# FPGA_SUP.net
KiCad netlist of a schematic drawn in Altium Designer
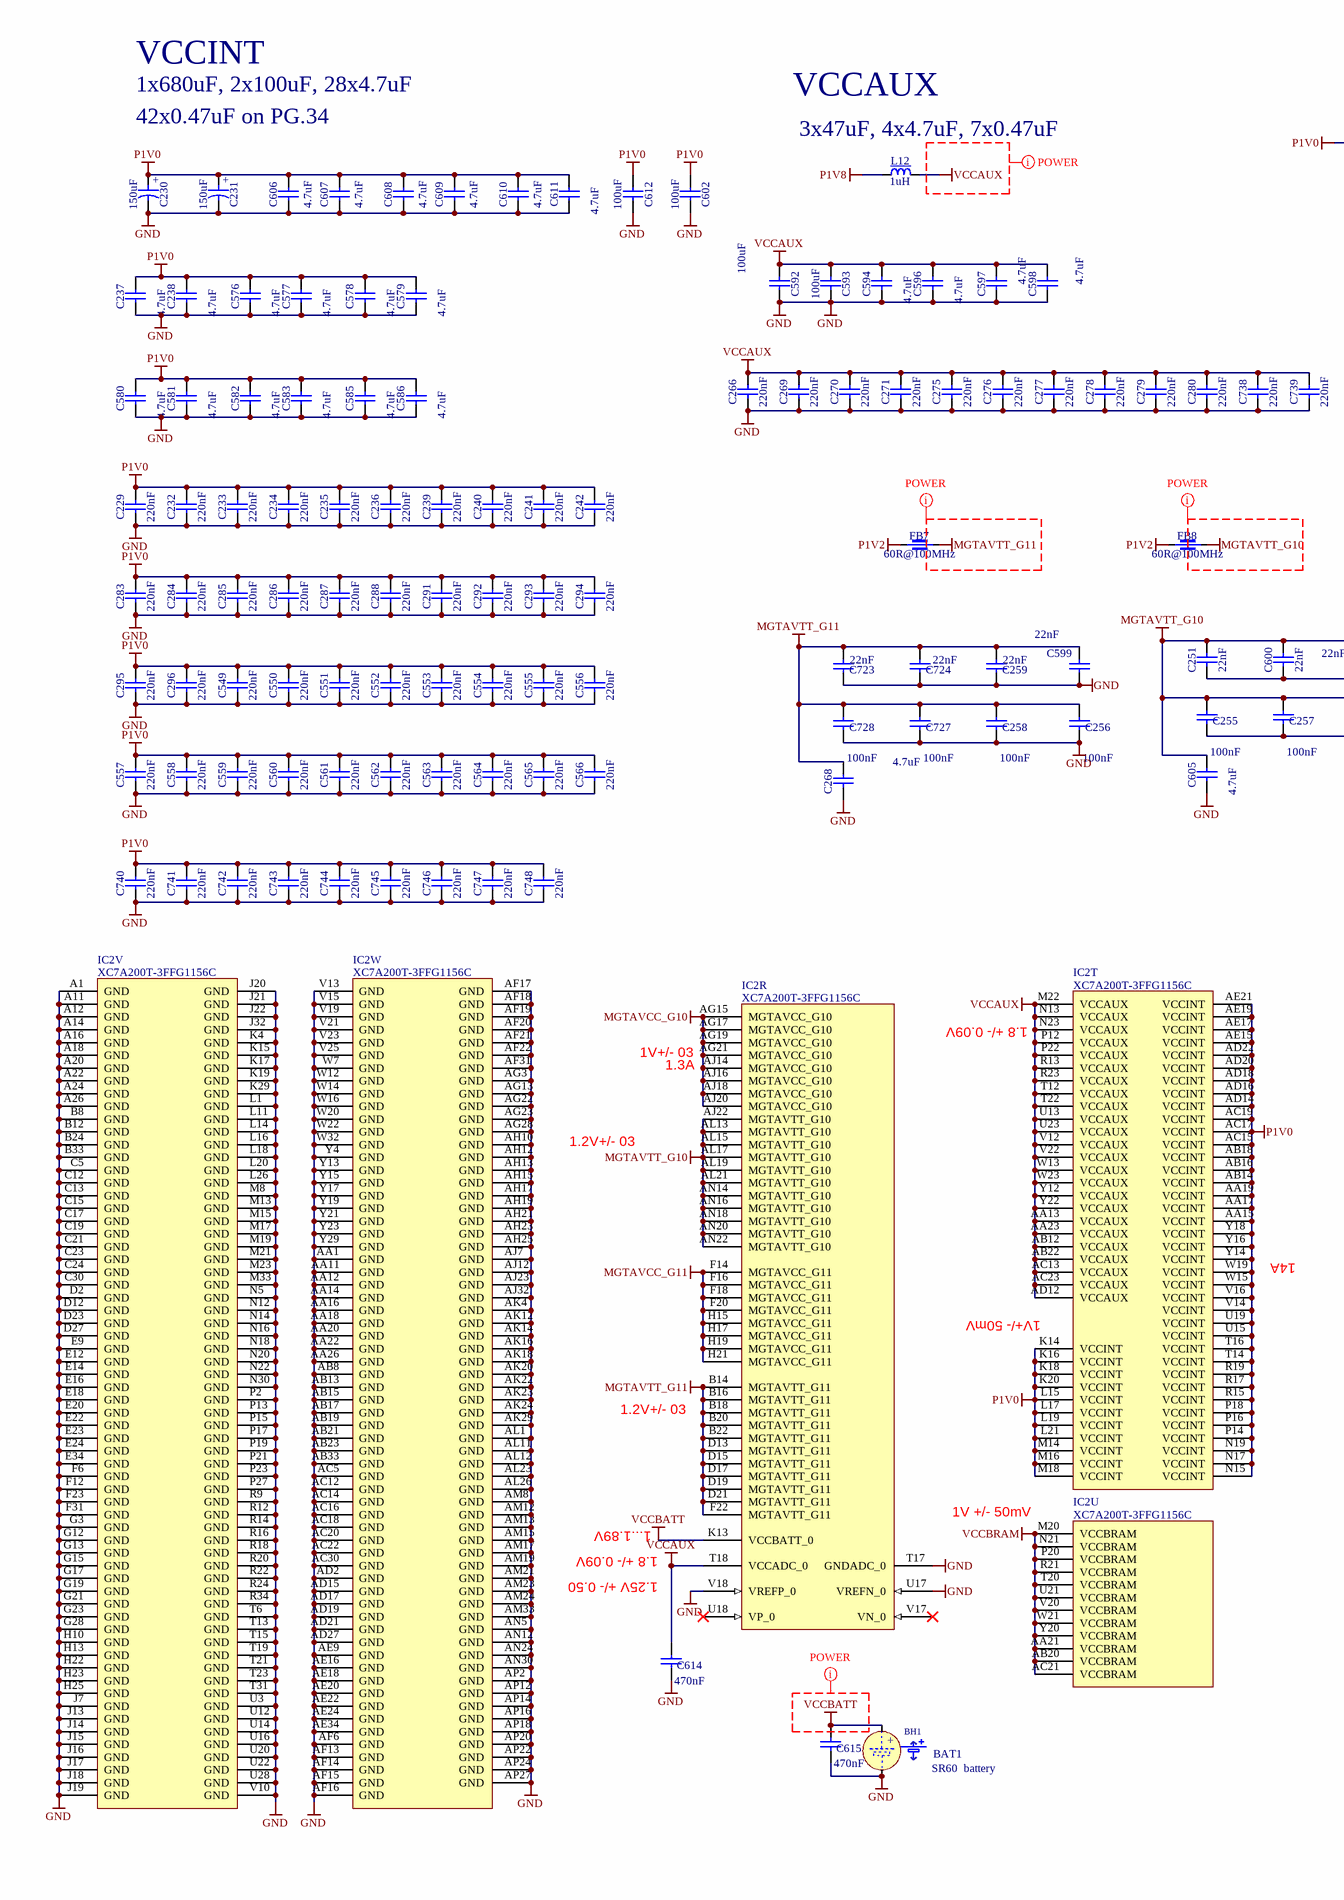
[diagram p0: FPGA_SUP.SchDoc, left]
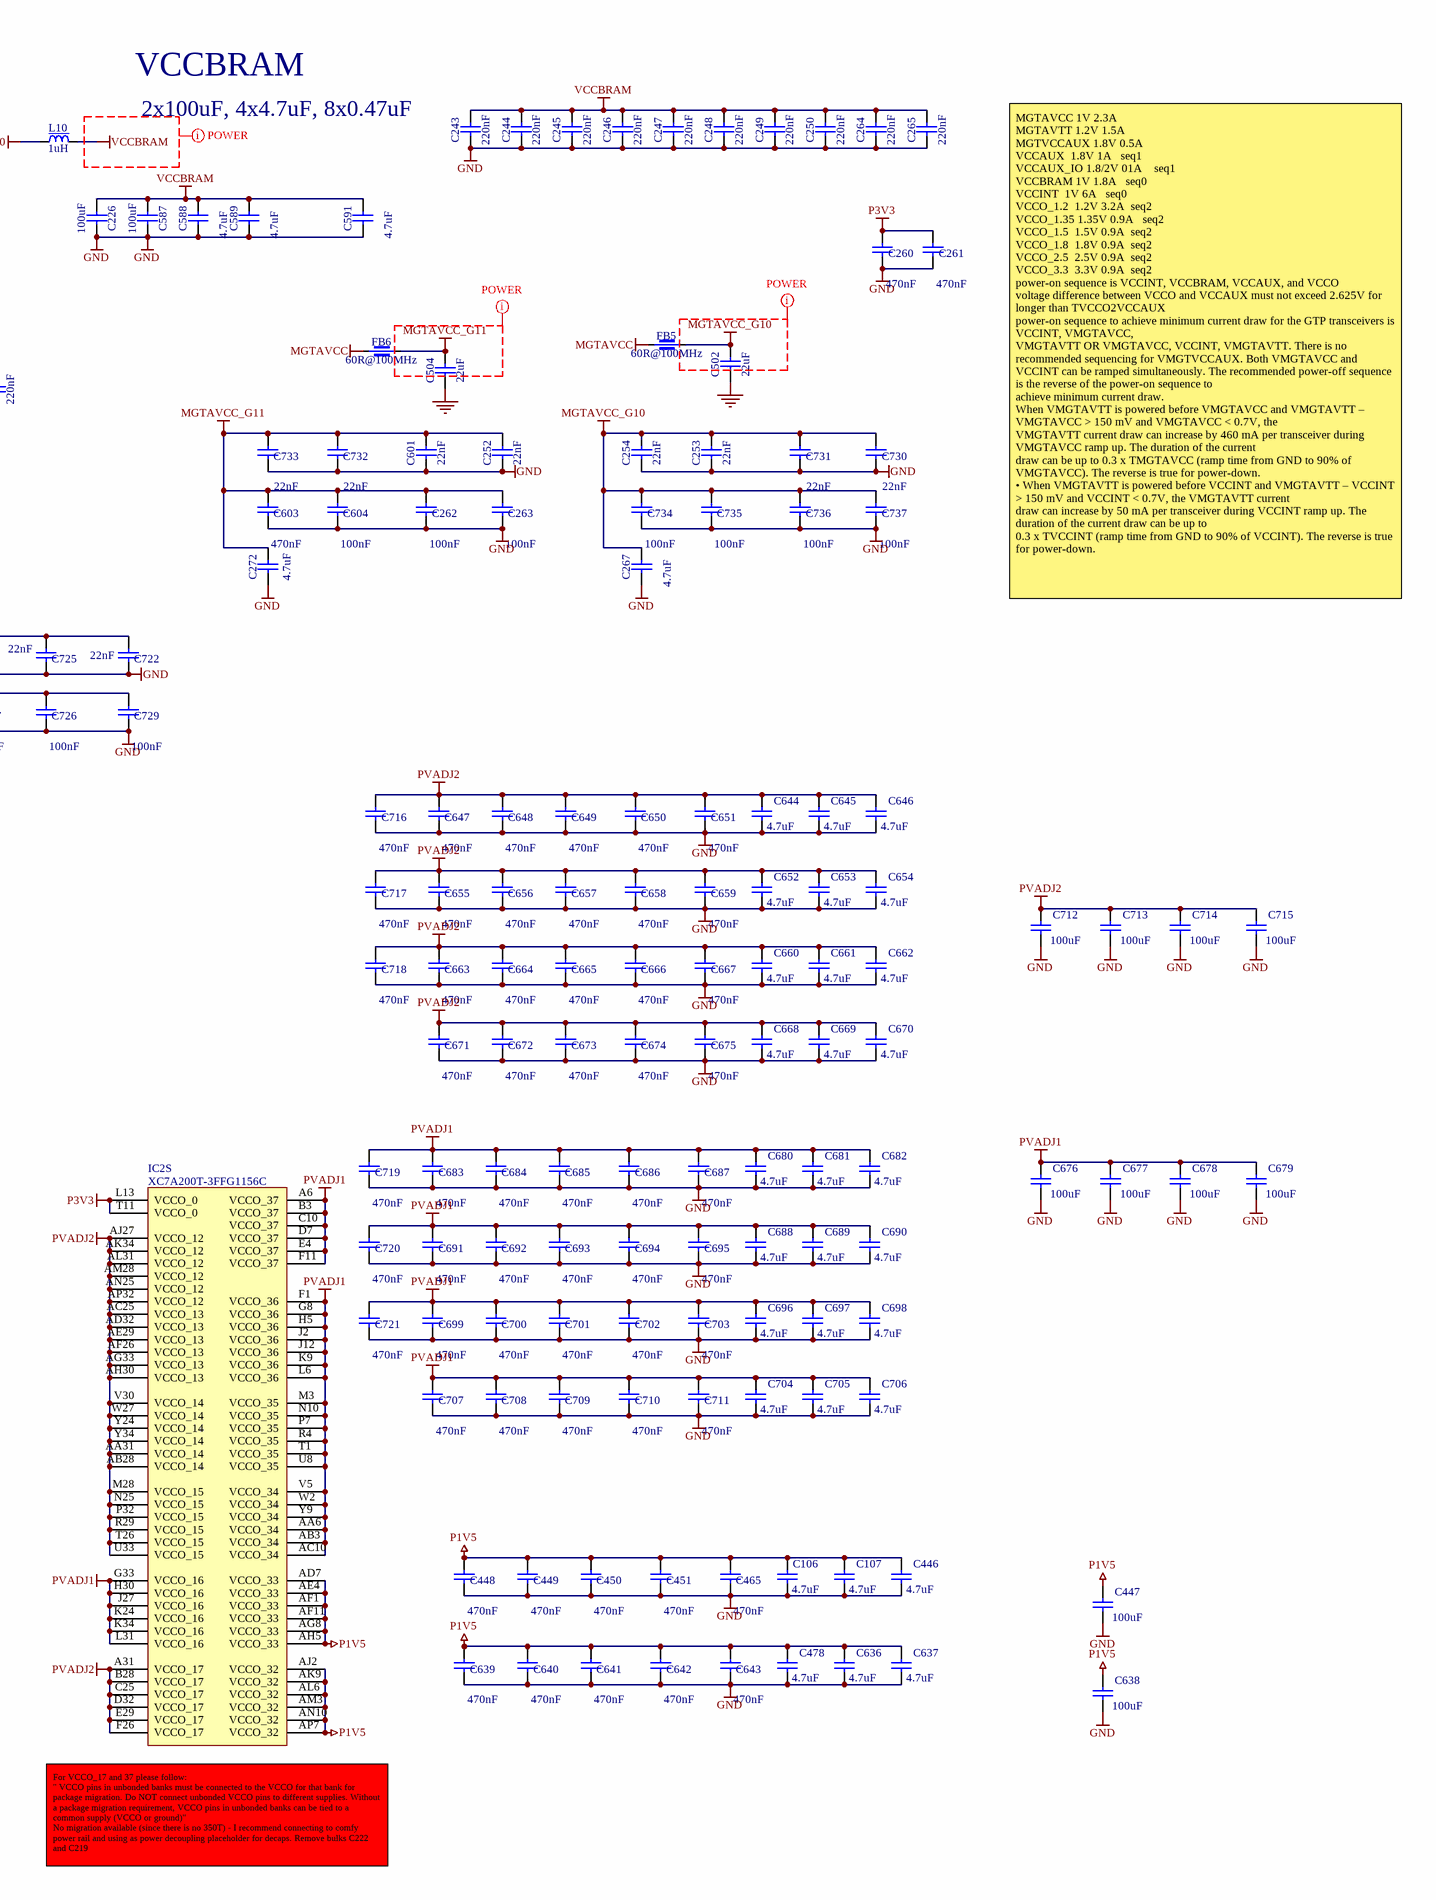
[diagram p1: FPGA_SUP.SchDoc, right]

(export (version "E")
  (design (tool "Eeschema 10.0.6"))
  (components
    (comp (ref "BAT1")
      (value "SR60  battery")
      (footprint "SR60")
      (description "SR60 6.8x2.15mm Battery 1.5V, 15mAh")
      (libsource (lib "LIBRARY_SCH") (part "BATTERY_SR60"))
    )
    (comp (ref "BH1")
      (value "~")
      (footprint "BATH_KEYSTONE_2998")
      (description "Battery Holder whit 2 Pin")
      (fields
        (field (name "PART NUMBER") "BATH_KEYSTONE_2998")
        (field (name "MANUFACTURER") "KEYSTONE")
        (field (name "AUTHOR") "CERN DEM JLC")
      )
      (libsource (lib "Eletro-mechanical") (part "Battery Holder 2 Pin"))
    )
    (comp (ref "C106")
      (value "4.7uF")
      (footprint "CAPC1608X87N")
      (description "Non-polarised capacitor")
      (fields
        (field (name "PART NUMBER") "CC0603_4.7UF_6.3V_10%_X5R")
        (field (name "VOLTAGE") "6.3V")
        (field (name "AUTHOR") "CERN DEM JLC")
      )
      (libsource (lib "Capacitors") (part "Capacitor - non polarized"))
    )
    (comp (ref "C107")
      (value "4.7uF")
      (footprint "CAPC1608X87N")
      (description "Non-polarised capacitor")
      (fields
        (field (name "PART NUMBER") "CC0603_4.7UF_6.3V_10%_X5R")
        (field (name "VOLTAGE") "6.3V")
        (field (name "AUTHOR") "CERN DEM JLC")
      )
      (libsource (lib "Capacitors") (part "Capacitor - non polarized"))
    )
    (comp (ref "C226")
      (value "100uF")
      (footprint "CAPC3225X270N")
      (description "Non-polarised capacitor")
      (fields
        (field (name "PART NUMBER") "CC1210_100UF_6.3V_20%_X5R")
        (field (name "VOLTAGE") "6.3V")
        (field (name "AUTHOR") "CERN DEM JLC")
      )
      (libsource (lib "Capacitors") (part "Capacitor - non polarized"))
    )
    (comp (ref "C229")
      (value "220nF")
      (footprint "CAPC0603X33N")
      (description "Non-polarised capacitor")
      (fields
        (field (name "PART NUMBER") "CC0201_220NF_6.3V_20%_X5R")
        (field (name "VOLTAGE") "6.3V")
        (field (name "AUTHOR") "CERN DEM JLC")
      )
      (libsource (lib "Capacitors") (part "Capacitor - non polarized"))
    )
    (comp (ref "C230")
      (value "150uF")
      (footprint "CAPMP7343X200N")
      (description "Polarised capacitor")
      (fields
        (field (name "PART NUMBER") "CAEM7343-20_150UF_4V_20%_LESR0016")
        (field (name "VOLTAGE") "4V")
        (field (name "AUTHOR") "CERN DEM JLC")
      )
      (libsource (lib "Capacitors") (part "Capacitor - polarized"))
    )
    (comp (ref "C231")
      (value "150uF")
      (footprint "CAPMP7343X200N")
      (description "Polarised capacitor")
      (fields
        (field (name "PART NUMBER") "CAEM7343-20_150UF_4V_20%_LESR0016")
        (field (name "VOLTAGE") "4V")
        (field (name "AUTHOR") "CERN DEM JLC")
      )
      (libsource (lib "Capacitors") (part "Capacitor - polarized"))
    )
    (comp (ref "C232")
      (value "220nF")
      (footprint "CAPC0603X33N")
      (description "Non-polarised capacitor")
      (fields
        (field (name "PART NUMBER") "CC0201_220NF_6.3V_20%_X5R")
        (field (name "VOLTAGE") "6.3V")
        (field (name "AUTHOR") "CERN DEM JLC")
      )
      (libsource (lib "Capacitors") (part "Capacitor - non polarized"))
    )
    (comp (ref "C233")
      (value "220nF")
      (footprint "CAPC0603X33N")
      (description "Non-polarised capacitor")
      (fields
        (field (name "PART NUMBER") "CC0201_220NF_6.3V_20%_X5R")
        (field (name "VOLTAGE") "6.3V")
        (field (name "AUTHOR") "CERN DEM JLC")
      )
      (libsource (lib "Capacitors") (part "Capacitor - non polarized"))
    )
    (comp (ref "C234")
      (value "220nF")
      (footprint "CAPC0603X33N")
      (description "Non-polarised capacitor")
      (fields
        (field (name "PART NUMBER") "CC0201_220NF_6.3V_20%_X5R")
        (field (name "VOLTAGE") "6.3V")
        (field (name "AUTHOR") "CERN DEM JLC")
      )
      (libsource (lib "Capacitors") (part "Capacitor - non polarized"))
    )
    (comp (ref "C235")
      (value "220nF")
      (footprint "CAPC0603X33N")
      (description "Non-polarised capacitor")
      (fields
        (field (name "PART NUMBER") "CC0201_220NF_6.3V_20%_X5R")
        (field (name "VOLTAGE") "6.3V")
        (field (name "AUTHOR") "CERN DEM JLC")
      )
      (libsource (lib "Capacitors") (part "Capacitor - non polarized"))
    )
    (comp (ref "C236")
      (value "220nF")
      (footprint "CAPC0603X33N")
      (description "Non-polarised capacitor")
      (fields
        (field (name "PART NUMBER") "CC0201_220NF_6.3V_20%_X5R")
        (field (name "VOLTAGE") "6.3V")
        (field (name "AUTHOR") "CERN DEM JLC")
      )
      (libsource (lib "Capacitors") (part "Capacitor - non polarized"))
    )
    (comp (ref "C237")
      (value "4.7uF")
      (footprint "CAPC1608X87N")
      (description "Non-polarised capacitor")
      (fields
        (field (name "PART NUMBER") "CC0603_4.7UF_6.3V_10%_X5R")
        (field (name "VOLTAGE") "6.3V")
        (field (name "AUTHOR") "CERN DEM JLC")
      )
      (libsource (lib "Capacitors") (part "Capacitor - non polarized"))
    )
    (comp (ref "C238")
      (value "4.7uF")
      (footprint "CAPC1608X87N")
      (description "Non-polarised capacitor")
      (fields
        (field (name "PART NUMBER") "CC0603_4.7UF_6.3V_10%_X5R")
        (field (name "VOLTAGE") "6.3V")
        (field (name "AUTHOR") "CERN DEM JLC")
      )
      (libsource (lib "Capacitors") (part "Capacitor - non polarized"))
    )
    (comp (ref "C239")
      (value "220nF")
      (footprint "CAPC0603X33N")
      (description "Non-polarised capacitor")
      (fields
        (field (name "PART NUMBER") "CC0201_220NF_6.3V_20%_X5R")
        (field (name "VOLTAGE") "6.3V")
        (field (name "AUTHOR") "CERN DEM JLC")
      )
      (libsource (lib "Capacitors") (part "Capacitor - non polarized"))
    )
    (comp (ref "C240")
      (value "220nF")
      (footprint "CAPC0603X33N")
      (description "Non-polarised capacitor")
      (fields
        (field (name "PART NUMBER") "CC0201_220NF_6.3V_20%_X5R")
        (field (name "VOLTAGE") "6.3V")
        (field (name "AUTHOR") "CERN DEM JLC")
      )
      (libsource (lib "Capacitors") (part "Capacitor - non polarized"))
    )
    (comp (ref "C241")
      (value "220nF")
      (footprint "CAPC0603X33N")
      (description "Non-polarised capacitor")
      (fields
        (field (name "PART NUMBER") "CC0201_220NF_6.3V_20%_X5R")
        (field (name "VOLTAGE") "6.3V")
        (field (name "AUTHOR") "CERN DEM JLC")
      )
      (libsource (lib "Capacitors") (part "Capacitor - non polarized"))
    )
    (comp (ref "C242")
      (value "220nF")
      (footprint "CAPC0603X33N")
      (description "Non-polarised capacitor")
      (fields
        (field (name "PART NUMBER") "CC0201_220NF_6.3V_20%_X5R")
        (field (name "VOLTAGE") "6.3V")
        (field (name "AUTHOR") "CERN DEM JLC")
      )
      (libsource (lib "Capacitors") (part "Capacitor - non polarized"))
    )
    (comp (ref "C243")
      (value "220nF")
      (footprint "CAPC0603X33N")
      (description "Non-polarised capacitor")
      (fields
        (field (name "PART NUMBER") "CC0201_220NF_6.3V_20%_X5R")
        (field (name "VOLTAGE") "6.3V")
        (field (name "AUTHOR") "CERN DEM JLC")
      )
      (libsource (lib "Capacitors") (part "Capacitor - non polarized"))
    )
    (comp (ref "C244")
      (value "220nF")
      (footprint "CAPC0603X33N")
      (description "Non-polarised capacitor")
      (fields
        (field (name "PART NUMBER") "CC0201_220NF_6.3V_20%_X5R")
        (field (name "VOLTAGE") "6.3V")
        (field (name "AUTHOR") "CERN DEM JLC")
      )
      (libsource (lib "Capacitors") (part "Capacitor - non polarized"))
    )
    (comp (ref "C245")
      (value "220nF")
      (footprint "CAPC0603X33N")
      (description "Non-polarised capacitor")
      (fields
        (field (name "PART NUMBER") "CC0201_220NF_6.3V_20%_X5R")
        (field (name "VOLTAGE") "6.3V")
        (field (name "AUTHOR") "CERN DEM JLC")
      )
      (libsource (lib "Capacitors") (part "Capacitor - non polarized"))
    )
    (comp (ref "C246")
      (value "220nF")
      (footprint "CAPC0603X33N")
      (description "Non-polarised capacitor")
      (fields
        (field (name "PART NUMBER") "CC0201_220NF_6.3V_20%_X5R")
        (field (name "VOLTAGE") "6.3V")
        (field (name "AUTHOR") "CERN DEM JLC")
      )
      (libsource (lib "Capacitors") (part "Capacitor - non polarized"))
    )
    (comp (ref "C247")
      (value "220nF")
      (footprint "CAPC0603X33N")
      (description "Non-polarised capacitor")
      (fields
        (field (name "PART NUMBER") "CC0201_220NF_6.3V_20%_X5R")
        (field (name "VOLTAGE") "6.3V")
        (field (name "AUTHOR") "CERN DEM JLC")
      )
      (libsource (lib "Capacitors") (part "Capacitor - non polarized"))
    )
    (comp (ref "C248")
      (value "220nF")
      (footprint "CAPC0603X33N")
      (description "Non-polarised capacitor")
      (fields
        (field (name "PART NUMBER") "CC0201_220NF_6.3V_20%_X5R")
        (field (name "VOLTAGE") "6.3V")
        (field (name "AUTHOR") "CERN DEM JLC")
      )
      (libsource (lib "Capacitors") (part "Capacitor - non polarized"))
    )
    (comp (ref "C249")
      (value "220nF")
      (footprint "CAPC0603X33N")
      (description "Non-polarised capacitor")
      (fields
        (field (name "PART NUMBER") "CC0201_220NF_6.3V_20%_X5R")
        (field (name "VOLTAGE") "6.3V")
        (field (name "AUTHOR") "CERN DEM JLC")
      )
      (libsource (lib "Capacitors") (part "Capacitor - non polarized"))
    )
    (comp (ref "C250")
      (value "220nF")
      (footprint "CAPC0603X33N")
      (description "Non-polarised capacitor")
      (fields
        (field (name "PART NUMBER") "CC0201_220NF_6.3V_20%_X5R")
        (field (name "VOLTAGE") "6.3V")
        (field (name "AUTHOR") "CERN DEM JLC")
      )
      (libsource (lib "Capacitors") (part "Capacitor - non polarized"))
    )
    (comp (ref "C251")
      (value "22nF")
      (footprint "CAPC0603X33N")
      (description "Non-polarised capacitor")
      (fields
        (field (name "PART NUMBER") "CC0201_22NF_6.3V_10%_X5R")
        (field (name "VOLTAGE") "6.3V")
        (field (name "AUTHOR") "CERN DEM JLC")
      )
      (libsource (lib "Capacitors") (part "Capacitor - non polarized"))
    )
    (comp (ref "C252")
      (value "22nF")
      (footprint "CAPC0603X33N")
      (description "Non-polarised capacitor")
      (fields
        (field (name "PART NUMBER") "CC0201_22NF_6.3V_10%_X5R")
        (field (name "VOLTAGE") "6.3V")
        (field (name "AUTHOR") "CERN DEM JLC")
      )
      (libsource (lib "Capacitors") (part "Capacitor - non polarized"))
    )
    (comp (ref "C253")
      (value "22nF")
      (footprint "CAPC0603X33N")
      (description "Non-polarised capacitor")
      (fields
        (field (name "PART NUMBER") "CC0201_22NF_6.3V_10%_X5R")
        (field (name "VOLTAGE") "6.3V")
        (field (name "AUTHOR") "CERN DEM JLC")
      )
      (libsource (lib "Capacitors") (part "Capacitor - non polarized"))
    )
    (comp (ref "C254")
      (value "22nF")
      (footprint "CAPC0603X33N")
      (description "Non-polarised capacitor")
      (fields
        (field (name "PART NUMBER") "CC0201_22NF_6.3V_10%_X5R")
        (field (name "VOLTAGE") "6.3V")
        (field (name "AUTHOR") "CERN DEM JLC")
      )
      (libsource (lib "Capacitors") (part "Capacitor - non polarized"))
    )
    (comp (ref "C255")
      (value "100nF")
      (footprint "CAPC0603X33N")
      (description "Non-polarised capacitor")
      (fields
        (field (name "PART NUMBER") "CC0201_100NF_6.3V_10%_X5R")
        (field (name "VOLTAGE") "6.3V")
        (field (name "AUTHOR") "CERN DEM JLC")
      )
      (libsource (lib "Capacitors") (part "Capacitor - non polarized"))
    )
    (comp (ref "C256")
      (value "100nF")
      (footprint "CAPC0603X33N")
      (description "Non-polarised capacitor")
      (fields
        (field (name "PART NUMBER") "CC0201_100NF_6.3V_10%_X5R")
        (field (name "VOLTAGE") "6.3V")
        (field (name "AUTHOR") "CERN DEM JLC")
      )
      (libsource (lib "Capacitors") (part "Capacitor - non polarized"))
    )
    (comp (ref "C257")
      (value "100nF")
      (footprint "CAPC0603X33N")
      (description "Non-polarised capacitor")
      (fields
        (field (name "PART NUMBER") "CC0201_100NF_6.3V_10%_X5R")
        (field (name "VOLTAGE") "6.3V")
        (field (name "AUTHOR") "CERN DEM JLC")
      )
      (libsource (lib "Capacitors") (part "Capacitor - non polarized"))
    )
    (comp (ref "C258")
      (value "100nF")
      (footprint "CAPC0603X33N")
      (description "Non-polarised capacitor")
      (fields
        (field (name "PART NUMBER") "CC0201_100NF_6.3V_10%_X5R")
        (field (name "VOLTAGE") "6.3V")
        (field (name "AUTHOR") "CERN DEM JLC")
      )
      (libsource (lib "Capacitors") (part "Capacitor - non polarized"))
    )
    (comp (ref "C259")
      (value "22nF")
      (footprint "CAPC0603X33N")
      (description "Non-polarised capacitor")
      (fields
        (field (name "PART NUMBER") "CC0201_22NF_6.3V_10%_X5R")
        (field (name "VOLTAGE") "6.3V")
        (field (name "AUTHOR") "CERN DEM JLC")
      )
      (libsource (lib "Capacitors") (part "Capacitor - non polarized"))
    )
    (comp (ref "C260")
      (value "470nF")
      (footprint "CAPC0603X33N")
      (description "Non-polarised capacitor")
      (fields
        (field (name "PART NUMBER") "CC0201_470NF_4V_20%_X5R")
        (field (name "VOLTAGE") "4V")
        (field (name "AUTHOR") "CERN DEM JLC")
      )
      (libsource (lib "Capacitors") (part "Capacitor - non polarized"))
    )
    (comp (ref "C261")
      (value "470nF")
      (footprint "CAPC0603X33N")
      (description "Non-polarised capacitor")
      (fields
        (field (name "PART NUMBER") "CC0201_470NF_4V_20%_X5R")
        (field (name "VOLTAGE") "4V")
        (field (name "AUTHOR") "CERN DEM JLC")
      )
      (libsource (lib "Capacitors") (part "Capacitor - non polarized"))
    )
    (comp (ref "C262")
      (value "100nF")
      (footprint "CAPC0603X33N")
      (description "Non-polarised capacitor")
      (fields
        (field (name "PART NUMBER") "CC0201_100NF_6.3V_10%_X5R")
        (field (name "VOLTAGE") "6.3V")
        (field (name "AUTHOR") "CERN DEM JLC")
      )
      (libsource (lib "Capacitors") (part "Capacitor - non polarized"))
    )
    (comp (ref "C263")
      (value "100nF")
      (footprint "CAPC0603X33N")
      (description "Non-polarised capacitor")
      (fields
        (field (name "PART NUMBER") "CC0201_100NF_6.3V_10%_X5R")
        (field (name "VOLTAGE") "6.3V")
        (field (name "AUTHOR") "CERN DEM JLC")
      )
      (libsource (lib "Capacitors") (part "Capacitor - non polarized"))
    )
    (comp (ref "C264")
      (value "220nF")
      (footprint "CAPC0603X33N")
      (description "Non-polarised capacitor")
      (fields
        (field (name "PART NUMBER") "CC0201_220NF_6.3V_20%_X5R")
        (field (name "VOLTAGE") "6.3V")
        (field (name "AUTHOR") "CERN DEM JLC")
      )
      (libsource (lib "Capacitors") (part "Capacitor - non polarized"))
    )
    (comp (ref "C265")
      (value "220nF")
      (footprint "CAPC0603X33N")
      (description "Non-polarised capacitor")
      (fields
        (field (name "PART NUMBER") "CC0201_220NF_6.3V_20%_X5R")
        (field (name "VOLTAGE") "6.3V")
        (field (name "AUTHOR") "CERN DEM JLC")
      )
      (libsource (lib "Capacitors") (part "Capacitor - non polarized"))
    )
    (comp (ref "C266")
      (value "220nF")
      (footprint "CAPC0603X33N")
      (description "Non-polarised capacitor")
      (fields
        (field (name "PART NUMBER") "CC0201_220NF_6.3V_20%_X5R")
        (field (name "VOLTAGE") "6.3V")
        (field (name "AUTHOR") "CERN DEM JLC")
      )
      (libsource (lib "Capacitors") (part "Capacitor - non polarized"))
    )
    (comp (ref "C267")
      (value "4.7uF")
      (footprint "CAPC1608X87N")
      (description "Non-polarised capacitor")
      (fields
        (field (name "PART NUMBER") "CC0603_4.7UF_6.3V_10%_X5R")
        (field (name "VOLTAGE") "6.3V")
        (field (name "AUTHOR") "CERN DEM JLC")
      )
      (libsource (lib "Capacitors") (part "Capacitor - non polarized"))
    )
    (comp (ref "C268")
      (value "4.7uF")
      (footprint "CAPC1608X87N")
      (description "Non-polarised capacitor")
      (fields
        (field (name "PART NUMBER") "CC0603_4.7UF_6.3V_10%_X5R")
        (field (name "VOLTAGE") "6.3V")
        (field (name "AUTHOR") "CERN DEM JLC")
      )
      (libsource (lib "Capacitors") (part "Capacitor - non polarized"))
    )
    (comp (ref "C269")
      (value "220nF")
      (footprint "CAPC0603X33N")
      (description "Non-polarised capacitor")
      (fields
        (field (name "PART NUMBER") "CC0201_220NF_6.3V_20%_X5R")
        (field (name "VOLTAGE") "6.3V")
        (field (name "AUTHOR") "CERN DEM JLC")
      )
      (libsource (lib "Capacitors") (part "Capacitor - non polarized"))
    )
    (comp (ref "C270")
      (value "220nF")
      (footprint "CAPC0603X33N")
      (description "Non-polarised capacitor")
      (fields
        (field (name "PART NUMBER") "CC0201_220NF_6.3V_20%_X5R")
        (field (name "VOLTAGE") "6.3V")
        (field (name "AUTHOR") "CERN DEM JLC")
      )
      (libsource (lib "Capacitors") (part "Capacitor - non polarized"))
    )
    (comp (ref "C271")
      (value "220nF")
      (footprint "CAPC0603X33N")
      (description "Non-polarised capacitor")
      (fields
        (field (name "PART NUMBER") "CC0201_220NF_6.3V_20%_X5R")
        (field (name "VOLTAGE") "6.3V")
        (field (name "AUTHOR") "CERN DEM JLC")
      )
      (libsource (lib "Capacitors") (part "Capacitor - non polarized"))
    )
    (comp (ref "C272")
      (value "4.7uF")
      (footprint "CAPC1608X87N")
      (description "Non-polarised capacitor")
      (fields
        (field (name "PART NUMBER") "CC0603_4.7UF_6.3V_10%_X5R")
        (field (name "VOLTAGE") "6.3V")
        (field (name "AUTHOR") "CERN DEM JLC")
      )
      (libsource (lib "Capacitors") (part "Capacitor - non polarized"))
    )
    (comp (ref "C275")
      (value "220nF")
      (footprint "CAPC0603X33N")
      (description "Non-polarised capacitor")
      (fields
        (field (name "PART NUMBER") "CC0201_220NF_6.3V_20%_X5R")
        (field (name "VOLTAGE") "6.3V")
        (field (name "AUTHOR") "CERN DEM JLC")
      )
      (libsource (lib "Capacitors") (part "Capacitor - non polarized"))
    )
    (comp (ref "C276")
      (value "220nF")
      (footprint "CAPC0603X33N")
      (description "Non-polarised capacitor")
      (fields
        (field (name "PART NUMBER") "CC0201_220NF_6.3V_20%_X5R")
        (field (name "VOLTAGE") "6.3V")
        (field (name "AUTHOR") "CERN DEM JLC")
      )
      (libsource (lib "Capacitors") (part "Capacitor - non polarized"))
    )
    (comp (ref "C277")
      (value "220nF")
      (footprint "CAPC0603X33N")
      (description "Non-polarised capacitor")
      (fields
        (field (name "PART NUMBER") "CC0201_220NF_6.3V_20%_X5R")
        (field (name "VOLTAGE") "6.3V")
        (field (name "AUTHOR") "CERN DEM JLC")
      )
      (libsource (lib "Capacitors") (part "Capacitor - non polarized"))
    )
    (comp (ref "C278")
      (value "220nF")
      (footprint "CAPC0603X33N")
      (description "Non-polarised capacitor")
      (fields
        (field (name "PART NUMBER") "CC0201_220NF_6.3V_20%_X5R")
        (field (name "VOLTAGE") "6.3V")
        (field (name "AUTHOR") "CERN DEM JLC")
      )
      (libsource (lib "Capacitors") (part "Capacitor - non polarized"))
    )
    (comp (ref "C279")
      (value "220nF")
      (footprint "CAPC0603X33N")
      (description "Non-polarised capacitor")
      (fields
        (field (name "PART NUMBER") "CC0201_220NF_6.3V_20%_X5R")
        (field (name "VOLTAGE") "6.3V")
        (field (name "AUTHOR") "CERN DEM JLC")
      )
      (libsource (lib "Capacitors") (part "Capacitor - non polarized"))
    )
    (comp (ref "C280")
      (value "220nF")
      (footprint "CAPC0603X33N")
      (description "Non-polarised capacitor")
      (fields
        (field (name "PART NUMBER") "CC0201_220NF_6.3V_20%_X5R")
        (field (name "VOLTAGE") "6.3V")
        (field (name "AUTHOR") "CERN DEM JLC")
      )
      (libsource (lib "Capacitors") (part "Capacitor - non polarized"))
    )
    (comp (ref "C283")
      (value "220nF")
      (footprint "CAPC0603X33N")
      (description "Non-polarised capacitor")
      (fields
        (field (name "PART NUMBER") "CC0201_220NF_6.3V_20%_X5R")
        (field (name "VOLTAGE") "6.3V")
        (field (name "AUTHOR") "CERN DEM JLC")
      )
      (libsource (lib "Capacitors") (part "Capacitor - non polarized"))
    )
    (comp (ref "C284")
      (value "220nF")
      (footprint "CAPC0603X33N")
      (description "Non-polarised capacitor")
      (fields
        (field (name "PART NUMBER") "CC0201_220NF_6.3V_20%_X5R")
        (field (name "VOLTAGE") "6.3V")
        (field (name "AUTHOR") "CERN DEM JLC")
      )
      (libsource (lib "Capacitors") (part "Capacitor - non polarized"))
    )
    (comp (ref "C285")
      (value "220nF")
      (footprint "CAPC0603X33N")
      (description "Non-polarised capacitor")
      (fields
        (field (name "PART NUMBER") "CC0201_220NF_6.3V_20%_X5R")
        (field (name "VOLTAGE") "6.3V")
        (field (name "AUTHOR") "CERN DEM JLC")
      )
      (libsource (lib "Capacitors") (part "Capacitor - non polarized"))
    )
    (comp (ref "C286")
      (value "220nF")
      (footprint "CAPC0603X33N")
      (description "Non-polarised capacitor")
      (fields
        (field (name "PART NUMBER") "CC0201_220NF_6.3V_20%_X5R")
        (field (name "VOLTAGE") "6.3V")
        (field (name "AUTHOR") "CERN DEM JLC")
      )
      (libsource (lib "Capacitors") (part "Capacitor - non polarized"))
    )
    (comp (ref "C287")
      (value "220nF")
      (footprint "CAPC0603X33N")
      (description "Non-polarised capacitor")
      (fields
        (field (name "PART NUMBER") "CC0201_220NF_6.3V_20%_X5R")
        (field (name "VOLTAGE") "6.3V")
        (field (name "AUTHOR") "CERN DEM JLC")
      )
      (libsource (lib "Capacitors") (part "Capacitor - non polarized"))
    )
    (comp (ref "C288")
      (value "220nF")
      (footprint "CAPC0603X33N")
      (description "Non-polarised capacitor")
      (fields
        (field (name "PART NUMBER") "CC0201_220NF_6.3V_20%_X5R")
        (field (name "VOLTAGE") "6.3V")
        (field (name "AUTHOR") "CERN DEM JLC")
      )
      (libsource (lib "Capacitors") (part "Capacitor - non polarized"))
    )
    (comp (ref "C291")
      (value "220nF")
      (footprint "CAPC0603X33N")
      (description "Non-polarised capacitor")
      (fields
        (field (name "PART NUMBER") "CC0201_220NF_6.3V_20%_X5R")
        (field (name "VOLTAGE") "6.3V")
        (field (name "AUTHOR") "CERN DEM JLC")
      )
      (libsource (lib "Capacitors") (part "Capacitor - non polarized"))
    )
    (comp (ref "C292")
      (value "220nF")
      (footprint "CAPC0603X33N")
      (description "Non-polarised capacitor")
      (fields
        (field (name "PART NUMBER") "CC0201_220NF_6.3V_20%_X5R")
        (field (name "VOLTAGE") "6.3V")
        (field (name "AUTHOR") "CERN DEM JLC")
      )
      (libsource (lib "Capacitors") (part "Capacitor - non polarized"))
    )
    (comp (ref "C293")
      (value "220nF")
      (footprint "CAPC0603X33N")
      (description "Non-polarised capacitor")
      (fields
        (field (name "PART NUMBER") "CC0201_220NF_6.3V_20%_X5R")
        (field (name "VOLTAGE") "6.3V")
        (field (name "AUTHOR") "CERN DEM JLC")
      )
      (libsource (lib "Capacitors") (part "Capacitor - non polarized"))
    )
    (comp (ref "C294")
      (value "220nF")
      (footprint "CAPC0603X33N")
      (description "Non-polarised capacitor")
      (fields
        (field (name "PART NUMBER") "CC0201_220NF_6.3V_20%_X5R")
        (field (name "VOLTAGE") "6.3V")
        (field (name "AUTHOR") "CERN DEM JLC")
      )
      (libsource (lib "Capacitors") (part "Capacitor - non polarized"))
    )
    (comp (ref "C295")
      (value "220nF")
      (footprint "CAPC0603X33N")
      (description "Non-polarised capacitor")
      (fields
        (field (name "PART NUMBER") "CC0201_220NF_6.3V_20%_X5R")
        (field (name "VOLTAGE") "6.3V")
        (field (name "AUTHOR") "CERN DEM JLC")
      )
      (libsource (lib "Capacitors") (part "Capacitor - non polarized"))
    )
    (comp (ref "C296")
      (value "220nF")
      (footprint "CAPC0603X33N")
      (description "Non-polarised capacitor")
      (fields
        (field (name "PART NUMBER") "CC0201_220NF_6.3V_20%_X5R")
        (field (name "VOLTAGE") "6.3V")
        (field (name "AUTHOR") "CERN DEM JLC")
      )
      (libsource (lib "Capacitors") (part "Capacitor - non polarized"))
    )
    (comp (ref "C446")
      (value "4.7uF")
      (footprint "CAPC1608X87N")
      (description "Non-polarised capacitor")
      (fields
        (field (name "PART NUMBER") "CC0603_4.7UF_6.3V_10%_X5R")
        (field (name "VOLTAGE") "6.3V")
        (field (name "AUTHOR") "CERN DEM JLC")
      )
      (libsource (lib "Capacitors") (part "Capacitor - non polarized"))
    )
    (comp (ref "C447")
      (value "100uF")
      (footprint "CAPC3225X270N")
      (description "Non-polarised capacitor")
      (fields
        (field (name "PART NUMBER") "CC1210_100UF_6.3V_20%_X5R")
        (field (name "VOLTAGE") "6.3V")
        (field (name "AUTHOR") "CERN DEM JLC")
      )
      (libsource (lib "Capacitors") (part "Capacitor - non polarized"))
    )
    (comp (ref "C448")
      (value "470nF")
      (footprint "CAPC0603X33N")
      (description "Non-polarised capacitor")
      (fields
        (field (name "PART NUMBER") "CC0201_470NF_4V_20%_X5R")
        (field (name "VOLTAGE") "4V")
        (field (name "AUTHOR") "CERN DEM JLC")
      )
      (libsource (lib "Capacitors") (part "Capacitor - non polarized"))
    )
    (comp (ref "C449")
      (value "470nF")
      (footprint "CAPC0603X33N")
      (description "Non-polarised capacitor")
      (fields
        (field (name "PART NUMBER") "CC0201_470NF_4V_20%_X5R")
        (field (name "VOLTAGE") "4V")
        (field (name "AUTHOR") "CERN DEM JLC")
      )
      (libsource (lib "Capacitors") (part "Capacitor - non polarized"))
    )
    (comp (ref "C450")
      (value "470nF")
      (footprint "CAPC0603X33N")
      (description "Non-polarised capacitor")
      (fields
        (field (name "PART NUMBER") "CC0201_470NF_4V_20%_X5R")
        (field (name "VOLTAGE") "4V")
        (field (name "AUTHOR") "CERN DEM JLC")
      )
      (libsource (lib "Capacitors") (part "Capacitor - non polarized"))
    )
    (comp (ref "C451")
      (value "470nF")
      (footprint "CAPC0603X33N")
      (description "Non-polarised capacitor")
      (fields
        (field (name "PART NUMBER") "CC0201_470NF_4V_20%_X5R")
        (field (name "VOLTAGE") "4V")
        (field (name "AUTHOR") "CERN DEM JLC")
      )
      (libsource (lib "Capacitors") (part "Capacitor - non polarized"))
    )
    (comp (ref "C465")
      (value "470nF")
      (footprint "CAPC0603X33N")
      (description "Non-polarised capacitor")
      (fields
        (field (name "PART NUMBER") "CC0201_470NF_4V_20%_X5R")
        (field (name "VOLTAGE") "4V")
        (field (name "AUTHOR") "CERN DEM JLC")
      )
      (libsource (lib "Capacitors") (part "Capacitor - non polarized"))
    )
    (comp (ref "C478")
      (value "4.7uF")
      (footprint "CAPC1608X87N")
      (description "Non-polarised capacitor")
      (fields
        (field (name "PART NUMBER") "CC0603_4.7UF_6.3V_10%_X5R")
        (field (name "VOLTAGE") "6.3V")
        (field (name "AUTHOR") "CERN DEM JLC")
      )
      (libsource (lib "Capacitors") (part "Capacitor - non polarized"))
    )
    (comp (ref "C502")
      (value "22uF")
      (footprint "CAPC1709X100N")
      (description "Non-polarised capacitor")
      (fields
        (field (name "PART NUMBER") "CC0603_22UF_6.3V_20%_X5R")
        (field (name "VOLTAGE") "6.3V")
        (field (name "AUTHOR") "CERN DEM JLC")
      )
      (libsource (lib "Capacitors") (part "Capacitor - non polarized"))
    )
    (comp (ref "C504")
      (value "22uF")
      (footprint "CAPC1709X100N")
      (description "Non-polarised capacitor")
      (fields
        (field (name "PART NUMBER") "CC0603_22UF_6.3V_20%_X5R")
        (field (name "VOLTAGE") "6.3V")
        (field (name "AUTHOR") "CERN DEM JLC")
      )
      (libsource (lib "Capacitors") (part "Capacitor - non polarized"))
    )
    (comp (ref "C549")
      (value "220nF")
      (footprint "CAPC0603X33N")
      (description "Non-polarised capacitor")
      (fields
        (field (name "PART NUMBER") "CC0201_220NF_6.3V_20%_X5R")
        (field (name "VOLTAGE") "6.3V")
        (field (name "AUTHOR") "CERN DEM JLC")
      )
      (libsource (lib "Capacitors") (part "Capacitor - non polarized"))
    )
    (comp (ref "C550")
      (value "220nF")
      (footprint "CAPC0603X33N")
      (description "Non-polarised capacitor")
      (fields
        (field (name "PART NUMBER") "CC0201_220NF_6.3V_20%_X5R")
        (field (name "VOLTAGE") "6.3V")
        (field (name "AUTHOR") "CERN DEM JLC")
      )
      (libsource (lib "Capacitors") (part "Capacitor - non polarized"))
    )
    (comp (ref "C551")
      (value "220nF")
      (footprint "CAPC0603X33N")
      (description "Non-polarised capacitor")
      (fields
        (field (name "PART NUMBER") "CC0201_220NF_6.3V_20%_X5R")
        (field (name "VOLTAGE") "6.3V")
        (field (name "AUTHOR") "CERN DEM JLC")
      )
      (libsource (lib "Capacitors") (part "Capacitor - non polarized"))
    )
    (comp (ref "C552")
      (value "220nF")
      (footprint "CAPC0603X33N")
      (description "Non-polarised capacitor")
      (fields
        (field (name "PART NUMBER") "CC0201_220NF_6.3V_20%_X5R")
        (field (name "VOLTAGE") "6.3V")
        (field (name "AUTHOR") "CERN DEM JLC")
      )
      (libsource (lib "Capacitors") (part "Capacitor - non polarized"))
    )
    (comp (ref "C553")
      (value "220nF")
      (footprint "CAPC0603X33N")
      (description "Non-polarised capacitor")
      (fields
        (field (name "PART NUMBER") "CC0201_220NF_6.3V_20%_X5R")
        (field (name "VOLTAGE") "6.3V")
        (field (name "AUTHOR") "CERN DEM JLC")
      )
      (libsource (lib "Capacitors") (part "Capacitor - non polarized"))
    )
    (comp (ref "C554")
      (value "220nF")
      (footprint "CAPC0603X33N")
      (description "Non-polarised capacitor")
      (fields
        (field (name "PART NUMBER") "CC0201_220NF_6.3V_20%_X5R")
        (field (name "VOLTAGE") "6.3V")
        (field (name "AUTHOR") "CERN DEM JLC")
      )
      (libsource (lib "Capacitors") (part "Capacitor - non polarized"))
    )
    (comp (ref "C555")
      (value "220nF")
      (footprint "CAPC0603X33N")
      (description "Non-polarised capacitor")
      (fields
        (field (name "PART NUMBER") "CC0201_220NF_6.3V_20%_X5R")
        (field (name "VOLTAGE") "6.3V")
        (field (name "AUTHOR") "CERN DEM JLC")
      )
      (libsource (lib "Capacitors") (part "Capacitor - non polarized"))
    )
    (comp (ref "C556")
      (value "220nF")
      (footprint "CAPC0603X33N")
      (description "Non-polarised capacitor")
      (fields
        (field (name "PART NUMBER") "CC0201_220NF_6.3V_20%_X5R")
        (field (name "VOLTAGE") "6.3V")
        (field (name "AUTHOR") "CERN DEM JLC")
      )
      (libsource (lib "Capacitors") (part "Capacitor - non polarized"))
    )
    (comp (ref "C557")
      (value "220nF")
      (footprint "CAPC0603X33N")
      (description "Non-polarised capacitor")
      (fields
        (field (name "PART NUMBER") "CC0201_220NF_6.3V_20%_X5R")
        (field (name "VOLTAGE") "6.3V")
        (field (name "AUTHOR") "CERN DEM JLC")
      )
      (libsource (lib "Capacitors") (part "Capacitor - non polarized"))
    )
    (comp (ref "C558")
      (value "220nF")
      (footprint "CAPC0603X33N")
      (description "Non-polarised capacitor")
      (fields
        (field (name "PART NUMBER") "CC0201_220NF_6.3V_20%_X5R")
        (field (name "VOLTAGE") "6.3V")
        (field (name "AUTHOR") "CERN DEM JLC")
      )
      (libsource (lib "Capacitors") (part "Capacitor - non polarized"))
    )
    (comp (ref "C559")
      (value "220nF")
      (footprint "CAPC0603X33N")
      (description "Non-polarised capacitor")
      (fields
        (field (name "PART NUMBER") "CC0201_220NF_6.3V_20%_X5R")
        (field (name "VOLTAGE") "6.3V")
        (field (name "AUTHOR") "CERN DEM JLC")
      )
      (libsource (lib "Capacitors") (part "Capacitor - non polarized"))
    )
    (comp (ref "C560")
      (value "220nF")
      (footprint "CAPC0603X33N")
      (description "Non-polarised capacitor")
      (fields
        (field (name "PART NUMBER") "CC0201_220NF_6.3V_20%_X5R")
        (field (name "VOLTAGE") "6.3V")
        (field (name "AUTHOR") "CERN DEM JLC")
      )
      (libsource (lib "Capacitors") (part "Capacitor - non polarized"))
    )
    (comp (ref "C561")
      (value "220nF")
      (footprint "CAPC0603X33N")
      (description "Non-polarised capacitor")
      (fields
        (field (name "PART NUMBER") "CC0201_220NF_6.3V_20%_X5R")
        (field (name "VOLTAGE") "6.3V")
        (field (name "AUTHOR") "CERN DEM JLC")
      )
      (libsource (lib "Capacitors") (part "Capacitor - non polarized"))
    )
    (comp (ref "C562")
      (value "220nF")
      (footprint "CAPC0603X33N")
      (description "Non-polarised capacitor")
      (fields
        (field (name "PART NUMBER") "CC0201_220NF_6.3V_20%_X5R")
        (field (name "VOLTAGE") "6.3V")
        (field (name "AUTHOR") "CERN DEM JLC")
      )
      (libsource (lib "Capacitors") (part "Capacitor - non polarized"))
    )
    (comp (ref "C563")
      (value "220nF")
      (footprint "CAPC0603X33N")
      (description "Non-polarised capacitor")
      (fields
        (field (name "PART NUMBER") "CC0201_220NF_6.3V_20%_X5R")
        (field (name "VOLTAGE") "6.3V")
        (field (name "AUTHOR") "CERN DEM JLC")
      )
      (libsource (lib "Capacitors") (part "Capacitor - non polarized"))
    )
    (comp (ref "C564")
      (value "220nF")
      (footprint "CAPC0603X33N")
      (description "Non-polarised capacitor")
      (fields
        (field (name "PART NUMBER") "CC0201_220NF_6.3V_20%_X5R")
        (field (name "VOLTAGE") "6.3V")
        (field (name "AUTHOR") "CERN DEM JLC")
      )
      (libsource (lib "Capacitors") (part "Capacitor - non polarized"))
    )
    (comp (ref "C565")
      (value "220nF")
      (footprint "CAPC0603X33N")
      (description "Non-polarised capacitor")
      (fields
        (field (name "PART NUMBER") "CC0201_220NF_6.3V_20%_X5R")
        (field (name "VOLTAGE") "6.3V")
        (field (name "AUTHOR") "CERN DEM JLC")
      )
      (libsource (lib "Capacitors") (part "Capacitor - non polarized"))
    )
    (comp (ref "C566")
      (value "220nF")
      (footprint "CAPC0603X33N")
      (description "Non-polarised capacitor")
      (fields
        (field (name "PART NUMBER") "CC0201_220NF_6.3V_20%_X5R")
        (field (name "VOLTAGE") "6.3V")
        (field (name "AUTHOR") "CERN DEM JLC")
      )
      (libsource (lib "Capacitors") (part "Capacitor - non polarized"))
    )
    (comp (ref "C576")
      (value "4.7uF")
      (footprint "CAPC1608X87N")
      (description "Non-polarised capacitor")
      (fields
        (field (name "PART NUMBER") "CC0603_4.7UF_6.3V_10%_X5R")
        (field (name "VOLTAGE") "6.3V")
        (field (name "AUTHOR") "CERN DEM JLC")
      )
      (libsource (lib "Capacitors") (part "Capacitor - non polarized"))
    )
    (comp (ref "C577")
      (value "4.7uF")
      (footprint "CAPC1608X87N")
      (description "Non-polarised capacitor")
      (fields
        (field (name "PART NUMBER") "CC0603_4.7UF_6.3V_10%_X5R")
        (field (name "VOLTAGE") "6.3V")
        (field (name "AUTHOR") "CERN DEM JLC")
      )
      (libsource (lib "Capacitors") (part "Capacitor - non polarized"))
    )
    (comp (ref "C578")
      (value "4.7uF")
      (footprint "CAPC1608X87N")
      (description "Non-polarised capacitor")
      (fields
        (field (name "PART NUMBER") "CC0603_4.7UF_6.3V_10%_X5R")
        (field (name "VOLTAGE") "6.3V")
        (field (name "AUTHOR") "CERN DEM JLC")
      )
      (libsource (lib "Capacitors") (part "Capacitor - non polarized"))
    )
    (comp (ref "C579")
      (value "4.7uF")
      (footprint "CAPC1608X87N")
      (description "Non-polarised capacitor")
      (fields
        (field (name "PART NUMBER") "CC0603_4.7UF_6.3V_10%_X5R")
        (field (name "VOLTAGE") "6.3V")
        (field (name "AUTHOR") "CERN DEM JLC")
      )
      (libsource (lib "Capacitors") (part "Capacitor - non polarized"))
    )
    (comp (ref "C580")
      (value "4.7uF")
      (footprint "CAPC1608X87N")
      (description "Non-polarised capacitor")
      (fields
        (field (name "PART NUMBER") "CC0603_4.7UF_6.3V_10%_X5R")
        (field (name "VOLTAGE") "6.3V")
        (field (name "AUTHOR") "CERN DEM JLC")
      )
      (libsource (lib "Capacitors") (part "Capacitor - non polarized"))
    )
    (comp (ref "C581")
      (value "4.7uF")
      (footprint "CAPC1608X87N")
      (description "Non-polarised capacitor")
      (fields
        (field (name "PART NUMBER") "CC0603_4.7UF_6.3V_10%_X5R")
        (field (name "VOLTAGE") "6.3V")
        (field (name "AUTHOR") "CERN DEM JLC")
      )
      (libsource (lib "Capacitors") (part "Capacitor - non polarized"))
    )
    (comp (ref "C582")
      (value "4.7uF")
      (footprint "CAPC1608X87N")
      (description "Non-polarised capacitor")
      (fields
        (field (name "PART NUMBER") "CC0603_4.7UF_6.3V_10%_X5R")
        (field (name "VOLTAGE") "6.3V")
        (field (name "AUTHOR") "CERN DEM JLC")
      )
      (libsource (lib "Capacitors") (part "Capacitor - non polarized"))
    )
    (comp (ref "C583")
      (value "4.7uF")
      (footprint "CAPC1608X87N")
      (description "Non-polarised capacitor")
      (fields
        (field (name "PART NUMBER") "CC0603_4.7UF_6.3V_10%_X5R")
        (field (name "VOLTAGE") "6.3V")
        (field (name "AUTHOR") "CERN DEM JLC")
      )
      (libsource (lib "Capacitors") (part "Capacitor - non polarized"))
    )
    (comp (ref "C585")
      (value "4.7uF")
      (footprint "CAPC1608X87N")
      (description "Non-polarised capacitor")
      (fields
        (field (name "PART NUMBER") "CC0603_4.7UF_6.3V_10%_X5R")
        (field (name "VOLTAGE") "6.3V")
        (field (name "AUTHOR") "CERN DEM JLC")
      )
      (libsource (lib "Capacitors") (part "Capacitor - non polarized"))
    )
    (comp (ref "C586")
      (value "4.7uF")
      (footprint "CAPC1608X87N")
      (description "Non-polarised capacitor")
      (fields
        (field (name "PART NUMBER") "CC0603_4.7UF_6.3V_10%_X5R")
        (field (name "VOLTAGE") "6.3V")
        (field (name "AUTHOR") "CERN DEM JLC")
      )
      (libsource (lib "Capacitors") (part "Capacitor - non polarized"))
    )
    (comp (ref "C587")
      (value "100uF")
      (footprint "CAPC3225X270N")
      (description "Non-polarised capacitor")
      (fields
        (field (name "PART NUMBER") "CC1210_100UF_6.3V_20%_X5R")
        (field (name "VOLTAGE") "6.3V")
        (field (name "AUTHOR") "CERN DEM JLC")
      )
      (libsource (lib "Capacitors") (part "Capacitor - non polarized"))
    )
    (comp (ref "C588")
      (value "4.7uF")
      (footprint "CAPC1608X87N")
      (description "Non-polarised capacitor")
      (fields
        (field (name "PART NUMBER") "CC0603_4.7UF_6.3V_10%_X5R")
        (field (name "VOLTAGE") "6.3V")
        (field (name "AUTHOR") "CERN DEM JLC")
      )
      (libsource (lib "Capacitors") (part "Capacitor - non polarized"))
    )
    (comp (ref "C589")
      (value "4.7uF")
      (footprint "CAPC1608X87N")
      (description "Non-polarised capacitor")
      (fields
        (field (name "PART NUMBER") "CC0603_4.7UF_6.3V_10%_X5R")
        (field (name "VOLTAGE") "6.3V")
        (field (name "AUTHOR") "CERN DEM JLC")
      )
      (libsource (lib "Capacitors") (part "Capacitor - non polarized"))
    )
    (comp (ref "C591")
      (value "4.7uF")
      (footprint "CAPC1608X87N")
      (description "Non-polarised capacitor")
      (fields
        (field (name "PART NUMBER") "CC0603_4.7UF_6.3V_10%_X5R")
        (field (name "VOLTAGE") "6.3V")
        (field (name "AUTHOR") "CERN DEM JLC")
      )
      (libsource (lib "Capacitors") (part "Capacitor - non polarized"))
    )
    (comp (ref "C592")
      (value "100uF")
      (footprint "CAPC3225X270N")
      (description "Non-polarised capacitor")
      (fields
        (field (name "PART NUMBER") "CC1210_100UF_6.3V_20%_X5R")
        (field (name "VOLTAGE") "6.3V")
        (field (name "AUTHOR") "CERN DEM JLC")
      )
      (libsource (lib "Capacitors") (part "Capacitor - non polarized"))
    )
    (comp (ref "C593")
      (value "100uF")
      (footprint "CAPC3225X270N")
      (description "Non-polarised capacitor")
      (fields
        (field (name "PART NUMBER") "CC1210_100UF_6.3V_20%_X5R")
        (field (name "VOLTAGE") "6.3V")
        (field (name "AUTHOR") "CERN DEM JLC")
      )
      (libsource (lib "Capacitors") (part "Capacitor - non polarized"))
    )
    (comp (ref "C594")
      (value "4.7uF")
      (footprint "CAPC1608X87N")
      (description "Non-polarised capacitor")
      (fields
        (field (name "PART NUMBER") "CC0603_4.7UF_6.3V_10%_X5R")
        (field (name "VOLTAGE") "6.3V")
        (field (name "AUTHOR") "CERN DEM JLC")
      )
      (libsource (lib "Capacitors") (part "Capacitor - non polarized"))
    )
    (comp (ref "C596")
      (value "4.7uF")
      (footprint "CAPC1608X87N")
      (description "Non-polarised capacitor")
      (fields
        (field (name "PART NUMBER") "CC0603_4.7UF_6.3V_10%_X5R")
        (field (name "VOLTAGE") "6.3V")
        (field (name "AUTHOR") "CERN DEM JLC")
      )
      (libsource (lib "Capacitors") (part "Capacitor - non polarized"))
    )
    (comp (ref "C597")
      (value "4.7uF")
      (footprint "CAPC1608X87N")
      (description "Non-polarised capacitor")
      (fields
        (field (name "PART NUMBER") "CC0603_4.7UF_6.3V_10%_X5R")
        (field (name "VOLTAGE") "6.3V")
        (field (name "AUTHOR") "CERN DEM JLC")
      )
      (libsource (lib "Capacitors") (part "Capacitor - non polarized"))
    )
    (comp (ref "C598")
      (value "4.7uF")
      (footprint "CAPC1608X87N")
      (description "Non-polarised capacitor")
      (fields
        (field (name "PART NUMBER") "CC0603_4.7UF_6.3V_10%_X5R")
        (field (name "VOLTAGE") "6.3V")
        (field (name "AUTHOR") "CERN DEM JLC")
      )
      (libsource (lib "Capacitors") (part "Capacitor - non polarized"))
    )
    (comp (ref "C599")
      (value "22nF")
      (footprint "CAPC0603X33N")
      (description "Non-polarised capacitor")
      (fields
        (field (name "PART NUMBER") "CC0201_22NF_6.3V_10%_X5R")
        (field (name "VOLTAGE") "6.3V")
        (field (name "AUTHOR") "CERN DEM JLC")
      )
      (libsource (lib "Capacitors") (part "Capacitor - non polarized"))
    )
    (comp (ref "C600")
      (value "22nF")
      (footprint "CAPC0603X33N")
      (description "Non-polarised capacitor")
      (fields
        (field (name "PART NUMBER") "CC0201_22NF_6.3V_10%_X5R")
        (field (name "VOLTAGE") "6.3V")
        (field (name "AUTHOR") "CERN DEM JLC")
      )
      (libsource (lib "Capacitors") (part "Capacitor - non polarized"))
    )
    (comp (ref "C601")
      (value "22nF")
      (footprint "CAPC0603X33N")
      (description "Non-polarised capacitor")
      (fields
        (field (name "PART NUMBER") "CC0201_22NF_6.3V_10%_X5R")
        (field (name "VOLTAGE") "6.3V")
        (field (name "AUTHOR") "CERN DEM JLC")
      )
      (libsource (lib "Capacitors") (part "Capacitor - non polarized"))
    )
    (comp (ref "C602")
      (value "100uF")
      (footprint "CAPC3225X270N")
      (description "Non-polarised capacitor")
      (fields
        (field (name "PART NUMBER") "CC1210_100UF_6.3V_20%_X5R")
        (field (name "VOLTAGE") "6.3V")
        (field (name "AUTHOR") "CERN DEM JLC")
      )
      (libsource (lib "Capacitors") (part "Capacitor - non polarized"))
    )
    (comp (ref "C603")
      (value "470nF")
      (footprint "CAPC0603X33N")
      (description "Non-polarised capacitor")
      (fields
        (field (name "PART NUMBER") "CC0201_470NF_4V_20%_X5R")
        (field (name "VOLTAGE") "4V")
        (field (name "AUTHOR") "CERN DEM JLC")
      )
      (libsource (lib "Capacitors") (part "Capacitor - non polarized"))
    )
    (comp (ref "C604")
      (value "100nF")
      (footprint "CAPC0603X33N")
      (description "Non-polarised capacitor")
      (fields
        (field (name "PART NUMBER") "CC0201_100NF_6.3V_10%_X5R")
        (field (name "VOLTAGE") "6.3V")
        (field (name "AUTHOR") "CERN DEM JLC")
      )
      (libsource (lib "Capacitors") (part "Capacitor - non polarized"))
    )
    (comp (ref "C605")
      (value "4.7uF")
      (footprint "CAPC1608X87N")
      (description "Non-polarised capacitor")
      (fields
        (field (name "PART NUMBER") "CC0603_4.7UF_6.3V_10%_X5R")
        (field (name "VOLTAGE") "6.3V")
        (field (name "AUTHOR") "CERN DEM JLC")
      )
      (libsource (lib "Capacitors") (part "Capacitor - non polarized"))
    )
    (comp (ref "C606")
      (value "4.7uF")
      (footprint "CAPC1608X87N")
      (description "Non-polarised capacitor")
      (fields
        (field (name "PART NUMBER") "CC0603_4.7UF_6.3V_10%_X5R")
        (field (name "VOLTAGE") "6.3V")
        (field (name "AUTHOR") "CERN DEM JLC")
      )
      (libsource (lib "Capacitors") (part "Capacitor - non polarized"))
    )
    (comp (ref "C607")
      (value "4.7uF")
      (footprint "CAPC1608X87N")
      (description "Non-polarised capacitor")
      (fields
        (field (name "PART NUMBER") "CC0603_4.7UF_6.3V_10%_X5R")
        (field (name "VOLTAGE") "6.3V")
        (field (name "AUTHOR") "CERN DEM JLC")
      )
      (libsource (lib "Capacitors") (part "Capacitor - non polarized"))
    )
    (comp (ref "C608")
      (value "4.7uF")
      (footprint "CAPC1608X87N")
      (description "Non-polarised capacitor")
      (fields
        (field (name "PART NUMBER") "CC0603_4.7UF_6.3V_10%_X5R")
        (field (name "VOLTAGE") "6.3V")
        (field (name "AUTHOR") "CERN DEM JLC")
      )
      (libsource (lib "Capacitors") (part "Capacitor - non polarized"))
    )
    (comp (ref "C609")
      (value "4.7uF")
      (footprint "CAPC1608X87N")
      (description "Non-polarised capacitor")
      (fields
        (field (name "PART NUMBER") "CC0603_4.7UF_6.3V_10%_X5R")
        (field (name "VOLTAGE") "6.3V")
        (field (name "AUTHOR") "CERN DEM JLC")
      )
      (libsource (lib "Capacitors") (part "Capacitor - non polarized"))
    )
    (comp (ref "C610")
      (value "4.7uF")
      (footprint "CAPC1608X87N")
      (description "Non-polarised capacitor")
      (fields
        (field (name "PART NUMBER") "CC0603_4.7UF_6.3V_10%_X5R")
        (field (name "VOLTAGE") "6.3V")
        (field (name "AUTHOR") "CERN DEM JLC")
      )
      (libsource (lib "Capacitors") (part "Capacitor - non polarized"))
    )
    (comp (ref "C611")
      (value "4.7uF")
      (footprint "CAPC1608X87N")
      (description "Non-polarised capacitor")
      (fields
        (field (name "PART NUMBER") "CC0603_4.7UF_6.3V_10%_X5R")
        (field (name "VOLTAGE") "6.3V")
        (field (name "AUTHOR") "CERN DEM JLC")
      )
      (libsource (lib "Capacitors") (part "Capacitor - non polarized"))
    )
    (comp (ref "C612")
      (value "100uF")
      (footprint "CAPC3225X270N")
      (description "Non-polarised capacitor")
      (fields
        (field (name "PART NUMBER") "CC1210_100UF_6.3V_20%_X5R")
        (field (name "VOLTAGE") "6.3V")
        (field (name "AUTHOR") "CERN DEM JLC")
      )
      (libsource (lib "Capacitors") (part "Capacitor - non polarized"))
    )
    (comp (ref "C614")
      (value "470nF")
      (footprint "CAPC0603X33N")
      (description "Non-polarised capacitor")
      (fields
        (field (name "PART NUMBER") "CC0201_470NF_4V_20%_X5R")
        (field (name "VOLTAGE") "4V")
        (field (name "AUTHOR") "CERN DEM JLC")
      )
      (libsource (lib "Capacitors") (part "Capacitor - non polarized"))
    )
    (comp (ref "C615")
      (value "470nF")
      (footprint "CAPC0603X33N")
      (description "Non-polarised capacitor")
      (fields
        (field (name "PART NUMBER") "CC0201_470NF_4V_20%_X5R")
        (field (name "VOLTAGE") "4V")
        (field (name "AUTHOR") "CERN DEM JLC")
      )
      (libsource (lib "Capacitors") (part "Capacitor - non polarized"))
    )
    (comp (ref "C636")
      (value "4.7uF")
      (footprint "CAPC1608X87N")
      (description "Non-polarised capacitor")
      (fields
        (field (name "PART NUMBER") "CC0603_4.7UF_6.3V_10%_X5R")
        (field (name "VOLTAGE") "6.3V")
        (field (name "AUTHOR") "CERN DEM JLC")
      )
      (libsource (lib "Capacitors") (part "Capacitor - non polarized"))
    )
    (comp (ref "C637")
      (value "4.7uF")
      (footprint "CAPC1608X87N")
      (description "Non-polarised capacitor")
      (fields
        (field (name "PART NUMBER") "CC0603_4.7UF_6.3V_10%_X5R")
        (field (name "VOLTAGE") "6.3V")
        (field (name "AUTHOR") "CERN DEM JLC")
      )
      (libsource (lib "Capacitors") (part "Capacitor - non polarized"))
    )
    (comp (ref "C638")
      (value "100uF")
      (footprint "CAPC3225X270N")
      (description "Non-polarised capacitor")
      (fields
        (field (name "PART NUMBER") "CC1210_100UF_6.3V_20%_X5R")
        (field (name "VOLTAGE") "6.3V")
        (field (name "AUTHOR") "CERN DEM JLC")
      )
      (libsource (lib "Capacitors") (part "Capacitor - non polarized"))
    )
    (comp (ref "C639")
      (value "470nF")
      (footprint "CAPC0603X33N")
      (description "Non-polarised capacitor")
      (fields
        (field (name "PART NUMBER") "CC0201_470NF_4V_20%_X5R")
        (field (name "VOLTAGE") "4V")
        (field (name "AUTHOR") "CERN DEM JLC")
      )
      (libsource (lib "Capacitors") (part "Capacitor - non polarized"))
    )
    (comp (ref "C640")
      (value "470nF")
      (footprint "CAPC0603X33N")
      (description "Non-polarised capacitor")
      (fields
        (field (name "PART NUMBER") "CC0201_470NF_4V_20%_X5R")
        (field (name "VOLTAGE") "4V")
        (field (name "AUTHOR") "CERN DEM JLC")
      )
      (libsource (lib "Capacitors") (part "Capacitor - non polarized"))
    )
    (comp (ref "C641")
      (value "470nF")
      (footprint "CAPC0603X33N")
      (description "Non-polarised capacitor")
      (fields
        (field (name "PART NUMBER") "CC0201_470NF_4V_20%_X5R")
        (field (name "VOLTAGE") "4V")
        (field (name "AUTHOR") "CERN DEM JLC")
      )
      (libsource (lib "Capacitors") (part "Capacitor - non polarized"))
    )
    (comp (ref "C642")
      (value "470nF")
      (footprint "CAPC0603X33N")
      (description "Non-polarised capacitor")
      (fields
        (field (name "PART NUMBER") "CC0201_470NF_4V_20%_X5R")
        (field (name "VOLTAGE") "4V")
        (field (name "AUTHOR") "CERN DEM JLC")
      )
      (libsource (lib "Capacitors") (part "Capacitor - non polarized"))
    )
    (comp (ref "C643")
      (value "470nF")
      (footprint "CAPC0603X33N")
      (description "Non-polarised capacitor")
      (fields
        (field (name "PART NUMBER") "CC0201_470NF_4V_20%_X5R")
        (field (name "VOLTAGE") "4V")
        (field (name "AUTHOR") "CERN DEM JLC")
      )
      (libsource (lib "Capacitors") (part "Capacitor - non polarized"))
    )
    (comp (ref "C644")
      (value "4.7uF")
      (footprint "CAPC1608X87N")
      (description "Non-polarised capacitor")
      (fields
        (field (name "PART NUMBER") "CC0603_4.7UF_6.3V_10%_X5R")
        (field (name "VOLTAGE") "6.3V")
        (field (name "AUTHOR") "CERN DEM JLC")
      )
      (libsource (lib "Capacitors") (part "Capacitor - non polarized"))
    )
    (comp (ref "C645")
      (value "4.7uF")
      (footprint "CAPC1608X87N")
      (description "Non-polarised capacitor")
      (fields
        (field (name "PART NUMBER") "CC0603_4.7UF_6.3V_10%_X5R")
        (field (name "VOLTAGE") "6.3V")
        (field (name "AUTHOR") "CERN DEM JLC")
      )
      (libsource (lib "Capacitors") (part "Capacitor - non polarized"))
    )
    (comp (ref "C646")
      (value "4.7uF")
      (footprint "CAPC1608X87N")
      (description "Non-polarised capacitor")
      (fields
        (field (name "PART NUMBER") "CC0603_4.7UF_6.3V_10%_X5R")
        (field (name "VOLTAGE") "6.3V")
        (field (name "AUTHOR") "CERN DEM JLC")
      )
      (libsource (lib "Capacitors") (part "Capacitor - non polarized"))
    )
    (comp (ref "C647")
      (value "470nF")
      (footprint "CAPC0603X33N")
      (description "Non-polarised capacitor")
      (fields
        (field (name "PART NUMBER") "CC0201_470NF_4V_20%_X5R")
        (field (name "VOLTAGE") "4V")
        (field (name "AUTHOR") "CERN DEM JLC")
      )
      (libsource (lib "Capacitors") (part "Capacitor - non polarized"))
    )
    (comp (ref "C648")
      (value "470nF")
      (footprint "CAPC0603X33N")
      (description "Non-polarised capacitor")
      (fields
        (field (name "PART NUMBER") "CC0201_470NF_4V_20%_X5R")
        (field (name "VOLTAGE") "4V")
        (field (name "AUTHOR") "CERN DEM JLC")
      )
      (libsource (lib "Capacitors") (part "Capacitor - non polarized"))
    )
    (comp (ref "C649")
      (value "470nF")
      (footprint "CAPC0603X33N")
      (description "Non-polarised capacitor")
      (fields
        (field (name "PART NUMBER") "CC0201_470NF_4V_20%_X5R")
        (field (name "VOLTAGE") "4V")
        (field (name "AUTHOR") "CERN DEM JLC")
      )
      (libsource (lib "Capacitors") (part "Capacitor - non polarized"))
    )
    (comp (ref "C650")
      (value "470nF")
      (footprint "CAPC0603X33N")
      (description "Non-polarised capacitor")
      (fields
        (field (name "PART NUMBER") "CC0201_470NF_4V_20%_X5R")
        (field (name "VOLTAGE") "4V")
        (field (name "AUTHOR") "CERN DEM JLC")
      )
      (libsource (lib "Capacitors") (part "Capacitor - non polarized"))
    )
    (comp (ref "C651")
      (value "470nF")
      (footprint "CAPC0603X33N")
      (description "Non-polarised capacitor")
      (fields
        (field (name "PART NUMBER") "CC0201_470NF_4V_20%_X5R")
        (field (name "VOLTAGE") "4V")
        (field (name "AUTHOR") "CERN DEM JLC")
      )
      (libsource (lib "Capacitors") (part "Capacitor - non polarized"))
    )
    (comp (ref "C652")
      (value "4.7uF")
      (footprint "CAPC1608X87N")
      (description "Non-polarised capacitor")
      (fields
        (field (name "PART NUMBER") "CC0603_4.7UF_6.3V_10%_X5R")
        (field (name "VOLTAGE") "6.3V")
        (field (name "AUTHOR") "CERN DEM JLC")
      )
      (libsource (lib "Capacitors") (part "Capacitor - non polarized"))
    )
    (comp (ref "C653")
      (value "4.7uF")
      (footprint "CAPC1608X87N")
      (description "Non-polarised capacitor")
      (fields
        (field (name "PART NUMBER") "CC0603_4.7UF_6.3V_10%_X5R")
        (field (name "VOLTAGE") "6.3V")
        (field (name "AUTHOR") "CERN DEM JLC")
      )
      (libsource (lib "Capacitors") (part "Capacitor - non polarized"))
    )
    (comp (ref "C654")
      (value "4.7uF")
      (footprint "CAPC1608X87N")
      (description "Non-polarised capacitor")
      (fields
        (field (name "PART NUMBER") "CC0603_4.7UF_6.3V_10%_X5R")
        (field (name "VOLTAGE") "6.3V")
        (field (name "AUTHOR") "CERN DEM JLC")
      )
      (libsource (lib "Capacitors") (part "Capacitor - non polarized"))
    )
    (comp (ref "C655")
      (value "470nF")
      (footprint "CAPC0603X33N")
      (description "Non-polarised capacitor")
      (fields
        (field (name "PART NUMBER") "CC0201_470NF_4V_20%_X5R")
        (field (name "VOLTAGE") "4V")
        (field (name "AUTHOR") "CERN DEM JLC")
      )
      (libsource (lib "Capacitors") (part "Capacitor - non polarized"))
    )
    (comp (ref "C656")
      (value "470nF")
      (footprint "CAPC0603X33N")
      (description "Non-polarised capacitor")
      (fields
        (field (name "PART NUMBER") "CC0201_470NF_4V_20%_X5R")
        (field (name "VOLTAGE") "4V")
        (field (name "AUTHOR") "CERN DEM JLC")
      )
      (libsource (lib "Capacitors") (part "Capacitor - non polarized"))
    )
    (comp (ref "C657")
      (value "470nF")
      (footprint "CAPC0603X33N")
      (description "Non-polarised capacitor")
      (fields
        (field (name "PART NUMBER") "CC0201_470NF_4V_20%_X5R")
        (field (name "VOLTAGE") "4V")
        (field (name "AUTHOR") "CERN DEM JLC")
      )
      (libsource (lib "Capacitors") (part "Capacitor - non polarized"))
    )
    (comp (ref "C658")
      (value "470nF")
      (footprint "CAPC0603X33N")
      (description "Non-polarised capacitor")
      (fields
        (field (name "PART NUMBER") "CC0201_470NF_4V_20%_X5R")
        (field (name "VOLTAGE") "4V")
        (field (name "AUTHOR") "CERN DEM JLC")
      )
      (libsource (lib "Capacitors") (part "Capacitor - non polarized"))
    )
    (comp (ref "C659")
      (value "470nF")
      (footprint "CAPC0603X33N")
      (description "Non-polarised capacitor")
      (fields
        (field (name "PART NUMBER") "CC0201_470NF_4V_20%_X5R")
        (field (name "VOLTAGE") "4V")
        (field (name "AUTHOR") "CERN DEM JLC")
      )
      (libsource (lib "Capacitors") (part "Capacitor - non polarized"))
    )
    (comp (ref "C660")
      (value "4.7uF")
      (footprint "CAPC1608X87N")
      (description "Non-polarised capacitor")
      (fields
        (field (name "PART NUMBER") "CC0603_4.7UF_6.3V_10%_X5R")
        (field (name "VOLTAGE") "6.3V")
        (field (name "AUTHOR") "CERN DEM JLC")
      )
      (libsource (lib "Capacitors") (part "Capacitor - non polarized"))
    )
    (comp (ref "C661")
      (value "4.7uF")
      (footprint "CAPC1608X87N")
      (description "Non-polarised capacitor")
      (fields
        (field (name "PART NUMBER") "CC0603_4.7UF_6.3V_10%_X5R")
        (field (name "VOLTAGE") "6.3V")
        (field (name "AUTHOR") "CERN DEM JLC")
      )
      (libsource (lib "Capacitors") (part "Capacitor - non polarized"))
    )
    (comp (ref "C662")
      (value "4.7uF")
      (footprint "CAPC1608X87N")
      (description "Non-polarised capacitor")
      (fields
        (field (name "PART NUMBER") "CC0603_4.7UF_6.3V_10%_X5R")
        (field (name "VOLTAGE") "6.3V")
        (field (name "AUTHOR") "CERN DEM JLC")
      )
      (libsource (lib "Capacitors") (part "Capacitor - non polarized"))
    )
    (comp (ref "C663")
      (value "470nF")
      (footprint "CAPC0603X33N")
      (description "Non-polarised capacitor")
      (fields
        (field (name "PART NUMBER") "CC0201_470NF_4V_20%_X5R")
        (field (name "VOLTAGE") "4V")
        (field (name "AUTHOR") "CERN DEM JLC")
      )
      (libsource (lib "Capacitors") (part "Capacitor - non polarized"))
    )
    (comp (ref "C664")
      (value "470nF")
      (footprint "CAPC0603X33N")
      (description "Non-polarised capacitor")
      (fields
        (field (name "PART NUMBER") "CC0201_470NF_4V_20%_X5R")
        (field (name "VOLTAGE") "4V")
        (field (name "AUTHOR") "CERN DEM JLC")
      )
      (libsource (lib "Capacitors") (part "Capacitor - non polarized"))
    )
    (comp (ref "C665")
      (value "470nF")
      (footprint "CAPC0603X33N")
      (description "Non-polarised capacitor")
      (fields
        (field (name "PART NUMBER") "CC0201_470NF_4V_20%_X5R")
        (field (name "VOLTAGE") "4V")
        (field (name "AUTHOR") "CERN DEM JLC")
      )
      (libsource (lib "Capacitors") (part "Capacitor - non polarized"))
    )
    (comp (ref "C666")
      (value "470nF")
      (footprint "CAPC0603X33N")
      (description "Non-polarised capacitor")
      (fields
        (field (name "PART NUMBER") "CC0201_470NF_4V_20%_X5R")
        (field (name "VOLTAGE") "4V")
        (field (name "AUTHOR") "CERN DEM JLC")
      )
      (libsource (lib "Capacitors") (part "Capacitor - non polarized"))
    )
    (comp (ref "C667")
      (value "470nF")
      (footprint "CAPC0603X33N")
      (description "Non-polarised capacitor")
      (fields
        (field (name "PART NUMBER") "CC0201_470NF_4V_20%_X5R")
        (field (name "VOLTAGE") "4V")
        (field (name "AUTHOR") "CERN DEM JLC")
      )
      (libsource (lib "Capacitors") (part "Capacitor - non polarized"))
    )
    (comp (ref "C668")
      (value "4.7uF")
      (footprint "CAPC1608X87N")
      (description "Non-polarised capacitor")
      (fields
        (field (name "PART NUMBER") "CC0603_4.7UF_6.3V_10%_X5R")
        (field (name "VOLTAGE") "6.3V")
        (field (name "AUTHOR") "CERN DEM JLC")
      )
      (libsource (lib "Capacitors") (part "Capacitor - non polarized"))
    )
    (comp (ref "C669")
      (value "4.7uF")
      (footprint "CAPC1608X87N")
      (description "Non-polarised capacitor")
      (fields
        (field (name "PART NUMBER") "CC0603_4.7UF_6.3V_10%_X5R")
        (field (name "VOLTAGE") "6.3V")
        (field (name "AUTHOR") "CERN DEM JLC")
      )
      (libsource (lib "Capacitors") (part "Capacitor - non polarized"))
    )
    (comp (ref "C670")
      (value "4.7uF")
      (footprint "CAPC1608X87N")
      (description "Non-polarised capacitor")
      (fields
        (field (name "PART NUMBER") "CC0603_4.7UF_6.3V_10%_X5R")
        (field (name "VOLTAGE") "6.3V")
        (field (name "AUTHOR") "CERN DEM JLC")
      )
      (libsource (lib "Capacitors") (part "Capacitor - non polarized"))
    )
    (comp (ref "C671")
      (value "470nF")
      (footprint "CAPC0603X33N")
      (description "Non-polarised capacitor")
      (fields
        (field (name "PART NUMBER") "CC0201_470NF_4V_20%_X5R")
        (field (name "VOLTAGE") "4V")
        (field (name "AUTHOR") "CERN DEM JLC")
      )
      (libsource (lib "Capacitors") (part "Capacitor - non polarized"))
    )
    (comp (ref "C672")
      (value "470nF")
      (footprint "CAPC0603X33N")
      (description "Non-polarised capacitor")
      (fields
        (field (name "PART NUMBER") "CC0201_470NF_4V_20%_X5R")
        (field (name "VOLTAGE") "4V")
        (field (name "AUTHOR") "CERN DEM JLC")
      )
      (libsource (lib "Capacitors") (part "Capacitor - non polarized"))
    )
    (comp (ref "C673")
      (value "470nF")
      (footprint "CAPC0603X33N")
      (description "Non-polarised capacitor")
      (fields
        (field (name "PART NUMBER") "CC0201_470NF_4V_20%_X5R")
        (field (name "VOLTAGE") "4V")
        (field (name "AUTHOR") "CERN DEM JLC")
      )
      (libsource (lib "Capacitors") (part "Capacitor - non polarized"))
    )
    (comp (ref "C674")
      (value "470nF")
      (footprint "CAPC0603X33N")
      (description "Non-polarised capacitor")
      (fields
        (field (name "PART NUMBER") "CC0201_470NF_4V_20%_X5R")
        (field (name "VOLTAGE") "4V")
        (field (name "AUTHOR") "CERN DEM JLC")
      )
      (libsource (lib "Capacitors") (part "Capacitor - non polarized"))
    )
    (comp (ref "C675")
      (value "470nF")
      (footprint "CAPC0603X33N")
      (description "Non-polarised capacitor")
      (fields
        (field (name "PART NUMBER") "CC0201_470NF_4V_20%_X5R")
        (field (name "VOLTAGE") "4V")
        (field (name "AUTHOR") "CERN DEM JLC")
      )
      (libsource (lib "Capacitors") (part "Capacitor - non polarized"))
    )
    (comp (ref "C676")
      (value "100uF")
      (footprint "CAPC3225X270N")
      (description "Non-polarised capacitor")
      (fields
        (field (name "PART NUMBER") "CC1210_100UF_6.3V_20%_X5R")
        (field (name "VOLTAGE") "6.3V")
        (field (name "AUTHOR") "CERN DEM JLC")
      )
      (libsource (lib "Capacitors") (part "Capacitor - non polarized"))
    )
    (comp (ref "C677")
      (value "100uF")
      (footprint "CAPC3225X270N")
      (description "Non-polarised capacitor")
      (fields
        (field (name "PART NUMBER") "CC1210_100UF_6.3V_20%_X5R")
        (field (name "VOLTAGE") "6.3V")
        (field (name "AUTHOR") "CERN DEM JLC")
      )
      (libsource (lib "Capacitors") (part "Capacitor - non polarized"))
    )
    (comp (ref "C678")
      (value "100uF")
      (footprint "CAPC3225X270N")
      (description "Non-polarised capacitor")
      (fields
        (field (name "PART NUMBER") "CC1210_100UF_6.3V_20%_X5R")
        (field (name "VOLTAGE") "6.3V")
        (field (name "AUTHOR") "CERN DEM JLC")
      )
      (libsource (lib "Capacitors") (part "Capacitor - non polarized"))
    )
    (comp (ref "C679")
      (value "100uF")
      (footprint "CAPC3225X270N")
      (description "Non-polarised capacitor")
      (fields
        (field (name "PART NUMBER") "CC1210_100UF_6.3V_20%_X5R")
        (field (name "VOLTAGE") "6.3V")
        (field (name "AUTHOR") "CERN DEM JLC")
      )
      (libsource (lib "Capacitors") (part "Capacitor - non polarized"))
    )
    (comp (ref "C680")
      (value "4.7uF")
      (footprint "CAPC1608X87N")
      (description "Non-polarised capacitor")
      (fields
        (field (name "PART NUMBER") "CC0603_4.7UF_6.3V_10%_X5R")
        (field (name "VOLTAGE") "6.3V")
        (field (name "AUTHOR") "CERN DEM JLC")
      )
      (libsource (lib "Capacitors") (part "Capacitor - non polarized"))
    )
    (comp (ref "C681")
      (value "4.7uF")
      (footprint "CAPC1608X87N")
      (description "Non-polarised capacitor")
      (fields
        (field (name "PART NUMBER") "CC0603_4.7UF_6.3V_10%_X5R")
        (field (name "VOLTAGE") "6.3V")
        (field (name "AUTHOR") "CERN DEM JLC")
      )
      (libsource (lib "Capacitors") (part "Capacitor - non polarized"))
    )
    (comp (ref "C682")
      (value "4.7uF")
      (footprint "CAPC1608X87N")
      (description "Non-polarised capacitor")
      (fields
        (field (name "PART NUMBER") "CC0603_4.7UF_6.3V_10%_X5R")
        (field (name "VOLTAGE") "6.3V")
        (field (name "AUTHOR") "CERN DEM JLC")
      )
      (libsource (lib "Capacitors") (part "Capacitor - non polarized"))
    )
    (comp (ref "C683")
      (value "470nF")
      (footprint "CAPC0603X33N")
      (description "Non-polarised capacitor")
      (fields
        (field (name "PART NUMBER") "CC0201_470NF_4V_20%_X5R")
        (field (name "VOLTAGE") "4V")
        (field (name "AUTHOR") "CERN DEM JLC")
      )
      (libsource (lib "Capacitors") (part "Capacitor - non polarized"))
    )
    (comp (ref "C684")
      (value "470nF")
      (footprint "CAPC0603X33N")
      (description "Non-polarised capacitor")
      (fields
        (field (name "PART NUMBER") "CC0201_470NF_4V_20%_X5R")
        (field (name "VOLTAGE") "4V")
        (field (name "AUTHOR") "CERN DEM JLC")
      )
      (libsource (lib "Capacitors") (part "Capacitor - non polarized"))
    )
    (comp (ref "C685")
      (value "470nF")
      (footprint "CAPC0603X33N")
      (description "Non-polarised capacitor")
      (fields
        (field (name "PART NUMBER") "CC0201_470NF_4V_20%_X5R")
        (field (name "VOLTAGE") "4V")
        (field (name "AUTHOR") "CERN DEM JLC")
      )
      (libsource (lib "Capacitors") (part "Capacitor - non polarized"))
    )
    (comp (ref "C686")
      (value "470nF")
      (footprint "CAPC0603X33N")
      (description "Non-polarised capacitor")
      (fields
        (field (name "PART NUMBER") "CC0201_470NF_4V_20%_X5R")
        (field (name "VOLTAGE") "4V")
        (field (name "AUTHOR") "CERN DEM JLC")
      )
      (libsource (lib "Capacitors") (part "Capacitor - non polarized"))
    )
    (comp (ref "C687")
      (value "470nF")
      (footprint "CAPC0603X33N")
      (description "Non-polarised capacitor")
      (fields
        (field (name "PART NUMBER") "CC0201_470NF_4V_20%_X5R")
        (field (name "VOLTAGE") "4V")
        (field (name "AUTHOR") "CERN DEM JLC")
      )
      (libsource (lib "Capacitors") (part "Capacitor - non polarized"))
    )
    (comp (ref "C688")
      (value "4.7uF")
      (footprint "CAPC1608X87N")
      (description "Non-polarised capacitor")
      (fields
        (field (name "PART NUMBER") "CC0603_4.7UF_6.3V_10%_X5R")
        (field (name "VOLTAGE") "6.3V")
        (field (name "AUTHOR") "CERN DEM JLC")
      )
      (libsource (lib "Capacitors") (part "Capacitor - non polarized"))
    )
    (comp (ref "C689")
      (value "4.7uF")
      (footprint "CAPC1608X87N")
      (description "Non-polarised capacitor")
      (fields
        (field (name "PART NUMBER") "CC0603_4.7UF_6.3V_10%_X5R")
        (field (name "VOLTAGE") "6.3V")
        (field (name "AUTHOR") "CERN DEM JLC")
      )
      (libsource (lib "Capacitors") (part "Capacitor - non polarized"))
    )
    (comp (ref "C690")
      (value "4.7uF")
      (footprint "CAPC1608X87N")
      (description "Non-polarised capacitor")
      (fields
        (field (name "PART NUMBER") "CC0603_4.7UF_6.3V_10%_X5R")
        (field (name "VOLTAGE") "6.3V")
        (field (name "AUTHOR") "CERN DEM JLC")
      )
      (libsource (lib "Capacitors") (part "Capacitor - non polarized"))
    )
    (comp (ref "C691")
      (value "470nF")
      (footprint "CAPC0603X33N")
      (description "Non-polarised capacitor")
      (fields
        (field (name "PART NUMBER") "CC0201_470NF_4V_20%_X5R")
        (field (name "VOLTAGE") "4V")
        (field (name "AUTHOR") "CERN DEM JLC")
      )
      (libsource (lib "Capacitors") (part "Capacitor - non polarized"))
    )
    (comp (ref "C692")
      (value "470nF")
      (footprint "CAPC0603X33N")
      (description "Non-polarised capacitor")
      (fields
        (field (name "PART NUMBER") "CC0201_470NF_4V_20%_X5R")
        (field (name "VOLTAGE") "4V")
        (field (name "AUTHOR") "CERN DEM JLC")
      )
      (libsource (lib "Capacitors") (part "Capacitor - non polarized"))
    )
    (comp (ref "C693")
      (value "470nF")
      (footprint "CAPC0603X33N")
      (description "Non-polarised capacitor")
      (fields
        (field (name "PART NUMBER") "CC0201_470NF_4V_20%_X5R")
        (field (name "VOLTAGE") "4V")
        (field (name "AUTHOR") "CERN DEM JLC")
      )
      (libsource (lib "Capacitors") (part "Capacitor - non polarized"))
    )
    (comp (ref "C694")
      (value "470nF")
      (footprint "CAPC0603X33N")
      (description "Non-polarised capacitor")
      (fields
        (field (name "PART NUMBER") "CC0201_470NF_4V_20%_X5R")
        (field (name "VOLTAGE") "4V")
        (field (name "AUTHOR") "CERN DEM JLC")
      )
      (libsource (lib "Capacitors") (part "Capacitor - non polarized"))
    )
    (comp (ref "C695")
      (value "470nF")
      (footprint "CAPC0603X33N")
      (description "Non-polarised capacitor")
      (fields
        (field (name "PART NUMBER") "CC0201_470NF_4V_20%_X5R")
        (field (name "VOLTAGE") "4V")
        (field (name "AUTHOR") "CERN DEM JLC")
      )
      (libsource (lib "Capacitors") (part "Capacitor - non polarized"))
    )
    (comp (ref "C696")
      (value "4.7uF")
      (footprint "CAPC1608X87N")
      (description "Non-polarised capacitor")
      (fields
        (field (name "PART NUMBER") "CC0603_4.7UF_6.3V_10%_X5R")
        (field (name "VOLTAGE") "6.3V")
        (field (name "AUTHOR") "CERN DEM JLC")
      )
      (libsource (lib "Capacitors") (part "Capacitor - non polarized"))
    )
    (comp (ref "C697")
      (value "4.7uF")
      (footprint "CAPC1608X87N")
      (description "Non-polarised capacitor")
      (fields
        (field (name "PART NUMBER") "CC0603_4.7UF_6.3V_10%_X5R")
        (field (name "VOLTAGE") "6.3V")
        (field (name "AUTHOR") "CERN DEM JLC")
      )
      (libsource (lib "Capacitors") (part "Capacitor - non polarized"))
    )
    (comp (ref "C698")
      (value "4.7uF")
      (footprint "CAPC1608X87N")
      (description "Non-polarised capacitor")
      (fields
        (field (name "PART NUMBER") "CC0603_4.7UF_6.3V_10%_X5R")
        (field (name "VOLTAGE") "6.3V")
        (field (name "AUTHOR") "CERN DEM JLC")
      )
      (libsource (lib "Capacitors") (part "Capacitor - non polarized"))
    )
    (comp (ref "C699")
      (value "470nF")
      (footprint "CAPC0603X33N")
      (description "Non-polarised capacitor")
      (fields
        (field (name "PART NUMBER") "CC0201_470NF_4V_20%_X5R")
        (field (name "VOLTAGE") "4V")
        (field (name "AUTHOR") "CERN DEM JLC")
      )
      (libsource (lib "Capacitors") (part "Capacitor - non polarized"))
    )
    (comp (ref "C700")
      (value "470nF")
      (footprint "CAPC0603X33N")
      (description "Non-polarised capacitor")
      (fields
        (field (name "PART NUMBER") "CC0201_470NF_4V_20%_X5R")
        (field (name "VOLTAGE") "4V")
        (field (name "AUTHOR") "CERN DEM JLC")
      )
      (libsource (lib "Capacitors") (part "Capacitor - non polarized"))
    )
    (comp (ref "C701")
      (value "470nF")
      (footprint "CAPC0603X33N")
      (description "Non-polarised capacitor")
      (fields
        (field (name "PART NUMBER") "CC0201_470NF_4V_20%_X5R")
        (field (name "VOLTAGE") "4V")
        (field (name "AUTHOR") "CERN DEM JLC")
      )
      (libsource (lib "Capacitors") (part "Capacitor - non polarized"))
    )
    (comp (ref "C702")
      (value "470nF")
      (footprint "CAPC0603X33N")
      (description "Non-polarised capacitor")
      (fields
        (field (name "PART NUMBER") "CC0201_470NF_4V_20%_X5R")
        (field (name "VOLTAGE") "4V")
        (field (name "AUTHOR") "CERN DEM JLC")
      )
      (libsource (lib "Capacitors") (part "Capacitor - non polarized"))
    )
    (comp (ref "C703")
      (value "470nF")
      (footprint "CAPC0603X33N")
      (description "Non-polarised capacitor")
      (fields
        (field (name "PART NUMBER") "CC0201_470NF_4V_20%_X5R")
        (field (name "VOLTAGE") "4V")
        (field (name "AUTHOR") "CERN DEM JLC")
      )
      (libsource (lib "Capacitors") (part "Capacitor - non polarized"))
    )
    (comp (ref "C704")
      (value "4.7uF")
      (footprint "CAPC1608X87N")
      (description "Non-polarised capacitor")
      (fields
        (field (name "PART NUMBER") "CC0603_4.7UF_6.3V_10%_X5R")
        (field (name "VOLTAGE") "6.3V")
        (field (name "AUTHOR") "CERN DEM JLC")
      )
      (libsource (lib "Capacitors") (part "Capacitor - non polarized"))
    )
    (comp (ref "C705")
      (value "4.7uF")
      (footprint "CAPC1608X87N")
      (description "Non-polarised capacitor")
      (fields
        (field (name "PART NUMBER") "CC0603_4.7UF_6.3V_10%_X5R")
        (field (name "VOLTAGE") "6.3V")
        (field (name "AUTHOR") "CERN DEM JLC")
      )
      (libsource (lib "Capacitors") (part "Capacitor - non polarized"))
    )
    (comp (ref "C706")
      (value "4.7uF")
      (footprint "CAPC1608X87N")
      (description "Non-polarised capacitor")
      (fields
        (field (name "PART NUMBER") "CC0603_4.7UF_6.3V_10%_X5R")
        (field (name "VOLTAGE") "6.3V")
        (field (name "AUTHOR") "CERN DEM JLC")
      )
      (libsource (lib "Capacitors") (part "Capacitor - non polarized"))
    )
    (comp (ref "C707")
      (value "470nF")
      (footprint "CAPC0603X33N")
      (description "Non-polarised capacitor")
      (fields
        (field (name "PART NUMBER") "CC0201_470NF_4V_20%_X5R")
        (field (name "VOLTAGE") "4V")
        (field (name "AUTHOR") "CERN DEM JLC")
      )
      (libsource (lib "Capacitors") (part "Capacitor - non polarized"))
    )
    (comp (ref "C708")
      (value "470nF")
      (footprint "CAPC0603X33N")
      (description "Non-polarised capacitor")
      (fields
        (field (name "PART NUMBER") "CC0201_470NF_4V_20%_X5R")
        (field (name "VOLTAGE") "4V")
        (field (name "AUTHOR") "CERN DEM JLC")
      )
      (libsource (lib "Capacitors") (part "Capacitor - non polarized"))
    )
    (comp (ref "C709")
      (value "470nF")
      (footprint "CAPC0603X33N")
      (description "Non-polarised capacitor")
      (fields
        (field (name "PART NUMBER") "CC0201_470NF_4V_20%_X5R")
        (field (name "VOLTAGE") "4V")
        (field (name "AUTHOR") "CERN DEM JLC")
      )
      (libsource (lib "Capacitors") (part "Capacitor - non polarized"))
    )
    (comp (ref "C710")
      (value "470nF")
      (footprint "CAPC0603X33N")
      (description "Non-polarised capacitor")
      (fields
        (field (name "PART NUMBER") "CC0201_470NF_4V_20%_X5R")
        (field (name "VOLTAGE") "4V")
        (field (name "AUTHOR") "CERN DEM JLC")
      )
      (libsource (lib "Capacitors") (part "Capacitor - non polarized"))
    )
    (comp (ref "C711")
      (value "470nF")
      (footprint "CAPC0603X33N")
      (description "Non-polarised capacitor")
      (fields
        (field (name "PART NUMBER") "CC0201_470NF_4V_20%_X5R")
        (field (name "VOLTAGE") "4V")
        (field (name "AUTHOR") "CERN DEM JLC")
      )
      (libsource (lib "Capacitors") (part "Capacitor - non polarized"))
    )
    (comp (ref "C712")
      (value "100uF")
      (footprint "CAPC3225X270N")
      (description "Non-polarised capacitor")
      (fields
        (field (name "PART NUMBER") "CC1210_100UF_6.3V_20%_X5R")
        (field (name "VOLTAGE") "6.3V")
        (field (name "AUTHOR") "CERN DEM JLC")
      )
      (libsource (lib "Capacitors") (part "Capacitor - non polarized"))
    )
    (comp (ref "C713")
      (value "100uF")
      (footprint "CAPC3225X270N")
      (description "Non-polarised capacitor")
      (fields
        (field (name "PART NUMBER") "CC1210_100UF_6.3V_20%_X5R")
        (field (name "VOLTAGE") "6.3V")
        (field (name "AUTHOR") "CERN DEM JLC")
      )
      (libsource (lib "Capacitors") (part "Capacitor - non polarized"))
    )
    (comp (ref "C714")
      (value "100uF")
      (footprint "CAPC3225X270N")
      (description "Non-polarised capacitor")
      (fields
        (field (name "PART NUMBER") "CC1210_100UF_6.3V_20%_X5R")
        (field (name "VOLTAGE") "6.3V")
        (field (name "AUTHOR") "CERN DEM JLC")
      )
      (libsource (lib "Capacitors") (part "Capacitor - non polarized"))
    )
    (comp (ref "C715")
      (value "100uF")
      (footprint "CAPC3225X270N")
      (description "Non-polarised capacitor")
      (fields
        (field (name "PART NUMBER") "CC1210_100UF_6.3V_20%_X5R")
        (field (name "VOLTAGE") "6.3V")
        (field (name "AUTHOR") "CERN DEM JLC")
      )
      (libsource (lib "Capacitors") (part "Capacitor - non polarized"))
    )
    (comp (ref "C716")
      (value "470nF")
      (footprint "CAPC0603X33N")
      (description "Non-polarised capacitor")
      (fields
        (field (name "PART NUMBER") "CC0201_470NF_4V_20%_X5R")
        (field (name "VOLTAGE") "4V")
        (field (name "AUTHOR") "CERN DEM JLC")
      )
      (libsource (lib "Capacitors") (part "Capacitor - non polarized"))
    )
    (comp (ref "C717")
      (value "470nF")
      (footprint "CAPC0603X33N")
      (description "Non-polarised capacitor")
      (fields
        (field (name "PART NUMBER") "CC0201_470NF_4V_20%_X5R")
        (field (name "VOLTAGE") "4V")
        (field (name "AUTHOR") "CERN DEM JLC")
      )
      (libsource (lib "Capacitors") (part "Capacitor - non polarized"))
    )
    (comp (ref "C718")
      (value "470nF")
      (footprint "CAPC0603X33N")
      (description "Non-polarised capacitor")
      (fields
        (field (name "PART NUMBER") "CC0201_470NF_4V_20%_X5R")
        (field (name "VOLTAGE") "4V")
        (field (name "AUTHOR") "CERN DEM JLC")
      )
      (libsource (lib "Capacitors") (part "Capacitor - non polarized"))
    )
    (comp (ref "C719")
      (value "470nF")
      (footprint "CAPC0603X33N")
      (description "Non-polarised capacitor")
      (fields
        (field (name "PART NUMBER") "CC0201_470NF_4V_20%_X5R")
        (field (name "VOLTAGE") "4V")
        (field (name "AUTHOR") "CERN DEM JLC")
      )
      (libsource (lib "Capacitors") (part "Capacitor - non polarized"))
    )
    (comp (ref "C720")
      (value "470nF")
      (footprint "CAPC0603X33N")
      (description "Non-polarised capacitor")
      (fields
        (field (name "PART NUMBER") "CC0201_470NF_4V_20%_X5R")
        (field (name "VOLTAGE") "4V")
        (field (name "AUTHOR") "CERN DEM JLC")
      )
      (libsource (lib "Capacitors") (part "Capacitor - non polarized"))
    )
    (comp (ref "C721")
      (value "470nF")
      (footprint "CAPC0603X33N")
      (description "Non-polarised capacitor")
      (fields
        (field (name "PART NUMBER") "CC0201_470NF_4V_20%_X5R")
        (field (name "VOLTAGE") "4V")
        (field (name "AUTHOR") "CERN DEM JLC")
      )
      (libsource (lib "Capacitors") (part "Capacitor - non polarized"))
    )
    (comp (ref "C722")
      (value "22nF")
      (footprint "CAPC0603X33N")
      (description "Non-polarised capacitor")
      (fields
        (field (name "PART NUMBER") "CC0201_22NF_6.3V_10%_X5R")
        (field (name "VOLTAGE") "6.3V")
        (field (name "AUTHOR") "CERN DEM JLC")
      )
      (libsource (lib "Capacitors") (part "Capacitor - non polarized"))
    )
    (comp (ref "C723")
      (value "22nF")
      (footprint "CAPC0603X33N")
      (description "Non-polarised capacitor")
      (fields
        (field (name "PART NUMBER") "CC0201_22NF_6.3V_10%_X5R")
        (field (name "VOLTAGE") "6.3V")
        (field (name "AUTHOR") "CERN DEM JLC")
      )
      (libsource (lib "Capacitors") (part "Capacitor - non polarized"))
    )
    (comp (ref "C724")
      (value "22nF")
      (footprint "CAPC0603X33N")
      (description "Non-polarised capacitor")
      (fields
        (field (name "PART NUMBER") "CC0201_22NF_6.3V_10%_X5R")
        (field (name "VOLTAGE") "6.3V")
        (field (name "AUTHOR") "CERN DEM JLC")
      )
      (libsource (lib "Capacitors") (part "Capacitor - non polarized"))
    )
    (comp (ref "C725")
      (value "22nF")
      (footprint "CAPC0603X33N")
      (description "Non-polarised capacitor")
      (fields
        (field (name "PART NUMBER") "CC0201_22NF_6.3V_10%_X5R")
        (field (name "VOLTAGE") "6.3V")
        (field (name "AUTHOR") "CERN DEM JLC")
      )
      (libsource (lib "Capacitors") (part "Capacitor - non polarized"))
    )
    (comp (ref "C726")
      (value "100nF")
      (footprint "CAPC0603X33N")
      (description "Non-polarised capacitor")
      (fields
        (field (name "PART NUMBER") "CC0201_100NF_6.3V_10%_X5R")
        (field (name "VOLTAGE") "6.3V")
        (field (name "AUTHOR") "CERN DEM JLC")
      )
      (libsource (lib "Capacitors") (part "Capacitor - non polarized"))
    )
    (comp (ref "C727")
      (value "100nF")
      (footprint "CAPC0603X33N")
      (description "Non-polarised capacitor")
      (fields
        (field (name "PART NUMBER") "CC0201_100NF_6.3V_10%_X5R")
        (field (name "VOLTAGE") "6.3V")
        (field (name "AUTHOR") "CERN DEM JLC")
      )
      (libsource (lib "Capacitors") (part "Capacitor - non polarized"))
    )
    (comp (ref "C728")
      (value "100nF")
      (footprint "CAPC0603X33N")
      (description "Non-polarised capacitor")
      (fields
        (field (name "PART NUMBER") "CC0201_100NF_6.3V_10%_X5R")
        (field (name "VOLTAGE") "6.3V")
        (field (name "AUTHOR") "CERN DEM JLC")
      )
      (libsource (lib "Capacitors") (part "Capacitor - non polarized"))
    )
    (comp (ref "C729")
      (value "100nF")
      (footprint "CAPC0603X33N")
      (description "Non-polarised capacitor")
      (fields
        (field (name "PART NUMBER") "CC0201_100NF_6.3V_10%_X5R")
        (field (name "VOLTAGE") "6.3V")
        (field (name "AUTHOR") "CERN DEM JLC")
      )
      (libsource (lib "Capacitors") (part "Capacitor - non polarized"))
    )
    (comp (ref "C730")
      (value "22nF")
      (footprint "CAPC0603X33N")
      (description "Non-polarised capacitor")
      (fields
        (field (name "PART NUMBER") "CC0201_22NF_6.3V_10%_X5R")
        (field (name "VOLTAGE") "6.3V")
        (field (name "AUTHOR") "CERN DEM JLC")
      )
      (libsource (lib "Capacitors") (part "Capacitor - non polarized"))
    )
    (comp (ref "C731")
      (value "22nF")
      (footprint "CAPC0603X33N")
      (description "Non-polarised capacitor")
      (fields
        (field (name "PART NUMBER") "CC0201_22NF_6.3V_10%_X5R")
        (field (name "VOLTAGE") "6.3V")
        (field (name "AUTHOR") "CERN DEM JLC")
      )
      (libsource (lib "Capacitors") (part "Capacitor - non polarized"))
    )
    (comp (ref "C732")
      (value "22nF")
      (footprint "CAPC0603X33N")
      (description "Non-polarised capacitor")
      (fields
        (field (name "PART NUMBER") "CC0201_22NF_6.3V_10%_X5R")
        (field (name "VOLTAGE") "6.3V")
        (field (name "AUTHOR") "CERN DEM JLC")
      )
      (libsource (lib "Capacitors") (part "Capacitor - non polarized"))
    )
    (comp (ref "C733")
      (value "22nF")
      (footprint "CAPC0603X33N")
      (description "Non-polarised capacitor")
      (fields
        (field (name "PART NUMBER") "CC0201_22NF_6.3V_10%_X5R")
        (field (name "VOLTAGE") "6.3V")
        (field (name "AUTHOR") "CERN DEM JLC")
      )
      (libsource (lib "Capacitors") (part "Capacitor - non polarized"))
    )
    (comp (ref "C734")
      (value "100nF")
      (footprint "CAPC0603X33N")
      (description "Non-polarised capacitor")
      (fields
        (field (name "PART NUMBER") "CC0201_100NF_6.3V_10%_X5R")
        (field (name "VOLTAGE") "6.3V")
        (field (name "AUTHOR") "CERN DEM JLC")
      )
      (libsource (lib "Capacitors") (part "Capacitor - non polarized"))
    )
    (comp (ref "C735")
      (value "100nF")
      (footprint "CAPC0603X33N")
      (description "Non-polarised capacitor")
      (fields
        (field (name "PART NUMBER") "CC0201_100NF_6.3V_10%_X5R")
        (field (name "VOLTAGE") "6.3V")
        (field (name "AUTHOR") "CERN DEM JLC")
      )
      (libsource (lib "Capacitors") (part "Capacitor - non polarized"))
    )
    (comp (ref "C736")
      (value "100nF")
      (footprint "CAPC0603X33N")
      (description "Non-polarised capacitor")
      (fields
        (field (name "PART NUMBER") "CC0201_100NF_6.3V_10%_X5R")
        (field (name "VOLTAGE") "6.3V")
        (field (name "AUTHOR") "CERN DEM JLC")
      )
      (libsource (lib "Capacitors") (part "Capacitor - non polarized"))
    )
    (comp (ref "C737")
      (value "100nF")
      (footprint "CAPC0603X33N")
      (description "Non-polarised capacitor")
      (fields
        (field (name "PART NUMBER") "CC0201_100NF_6.3V_10%_X5R")
        (field (name "VOLTAGE") "6.3V")
        (field (name "AUTHOR") "CERN DEM JLC")
      )
      (libsource (lib "Capacitors") (part "Capacitor - non polarized"))
    )
    (comp (ref "C738")
      (value "220nF")
      (footprint "CAPC0603X33N")
      (description "Non-polarised capacitor")
      (fields
        (field (name "PART NUMBER") "CC0201_220NF_6.3V_20%_X5R")
        (field (name "VOLTAGE") "6.3V")
        (field (name "AUTHOR") "CERN DEM JLC")
      )
      (libsource (lib "Capacitors") (part "Capacitor - non polarized"))
    )
    (comp (ref "C739")
      (value "220nF")
      (footprint "CAPC0603X33N")
      (description "Non-polarised capacitor")
      (fields
        (field (name "PART NUMBER") "CC0201_220NF_6.3V_20%_X5R")
        (field (name "VOLTAGE") "6.3V")
        (field (name "AUTHOR") "CERN DEM JLC")
      )
      (libsource (lib "Capacitors") (part "Capacitor - non polarized"))
    )
    (comp (ref "C740")
      (value "220nF")
      (footprint "CAPC0603X33N")
      (description "Non-polarised capacitor")
      (fields
        (field (name "PART NUMBER") "CC0201_220NF_6.3V_20%_X5R")
        (field (name "VOLTAGE") "6.3V")
        (field (name "AUTHOR") "CERN DEM JLC")
      )
      (libsource (lib "Capacitors") (part "Capacitor - non polarized"))
    )
    (comp (ref "C741")
      (value "220nF")
      (footprint "CAPC0603X33N")
      (description "Non-polarised capacitor")
      (fields
        (field (name "PART NUMBER") "CC0201_220NF_6.3V_20%_X5R")
        (field (name "VOLTAGE") "6.3V")
        (field (name "AUTHOR") "CERN DEM JLC")
      )
      (libsource (lib "Capacitors") (part "Capacitor - non polarized"))
    )
    (comp (ref "C742")
      (value "220nF")
      (footprint "CAPC0603X33N")
      (description "Non-polarised capacitor")
      (fields
        (field (name "PART NUMBER") "CC0201_220NF_6.3V_20%_X5R")
        (field (name "VOLTAGE") "6.3V")
        (field (name "AUTHOR") "CERN DEM JLC")
      )
      (libsource (lib "Capacitors") (part "Capacitor - non polarized"))
    )
    (comp (ref "C743")
      (value "220nF")
      (footprint "CAPC0603X33N")
      (description "Non-polarised capacitor")
      (fields
        (field (name "PART NUMBER") "CC0201_220NF_6.3V_20%_X5R")
        (field (name "VOLTAGE") "6.3V")
        (field (name "AUTHOR") "CERN DEM JLC")
      )
      (libsource (lib "Capacitors") (part "Capacitor - non polarized"))
    )
    (comp (ref "C744")
      (value "220nF")
      (footprint "CAPC0603X33N")
      (description "Non-polarised capacitor")
      (fields
        (field (name "PART NUMBER") "CC0201_220NF_6.3V_20%_X5R")
        (field (name "VOLTAGE") "6.3V")
        (field (name "AUTHOR") "CERN DEM JLC")
      )
      (libsource (lib "Capacitors") (part "Capacitor - non polarized"))
    )
    (comp (ref "C745")
      (value "220nF")
      (footprint "CAPC0603X33N")
      (description "Non-polarised capacitor")
      (fields
        (field (name "PART NUMBER") "CC0201_220NF_6.3V_20%_X5R")
        (field (name "VOLTAGE") "6.3V")
        (field (name "AUTHOR") "CERN DEM JLC")
      )
      (libsource (lib "Capacitors") (part "Capacitor - non polarized"))
    )
    (comp (ref "C746")
      (value "220nF")
      (footprint "CAPC0603X33N")
      (description "Non-polarised capacitor")
      (fields
        (field (name "PART NUMBER") "CC0201_220NF_6.3V_20%_X5R")
        (field (name "VOLTAGE") "6.3V")
        (field (name "AUTHOR") "CERN DEM JLC")
      )
      (libsource (lib "Capacitors") (part "Capacitor - non polarized"))
    )
    (comp (ref "C747")
      (value "220nF")
      (footprint "CAPC0603X33N")
      (description "Non-polarised capacitor")
      (fields
        (field (name "PART NUMBER") "CC0201_220NF_6.3V_20%_X5R")
        (field (name "VOLTAGE") "6.3V")
        (field (name "AUTHOR") "CERN DEM JLC")
      )
      (libsource (lib "Capacitors") (part "Capacitor - non polarized"))
    )
    (comp (ref "C748")
      (value "220nF")
      (footprint "CAPC0603X33N")
      (description "Non-polarised capacitor")
      (fields
        (field (name "PART NUMBER") "CC0201_220NF_6.3V_20%_X5R")
        (field (name "VOLTAGE") "6.3V")
        (field (name "AUTHOR") "CERN DEM JLC")
      )
      (libsource (lib "Capacitors") (part "Capacitor - non polarized"))
    )
    (comp (ref "FB5")
      (value "60R@100MHz")
      (footprint "INDC4516X180N")
      (fields
        (field (name "PART NUMBER") "IND1806_MURATA_BLM41PG600SN1L")
        (field (name "POWER") "6A")
        (field (name "MANUFACTURER") "MURATA")
        (field (name "AUTHOR") "CERN DEM JLC")
      )
      (libsource (lib "Inductors & Transformers") (part "Ferrite Bead"))
    )
    (comp (ref "FB6")
      (value "60R@100MHz")
      (footprint "INDC4516X180N")
      (fields
        (field (name "PART NUMBER") "IND1806_MURATA_BLM41PG600SN1L")
        (field (name "POWER") "6A")
        (field (name "MANUFACTURER") "MURATA")
        (field (name "AUTHOR") "CERN DEM JLC")
      )
      (libsource (lib "Inductors & Transformers") (part "Ferrite Bead"))
    )
    (comp (ref "FB7")
      (value "60R@100MHz")
      (footprint "INDC4516X180N")
      (fields
        (field (name "PART NUMBER") "IND1806_MURATA_BLM41PG600SN1L")
        (field (name "POWER") "6A")
        (field (name "MANUFACTURER") "MURATA")
        (field (name "AUTHOR") "CERN DEM JLC")
      )
      (libsource (lib "Inductors & Transformers") (part "Ferrite Bead"))
    )
    (comp (ref "FB8")
      (value "60R@100MHz")
      (footprint "INDC4516X180N")
      (fields
        (field (name "PART NUMBER") "IND1806_MURATA_BLM41PG600SN1L")
        (field (name "POWER") "6A")
        (field (name "MANUFACTURER") "MURATA")
        (field (name "AUTHOR") "CERN DEM JLC")
      )
      (libsource (lib "Inductors & Transformers") (part "Ferrite Bead"))
    )
    (comp (ref "IC2")
      (value "XC7A200T-3FFG1156C")
      (footprint "BGA1156C100P34X34_3500X3500X335")
      (description "Artix-6 FPGA, 16 GTPs, 600 User I/Os, 1156-Pin BGA, Speed Grade 2, Commercial Grade, Pb-Free")
      (fields
        (field (name "MANUFACTURER") "XILINX")
        (field (name "MANUFACTURER PART NUMBER") "XC7A350T-2FFG1156C")
        (field (name "AUTHOR") "CERN DEM JLC")
      )
      (libsource (lib "AMC_FMC_Carrier") (part "XC7A200T-3FFG1156C"))
    )
    (comp (ref "L10")
      (value "1uH")
      (footprint "IND_PANASONIC_ELLVGG")
      (description "Inductor With Core")
      (fields
        (field (name "PART NUMBER") "IND_1UH_30%_PANASONIC_ELLVGG1R0N")
        (field (name "POWER") "1.8A")
        (field (name "AUTHOR") "CERN DEM JLC")
      )
      (libsource (lib "Inductors & Transformers") (part "Inductor With Magnetic core"))
    )
    (comp (ref "L12")
      (value "1uH")
      (footprint "IND_PANASONIC_ELLVGG")
      (description "Inductor With Core")
      (fields
        (field (name "PART NUMBER") "IND_1UH_30%_PANASONIC_ELLVGG1R0N")
        (field (name "POWER") "1.8A")
        (field (name "AUTHOR") "CERN DEM JLC")
      )
      (libsource (lib "Inductors & Transformers") (part "Inductor With Magnetic core"))
    )
  )
  (nets
    (net (code "1") (name "GND") (class "Default")
      (node (ref "BH1") (pin "2") (pinfunction "MINUS_2") (pintype "power_in"))
      (node (ref "C106") (pin "1") (pinfunction "1_1") (pintype "passive"))
      (node (ref "C107") (pin "1") (pinfunction "1_1") (pintype "passive"))
      (node (ref "C226") (pin "2") (pinfunction "2_2") (pintype "passive"))
      (node (ref "C229") (pin "1") (pinfunction "1_1") (pintype "passive"))
      (node (ref "C230") (pin "2") (pinfunction "2_2") (pintype "passive"))
      (node (ref "C231") (pin "2") (pinfunction "2_2") (pintype "passive"))
      (node (ref "C232") (pin "1") (pinfunction "1_1") (pintype "passive"))
      (node (ref "C233") (pin "1") (pinfunction "1_1") (pintype "passive"))
      (node (ref "C234") (pin "1") (pinfunction "1_1") (pintype "passive"))
      (node (ref "C235") (pin "1") (pinfunction "1_1") (pintype "passive"))
      (node (ref "C236") (pin "1") (pinfunction "1_1") (pintype "passive"))
      (node (ref "C237") (pin "1") (pinfunction "1_1") (pintype "passive"))
      (node (ref "C238") (pin "1") (pinfunction "1_1") (pintype "passive"))
      (node (ref "C239") (pin "1") (pinfunction "1_1") (pintype "passive"))
      (node (ref "C240") (pin "1") (pinfunction "1_1") (pintype "passive"))
      (node (ref "C241") (pin "1") (pinfunction "1_1") (pintype "passive"))
      (node (ref "C242") (pin "1") (pinfunction "1_1") (pintype "passive"))
      (node (ref "C243") (pin "1") (pinfunction "1_1") (pintype "passive"))
      (node (ref "C244") (pin "1") (pinfunction "1_1") (pintype "passive"))
      (node (ref "C245") (pin "1") (pinfunction "1_1") (pintype "passive"))
      (node (ref "C246") (pin "1") (pinfunction "1_1") (pintype "passive"))
      (node (ref "C247") (pin "1") (pinfunction "1_1") (pintype "passive"))
      (node (ref "C248") (pin "1") (pinfunction "1_1") (pintype "passive"))
      (node (ref "C249") (pin "1") (pinfunction "1_1") (pintype "passive"))
      (node (ref "C250") (pin "1") (pinfunction "1_1") (pintype "passive"))
      (node (ref "C251") (pin "1") (pinfunction "1_1") (pintype "passive"))
      (node (ref "C252") (pin "1") (pinfunction "1_1") (pintype "passive"))
      (node (ref "C253") (pin "1") (pinfunction "1_1") (pintype "passive"))
      (node (ref "C254") (pin "1") (pinfunction "1_1") (pintype "passive"))
      (node (ref "C255") (pin "1") (pinfunction "1_1") (pintype "passive"))
      (node (ref "C256") (pin "1") (pinfunction "1_1") (pintype "passive"))
      (node (ref "C257") (pin "1") (pinfunction "1_1") (pintype "passive"))
      (node (ref "C258") (pin "1") (pinfunction "1_1") (pintype "passive"))
      (node (ref "C259") (pin "1") (pinfunction "1_1") (pintype "passive"))
      (node (ref "C260") (pin "1") (pinfunction "1_1") (pintype "passive"))
      (node (ref "C261") (pin "1") (pinfunction "1_1") (pintype "passive"))
      (node (ref "C262") (pin "1") (pinfunction "1_1") (pintype "passive"))
      (node (ref "C263") (pin "1") (pinfunction "1_1") (pintype "passive"))
      (node (ref "C264") (pin "1") (pinfunction "1_1") (pintype "passive"))
      (node (ref "C265") (pin "1") (pinfunction "1_1") (pintype "passive"))
      (node (ref "C266") (pin "1") (pinfunction "1_1") (pintype "passive"))
      (node (ref "C267") (pin "1") (pinfunction "1_1") (pintype "passive"))
      (node (ref "C268") (pin "1") (pinfunction "1_1") (pintype "passive"))
      (node (ref "C269") (pin "1") (pinfunction "1_1") (pintype "passive"))
      (node (ref "C270") (pin "1") (pinfunction "1_1") (pintype "passive"))
      (node (ref "C271") (pin "1") (pinfunction "1_1") (pintype "passive"))
      (node (ref "C272") (pin "1") (pinfunction "1_1") (pintype "passive"))
      (node (ref "C275") (pin "1") (pinfunction "1_1") (pintype "passive"))
      (node (ref "C276") (pin "1") (pinfunction "1_1") (pintype "passive"))
      (node (ref "C277") (pin "1") (pinfunction "1_1") (pintype "passive"))
      (node (ref "C278") (pin "1") (pinfunction "1_1") (pintype "passive"))
      (node (ref "C279") (pin "1") (pinfunction "1_1") (pintype "passive"))
      (node (ref "C280") (pin "1") (pinfunction "1_1") (pintype "passive"))
      (node (ref "C283") (pin "1") (pinfunction "1_1") (pintype "passive"))
      (node (ref "C284") (pin "1") (pinfunction "1_1") (pintype "passive"))
      (node (ref "C285") (pin "1") (pinfunction "1_1") (pintype "passive"))
      (node (ref "C286") (pin "1") (pinfunction "1_1") (pintype "passive"))
      (node (ref "C287") (pin "1") (pinfunction "1_1") (pintype "passive"))
      (node (ref "C288") (pin "1") (pinfunction "1_1") (pintype "passive"))
      (node (ref "C291") (pin "1") (pinfunction "1_1") (pintype "passive"))
      (node (ref "C292") (pin "1") (pinfunction "1_1") (pintype "passive"))
      (node (ref "C293") (pin "1") (pinfunction "1_1") (pintype "passive"))
      (node (ref "C294") (pin "1") (pinfunction "1_1") (pintype "passive"))
      (node (ref "C295") (pin "1") (pinfunction "1_1") (pintype "passive"))
      (node (ref "C296") (pin "1") (pinfunction "1_1") (pintype "passive"))
      (node (ref "C446") (pin "1") (pinfunction "1_1") (pintype "passive"))
      (node (ref "C447") (pin "2") (pinfunction "2_2") (pintype "passive"))
      (node (ref "C448") (pin "1") (pinfunction "1_1") (pintype "passive"))
      (node (ref "C449") (pin "1") (pinfunction "1_1") (pintype "passive"))
      (node (ref "C450") (pin "1") (pinfunction "1_1") (pintype "passive"))
      (node (ref "C451") (pin "1") (pinfunction "1_1") (pintype "passive"))
      (node (ref "C465") (pin "1") (pinfunction "1_1") (pintype "passive"))
      (node (ref "C478") (pin "1") (pinfunction "1_1") (pintype "passive"))
      (node (ref "C502") (pin "1") (pinfunction "1_1") (pintype "passive"))
      (node (ref "C504") (pin "1") (pinfunction "1_1") (pintype "passive"))
      (node (ref "C549") (pin "1") (pinfunction "1_1") (pintype "passive"))
      (node (ref "C550") (pin "1") (pinfunction "1_1") (pintype "passive"))
      (node (ref "C551") (pin "1") (pinfunction "1_1") (pintype "passive"))
      (node (ref "C552") (pin "1") (pinfunction "1_1") (pintype "passive"))
      (node (ref "C553") (pin "1") (pinfunction "1_1") (pintype "passive"))
      (node (ref "C554") (pin "1") (pinfunction "1_1") (pintype "passive"))
      (node (ref "C555") (pin "1") (pinfunction "1_1") (pintype "passive"))
      (node (ref "C556") (pin "1") (pinfunction "1_1") (pintype "passive"))
      (node (ref "C557") (pin "1") (pinfunction "1_1") (pintype "passive"))
      (node (ref "C558") (pin "1") (pinfunction "1_1") (pintype "passive"))
      (node (ref "C559") (pin "1") (pinfunction "1_1") (pintype "passive"))
      (node (ref "C560") (pin "1") (pinfunction "1_1") (pintype "passive"))
      (node (ref "C561") (pin "1") (pinfunction "1_1") (pintype "passive"))
      (node (ref "C562") (pin "1") (pinfunction "1_1") (pintype "passive"))
      (node (ref "C563") (pin "1") (pinfunction "1_1") (pintype "passive"))
      (node (ref "C564") (pin "1") (pinfunction "1_1") (pintype "passive"))
      (node (ref "C565") (pin "1") (pinfunction "1_1") (pintype "passive"))
      (node (ref "C566") (pin "1") (pinfunction "1_1") (pintype "passive"))
      (node (ref "C576") (pin "1") (pinfunction "1_1") (pintype "passive"))
      (node (ref "C577") (pin "1") (pinfunction "1_1") (pintype "passive"))
      (node (ref "C578") (pin "1") (pinfunction "1_1") (pintype "passive"))
      (node (ref "C579") (pin "1") (pinfunction "1_1") (pintype "passive"))
      (node (ref "C580") (pin "1") (pinfunction "1_1") (pintype "passive"))
      (node (ref "C581") (pin "1") (pinfunction "1_1") (pintype "passive"))
      (node (ref "C582") (pin "1") (pinfunction "1_1") (pintype "passive"))
      (node (ref "C583") (pin "1") (pinfunction "1_1") (pintype "passive"))
      (node (ref "C585") (pin "1") (pinfunction "1_1") (pintype "passive"))
      (node (ref "C586") (pin "1") (pinfunction "1_1") (pintype "passive"))
      (node (ref "C587") (pin "2") (pinfunction "2_2") (pintype "passive"))
      (node (ref "C588") (pin "1") (pinfunction "1_1") (pintype "passive"))
      (node (ref "C589") (pin "1") (pinfunction "1_1") (pintype "passive"))
      (node (ref "C591") (pin "1") (pinfunction "1_1") (pintype "passive"))
      (node (ref "C592") (pin "2") (pinfunction "2_2") (pintype "passive"))
      (node (ref "C593") (pin "2") (pinfunction "2_2") (pintype "passive"))
      (node (ref "C594") (pin "1") (pinfunction "1_1") (pintype "passive"))
      (node (ref "C596") (pin "1") (pinfunction "1_1") (pintype "passive"))
      (node (ref "C597") (pin "1") (pinfunction "1_1") (pintype "passive"))
      (node (ref "C598") (pin "1") (pinfunction "1_1") (pintype "passive"))
      (node (ref "C599") (pin "1") (pinfunction "1_1") (pintype "passive"))
      (node (ref "C600") (pin "1") (pinfunction "1_1") (pintype "passive"))
      (node (ref "C601") (pin "1") (pinfunction "1_1") (pintype "passive"))
      (node (ref "C602") (pin "2") (pinfunction "2_2") (pintype "passive"))
      (node (ref "C603") (pin "1") (pinfunction "1_1") (pintype "passive"))
      (node (ref "C604") (pin "1") (pinfunction "1_1") (pintype "passive"))
      (node (ref "C605") (pin "1") (pinfunction "1_1") (pintype "passive"))
      (node (ref "C606") (pin "1") (pinfunction "1_1") (pintype "passive"))
      (node (ref "C607") (pin "1") (pinfunction "1_1") (pintype "passive"))
      (node (ref "C608") (pin "1") (pinfunction "1_1") (pintype "passive"))
      (node (ref "C609") (pin "1") (pinfunction "1_1") (pintype "passive"))
      (node (ref "C610") (pin "1") (pinfunction "1_1") (pintype "passive"))
      (node (ref "C611") (pin "1") (pinfunction "1_1") (pintype "passive"))
      (node (ref "C612") (pin "2") (pinfunction "2_2") (pintype "passive"))
      (node (ref "C614") (pin "1") (pinfunction "1_1") (pintype "passive"))
      (node (ref "C615") (pin "1") (pinfunction "1_1") (pintype "passive"))
      (node (ref "C636") (pin "1") (pinfunction "1_1") (pintype "passive"))
      (node (ref "C637") (pin "1") (pinfunction "1_1") (pintype "passive"))
      (node (ref "C638") (pin "2") (pinfunction "2_2") (pintype "passive"))
      (node (ref "C639") (pin "1") (pinfunction "1_1") (pintype "passive"))
      (node (ref "C640") (pin "1") (pinfunction "1_1") (pintype "passive"))
      (node (ref "C641") (pin "1") (pinfunction "1_1") (pintype "passive"))
      (node (ref "C642") (pin "1") (pinfunction "1_1") (pintype "passive"))
      (node (ref "C643") (pin "1") (pinfunction "1_1") (pintype "passive"))
      (node (ref "C644") (pin "1") (pinfunction "1_1") (pintype "passive"))
      (node (ref "C645") (pin "1") (pinfunction "1_1") (pintype "passive"))
      (node (ref "C646") (pin "1") (pinfunction "1_1") (pintype "passive"))
      (node (ref "C647") (pin "1") (pinfunction "1_1") (pintype "passive"))
      (node (ref "C648") (pin "1") (pinfunction "1_1") (pintype "passive"))
      (node (ref "C649") (pin "1") (pinfunction "1_1") (pintype "passive"))
      (node (ref "C650") (pin "1") (pinfunction "1_1") (pintype "passive"))
      (node (ref "C651") (pin "1") (pinfunction "1_1") (pintype "passive"))
      (node (ref "C652") (pin "1") (pinfunction "1_1") (pintype "passive"))
      (node (ref "C653") (pin "1") (pinfunction "1_1") (pintype "passive"))
      (node (ref "C654") (pin "1") (pinfunction "1_1") (pintype "passive"))
      (node (ref "C655") (pin "1") (pinfunction "1_1") (pintype "passive"))
      (node (ref "C656") (pin "1") (pinfunction "1_1") (pintype "passive"))
      (node (ref "C657") (pin "1") (pinfunction "1_1") (pintype "passive"))
      (node (ref "C658") (pin "1") (pinfunction "1_1") (pintype "passive"))
      (node (ref "C659") (pin "1") (pinfunction "1_1") (pintype "passive"))
      (node (ref "C660") (pin "1") (pinfunction "1_1") (pintype "passive"))
      (node (ref "C661") (pin "1") (pinfunction "1_1") (pintype "passive"))
      (node (ref "C662") (pin "1") (pinfunction "1_1") (pintype "passive"))
      (node (ref "C663") (pin "1") (pinfunction "1_1") (pintype "passive"))
      (node (ref "C664") (pin "1") (pinfunction "1_1") (pintype "passive"))
      (node (ref "C665") (pin "1") (pinfunction "1_1") (pintype "passive"))
      (node (ref "C666") (pin "1") (pinfunction "1_1") (pintype "passive"))
      (node (ref "C667") (pin "1") (pinfunction "1_1") (pintype "passive"))
      (node (ref "C668") (pin "1") (pinfunction "1_1") (pintype "passive"))
      (node (ref "C669") (pin "1") (pinfunction "1_1") (pintype "passive"))
      (node (ref "C670") (pin "1") (pinfunction "1_1") (pintype "passive"))
      (node (ref "C671") (pin "1") (pinfunction "1_1") (pintype "passive"))
      (node (ref "C672") (pin "1") (pinfunction "1_1") (pintype "passive"))
      (node (ref "C673") (pin "1") (pinfunction "1_1") (pintype "passive"))
      (node (ref "C674") (pin "1") (pinfunction "1_1") (pintype "passive"))
      (node (ref "C675") (pin "1") (pinfunction "1_1") (pintype "passive"))
      (node (ref "C676") (pin "2") (pinfunction "2_2") (pintype "passive"))
      (node (ref "C677") (pin "2") (pinfunction "2_2") (pintype "passive"))
      (node (ref "C678") (pin "2") (pinfunction "2_2") (pintype "passive"))
      (node (ref "C679") (pin "2") (pinfunction "2_2") (pintype "passive"))
      (node (ref "C680") (pin "1") (pinfunction "1_1") (pintype "passive"))
      (node (ref "C681") (pin "1") (pinfunction "1_1") (pintype "passive"))
      (node (ref "C682") (pin "1") (pinfunction "1_1") (pintype "passive"))
      (node (ref "C683") (pin "1") (pinfunction "1_1") (pintype "passive"))
      (node (ref "C684") (pin "1") (pinfunction "1_1") (pintype "passive"))
      (node (ref "C685") (pin "1") (pinfunction "1_1") (pintype "passive"))
      (node (ref "C686") (pin "1") (pinfunction "1_1") (pintype "passive"))
      (node (ref "C687") (pin "1") (pinfunction "1_1") (pintype "passive"))
      (node (ref "C688") (pin "1") (pinfunction "1_1") (pintype "passive"))
      (node (ref "C689") (pin "1") (pinfunction "1_1") (pintype "passive"))
      (node (ref "C690") (pin "1") (pinfunction "1_1") (pintype "passive"))
      (node (ref "C691") (pin "1") (pinfunction "1_1") (pintype "passive"))
      (node (ref "C692") (pin "1") (pinfunction "1_1") (pintype "passive"))
      (node (ref "C693") (pin "1") (pinfunction "1_1") (pintype "passive"))
      (node (ref "C694") (pin "1") (pinfunction "1_1") (pintype "passive"))
      (node (ref "C695") (pin "1") (pinfunction "1_1") (pintype "passive"))
      (node (ref "C696") (pin "1") (pinfunction "1_1") (pintype "passive"))
      (node (ref "C697") (pin "1") (pinfunction "1_1") (pintype "passive"))
      (node (ref "C698") (pin "1") (pinfunction "1_1") (pintype "passive"))
      (node (ref "C699") (pin "1") (pinfunction "1_1") (pintype "passive"))
      (node (ref "C700") (pin "1") (pinfunction "1_1") (pintype "passive"))
      (node (ref "C701") (pin "1") (pinfunction "1_1") (pintype "passive"))
      (node (ref "C702") (pin "1") (pinfunction "1_1") (pintype "passive"))
      (node (ref "C703") (pin "1") (pinfunction "1_1") (pintype "passive"))
      (node (ref "C704") (pin "1") (pinfunction "1_1") (pintype "passive"))
      (node (ref "C705") (pin "1") (pinfunction "1_1") (pintype "passive"))
      (node (ref "C706") (pin "1") (pinfunction "1_1") (pintype "passive"))
      (node (ref "C707") (pin "1") (pinfunction "1_1") (pintype "passive"))
      (node (ref "C708") (pin "1") (pinfunction "1_1") (pintype "passive"))
      (node (ref "C709") (pin "1") (pinfunction "1_1") (pintype "passive"))
      (node (ref "C710") (pin "1") (pinfunction "1_1") (pintype "passive"))
      (node (ref "C711") (pin "1") (pinfunction "1_1") (pintype "passive"))
      (node (ref "C712") (pin "2") (pinfunction "2_2") (pintype "passive"))
      (node (ref "C713") (pin "2") (pinfunction "2_2") (pintype "passive"))
      (node (ref "C714") (pin "2") (pinfunction "2_2") (pintype "passive"))
      (node (ref "C715") (pin "2") (pinfunction "2_2") (pintype "passive"))
      (node (ref "C716") (pin "1") (pinfunction "1_1") (pintype "passive"))
      (node (ref "C717") (pin "1") (pinfunction "1_1") (pintype "passive"))
      (node (ref "C718") (pin "1") (pinfunction "1_1") (pintype "passive"))
      (node (ref "C719") (pin "1") (pinfunction "1_1") (pintype "passive"))
      (node (ref "C720") (pin "1") (pinfunction "1_1") (pintype "passive"))
      (node (ref "C721") (pin "1") (pinfunction "1_1") (pintype "passive"))
      (node (ref "C722") (pin "1") (pinfunction "1_1") (pintype "passive"))
      (node (ref "C723") (pin "1") (pinfunction "1_1") (pintype "passive"))
      (node (ref "C724") (pin "1") (pinfunction "1_1") (pintype "passive"))
      (node (ref "C725") (pin "1") (pinfunction "1_1") (pintype "passive"))
      (node (ref "C726") (pin "1") (pinfunction "1_1") (pintype "passive"))
      (node (ref "C727") (pin "1") (pinfunction "1_1") (pintype "passive"))
      (node (ref "C728") (pin "1") (pinfunction "1_1") (pintype "passive"))
      (node (ref "C729") (pin "1") (pinfunction "1_1") (pintype "passive"))
      (node (ref "C730") (pin "1") (pinfunction "1_1") (pintype "passive"))
      (node (ref "C731") (pin "1") (pinfunction "1_1") (pintype "passive"))
      (node (ref "C732") (pin "1") (pinfunction "1_1") (pintype "passive"))
      (node (ref "C733") (pin "1") (pinfunction "1_1") (pintype "passive"))
      (node (ref "C734") (pin "1") (pinfunction "1_1") (pintype "passive"))
      (node (ref "C735") (pin "1") (pinfunction "1_1") (pintype "passive"))
      (node (ref "C736") (pin "1") (pinfunction "1_1") (pintype "passive"))
      (node (ref "C737") (pin "1") (pinfunction "1_1") (pintype "passive"))
      (node (ref "C738") (pin "1") (pinfunction "1_1") (pintype "passive"))
      (node (ref "C739") (pin "1") (pinfunction "1_1") (pintype "passive"))
      (node (ref "C740") (pin "1") (pinfunction "1_1") (pintype "passive"))
      (node (ref "C741") (pin "1") (pinfunction "1_1") (pintype "passive"))
      (node (ref "C742") (pin "1") (pinfunction "1_1") (pintype "passive"))
      (node (ref "C743") (pin "1") (pinfunction "1_1") (pintype "passive"))
      (node (ref "C744") (pin "1") (pinfunction "1_1") (pintype "passive"))
      (node (ref "C745") (pin "1") (pinfunction "1_1") (pintype "passive"))
      (node (ref "C746") (pin "1") (pinfunction "1_1") (pintype "passive"))
      (node (ref "C747") (pin "1") (pinfunction "1_1") (pintype "passive"))
      (node (ref "C748") (pin "1") (pinfunction "1_1") (pintype "passive"))
      (node (ref "IC2") (pin "A1") (pinfunction "GND_A1") (pintype "power_in"))
      (node (ref "IC2") (pin "A11") (pinfunction "GND_A11") (pintype "power_in"))
      (node (ref "IC2") (pin "A12") (pinfunction "GND_A12") (pintype "power_in"))
      (node (ref "IC2") (pin "A14") (pinfunction "GND_A14") (pintype "power_in"))
      (node (ref "IC2") (pin "A16") (pinfunction "GND_A16") (pintype "power_in"))
      (node (ref "IC2") (pin "A18") (pinfunction "GND_A18") (pintype "power_in"))
      (node (ref "IC2") (pin "A20") (pinfunction "GND_A20") (pintype "power_in"))
      (node (ref "IC2") (pin "A22") (pinfunction "GND_A22") (pintype "power_in"))
      (node (ref "IC2") (pin "A24") (pinfunction "GND_A24") (pintype "power_in"))
      (node (ref "IC2") (pin "A26") (pinfunction "GND_A26") (pintype "power_in"))
      (node (ref "IC2") (pin "AA1") (pinfunction "GND_AA1") (pintype "power_in"))
      (node (ref "IC2") (pin "AA11") (pinfunction "GND_AA11") (pintype "power_in"))
      (node (ref "IC2") (pin "AA12") (pinfunction "GND_AA12") (pintype "power_in"))
      (node (ref "IC2") (pin "AA14") (pinfunction "GND_AA14") (pintype "power_in"))
      (node (ref "IC2") (pin "AA16") (pinfunction "GND_AA16") (pintype "power_in"))
      (node (ref "IC2") (pin "AA18") (pinfunction "GND_AA18") (pintype "power_in"))
      (node (ref "IC2") (pin "AA20") (pinfunction "GND_AA20") (pintype "power_in"))
      (node (ref "IC2") (pin "AA22") (pinfunction "GND_AA22") (pintype "power_in"))
      (node (ref "IC2") (pin "AA26") (pinfunction "GND_AA26") (pintype "power_in"))
      (node (ref "IC2") (pin "AB13") (pinfunction "GND_AB13") (pintype "power_in"))
      (node (ref "IC2") (pin "AB15") (pinfunction "GND_AB15") (pintype "power_in"))
      (node (ref "IC2") (pin "AB17") (pinfunction "GND_AB17") (pintype "power_in"))
      (node (ref "IC2") (pin "AB19") (pinfunction "GND_AB19") (pintype "power_in"))
      (node (ref "IC2") (pin "AB21") (pinfunction "GND_AB21") (pintype "power_in"))
      (node (ref "IC2") (pin "AB23") (pinfunction "GND_AB23") (pintype "power_in"))
      (node (ref "IC2") (pin "AB33") (pinfunction "GND_AB33") (pintype "power_in"))
      (node (ref "IC2") (pin "AB8") (pinfunction "GND_AB8") (pintype "power_in"))
      (node (ref "IC2") (pin "AC12") (pinfunction "GND_AC12") (pintype "power_in"))
      (node (ref "IC2") (pin "AC14") (pinfunction "GND_AC14") (pintype "power_in"))
      (node (ref "IC2") (pin "AC16") (pinfunction "GND_AC16") (pintype "power_in"))
      (node (ref "IC2") (pin "AC18") (pinfunction "GND_AC18") (pintype "power_in"))
      (node (ref "IC2") (pin "AC20") (pinfunction "GND_AC20") (pintype "power_in"))
      (node (ref "IC2") (pin "AC22") (pinfunction "GND_AC22") (pintype "power_in"))
      (node (ref "IC2") (pin "AC30") (pinfunction "GND_AC30") (pintype "power_in"))
      (node (ref "IC2") (pin "AC5") (pinfunction "GND_AC5") (pintype "power_in"))
      (node (ref "IC2") (pin "AD15") (pinfunction "GND_AD15") (pintype "power_in"))
      (node (ref "IC2") (pin "AD17") (pinfunction "GND_AD17") (pintype "power_in"))
      (node (ref "IC2") (pin "AD19") (pinfunction "GND_AD19") (pintype "power_in"))
      (node (ref "IC2") (pin "AD2") (pinfunction "GND_AD2") (pintype "power_in"))
      (node (ref "IC2") (pin "AD21") (pinfunction "GND_AD21") (pintype "power_in"))
      (node (ref "IC2") (pin "AD27") (pinfunction "GND_AD27") (pintype "power_in"))
      (node (ref "IC2") (pin "AE16") (pinfunction "GND_AE16") (pintype "power_in"))
      (node (ref "IC2") (pin "AE18") (pinfunction "GND_AE18") (pintype "power_in"))
      (node (ref "IC2") (pin "AE20") (pinfunction "GND_AE20") (pintype "power_in"))
      (node (ref "IC2") (pin "AE22") (pinfunction "GND_AE22") (pintype "power_in"))
      (node (ref "IC2") (pin "AE24") (pinfunction "GND_AE24") (pintype "power_in"))
      (node (ref "IC2") (pin "AE34") (pinfunction "GND_AE34") (pintype "power_in"))
      (node (ref "IC2") (pin "AE9") (pinfunction "GND_AE9") (pintype "power_in"))
      (node (ref "IC2") (pin "AF13") (pinfunction "GND_AF13") (pintype "power_in"))
      (node (ref "IC2") (pin "AF14") (pinfunction "GND_AF14") (pintype "power_in"))
      (node (ref "IC2") (pin "AF15") (pinfunction "GND_AF15") (pintype "power_in"))
      (node (ref "IC2") (pin "AF16") (pinfunction "GND_AF16") (pintype "power_in"))
      (node (ref "IC2") (pin "AF17") (pinfunction "GND_AF17") (pintype "power_in"))
      (node (ref "IC2") (pin "AF18") (pinfunction "GND_AF18") (pintype "power_in"))
      (node (ref "IC2") (pin "AF19") (pinfunction "GND_AF19") (pintype "power_in"))
      (node (ref "IC2") (pin "AF20") (pinfunction "GND_AF20") (pintype "power_in"))
      (node (ref "IC2") (pin "AF21") (pinfunction "GND_AF21") (pintype "power_in"))
      (node (ref "IC2") (pin "AF22") (pinfunction "GND_AF22") (pintype "power_in"))
      (node (ref "IC2") (pin "AF31") (pinfunction "GND_AF31") (pintype "power_in"))
      (node (ref "IC2") (pin "AF6") (pinfunction "GND_AF6") (pintype "power_in"))
      (node (ref "IC2") (pin "AG13") (pinfunction "GND_AG13") (pintype "power_in"))
      (node (ref "IC2") (pin "AG22") (pinfunction "GND_AG22") (pintype "power_in"))
      (node (ref "IC2") (pin "AG23") (pinfunction "GND_AG23") (pintype "power_in"))
      (node (ref "IC2") (pin "AG28") (pinfunction "GND_AG28") (pintype "power_in"))
      (node (ref "IC2") (pin "AG3") (pinfunction "GND_AG3") (pintype "power_in"))
      (node (ref "IC2") (pin "AH10") (pinfunction "GND_AH10") (pintype "power_in"))
      (node (ref "IC2") (pin "AH12") (pinfunction "GND_AH12") (pintype "power_in"))
      (node (ref "IC2") (pin "AH13") (pinfunction "GND_AH13") (pintype "power_in"))
      (node (ref "IC2") (pin "AH15") (pinfunction "GND_AH15") (pintype "power_in"))
      (node (ref "IC2") (pin "AH17") (pinfunction "GND_AH17") (pintype "power_in"))
      (node (ref "IC2") (pin "AH19") (pinfunction "GND_AH19") (pintype "power_in"))
      (node (ref "IC2") (pin "AH21") (pinfunction "GND_AH21") (pintype "power_in"))
      (node (ref "IC2") (pin "AH23") (pinfunction "GND_AH23") (pintype "power_in"))
      (node (ref "IC2") (pin "AH25") (pinfunction "GND_AH25") (pintype "power_in"))
      (node (ref "IC2") (pin "AJ12") (pinfunction "GND_AJ12") (pintype "power_in"))
      (node (ref "IC2") (pin "AJ23") (pinfunction "GND_AJ23") (pintype "power_in"))
      (node (ref "IC2") (pin "AJ32") (pinfunction "GND_AJ32") (pintype "power_in"))
      (node (ref "IC2") (pin "AJ7") (pinfunction "GND_AJ7") (pintype "power_in"))
      (node (ref "IC2") (pin "AK12") (pinfunction "GND_AK12") (pintype "power_in"))
      (node (ref "IC2") (pin "AK14") (pinfunction "GND_AK14") (pintype "power_in"))
      (node (ref "IC2") (pin "AK16") (pinfunction "GND_AK16") (pintype "power_in"))
      (node (ref "IC2") (pin "AK18") (pinfunction "GND_AK18") (pintype "power_in"))
      (node (ref "IC2") (pin "AK20") (pinfunction "GND_AK20") (pintype "power_in"))
      (node (ref "IC2") (pin "AK22") (pinfunction "GND_AK22") (pintype "power_in"))
      (node (ref "IC2") (pin "AK23") (pinfunction "GND_AK23") (pintype "power_in"))
      (node (ref "IC2") (pin "AK24") (pinfunction "GND_AK24") (pintype "power_in"))
      (node (ref "IC2") (pin "AK29") (pinfunction "GND_AK29") (pintype "power_in"))
      (node (ref "IC2") (pin "AK4") (pinfunction "GND_AK4") (pintype "power_in"))
      (node (ref "IC2") (pin "AL1") (pinfunction "GND_AL1") (pintype "power_in"))
      (node (ref "IC2") (pin "AL11") (pinfunction "GND_AL11") (pintype "power_in"))
      (node (ref "IC2") (pin "AL12") (pinfunction "GND_AL12") (pintype "power_in"))
      (node (ref "IC2") (pin "AL23") (pinfunction "GND_AL23") (pintype "power_in"))
      (node (ref "IC2") (pin "AL26") (pinfunction "GND_AL26") (pintype "power_in"))
      (node (ref "IC2") (pin "AM12") (pinfunction "GND_AM12") (pintype "power_in"))
      (node (ref "IC2") (pin "AM13") (pinfunction "GND_AM13") (pintype "power_in"))
      (node (ref "IC2") (pin "AM15") (pinfunction "GND_AM15") (pintype "power_in"))
      (node (ref "IC2") (pin "AM17") (pinfunction "GND_AM17") (pintype "power_in"))
      (node (ref "IC2") (pin "AM19") (pinfunction "GND_AM19") (pintype "power_in"))
      (node (ref "IC2") (pin "AM21") (pinfunction "GND_AM21") (pintype "power_in"))
      (node (ref "IC2") (pin "AM23") (pinfunction "GND_AM23") (pintype "power_in"))
      (node (ref "IC2") (pin "AM24") (pinfunction "GND_AM24") (pintype "power_in"))
      (node (ref "IC2") (pin "AM33") (pinfunction "GND_AM33") (pintype "power_in"))
      (node (ref "IC2") (pin "AM8") (pinfunction "GND_AM8") (pintype "power_in"))
      (node (ref "IC2") (pin "AN12") (pinfunction "GND_AN12") (pintype "power_in"))
      (node (ref "IC2") (pin "AN24") (pinfunction "GND_AN24") (pintype "power_in"))
      (node (ref "IC2") (pin "AN30") (pinfunction "GND_AN30") (pintype "power_in"))
      (node (ref "IC2") (pin "AN5") (pinfunction "GND_AN5") (pintype "power_in"))
      (node (ref "IC2") (pin "AP12") (pinfunction "GND_AP12") (pintype "power_in"))
      (node (ref "IC2") (pin "AP14") (pinfunction "GND_AP14") (pintype "power_in"))
      (node (ref "IC2") (pin "AP16") (pinfunction "GND_AP16") (pintype "power_in"))
      (node (ref "IC2") (pin "AP18") (pinfunction "GND_AP18") (pintype "power_in"))
      (node (ref "IC2") (pin "AP2") (pinfunction "GND_AP2") (pintype "power_in"))
      (node (ref "IC2") (pin "AP20") (pinfunction "GND_AP20") (pintype "power_in"))
      (node (ref "IC2") (pin "AP22") (pinfunction "GND_AP22") (pintype "power_in"))
      (node (ref "IC2") (pin "AP24") (pinfunction "GND_AP24") (pintype "power_in"))
      (node (ref "IC2") (pin "AP27") (pinfunction "GND_AP27") (pintype "power_in"))
      (node (ref "IC2") (pin "B12") (pinfunction "GND_B12") (pintype "power_in"))
      (node (ref "IC2") (pin "B24") (pinfunction "GND_B24") (pintype "power_in"))
      (node (ref "IC2") (pin "B33") (pinfunction "GND_B33") (pintype "power_in"))
      (node (ref "IC2") (pin "B8") (pinfunction "GND_B8") (pintype "power_in"))
      (node (ref "IC2") (pin "C12") (pinfunction "GND_C12") (pintype "power_in"))
      (node (ref "IC2") (pin "C13") (pinfunction "GND_C13") (pintype "power_in"))
      (node (ref "IC2") (pin "C15") (pinfunction "GND_C15") (pintype "power_in"))
      (node (ref "IC2") (pin "C17") (pinfunction "GND_C17") (pintype "power_in"))
      (node (ref "IC2") (pin "C19") (pinfunction "GND_C19") (pintype "power_in"))
      (node (ref "IC2") (pin "C21") (pinfunction "GND_C21") (pintype "power_in"))
      (node (ref "IC2") (pin "C23") (pinfunction "GND_C23") (pintype "power_in"))
      (node (ref "IC2") (pin "C24") (pinfunction "GND_C24") (pintype "power_in"))
      (node (ref "IC2") (pin "C30") (pinfunction "GND_C30") (pintype "power_in"))
      (node (ref "IC2") (pin "C5") (pinfunction "GND_C5") (pintype "power_in"))
      (node (ref "IC2") (pin "D12") (pinfunction "GND_D12") (pintype "power_in"))
      (node (ref "IC2") (pin "D2") (pinfunction "GND_D2") (pintype "power_in"))
      (node (ref "IC2") (pin "D23") (pinfunction "GND_D23") (pintype "power_in"))
      (node (ref "IC2") (pin "D27") (pinfunction "GND_D27") (pintype "power_in"))
      (node (ref "IC2") (pin "E12") (pinfunction "GND_E12") (pintype "power_in"))
      (node (ref "IC2") (pin "E14") (pinfunction "GND_E14") (pintype "power_in"))
      (node (ref "IC2") (pin "E16") (pinfunction "GND_E16") (pintype "power_in"))
      (node (ref "IC2") (pin "E18") (pinfunction "GND_E18") (pintype "power_in"))
      (node (ref "IC2") (pin "E20") (pinfunction "GND_E20") (pintype "power_in"))
      (node (ref "IC2") (pin "E22") (pinfunction "GND_E22") (pintype "power_in"))
      (node (ref "IC2") (pin "E23") (pinfunction "GND_E23") (pintype "power_in"))
      (node (ref "IC2") (pin "E24") (pinfunction "GND_E24") (pintype "power_in"))
      (node (ref "IC2") (pin "E34") (pinfunction "GND_E34") (pintype "power_in"))
      (node (ref "IC2") (pin "E9") (pinfunction "GND_E9") (pintype "power_in"))
      (node (ref "IC2") (pin "F12") (pinfunction "GND_F12") (pintype "power_in"))
      (node (ref "IC2") (pin "F23") (pinfunction "GND_F23") (pintype "power_in"))
      (node (ref "IC2") (pin "F31") (pinfunction "GND_F31") (pintype "power_in"))
      (node (ref "IC2") (pin "F6") (pinfunction "GND_F6") (pintype "power_in"))
      (node (ref "IC2") (pin "G12") (pinfunction "GND_G12") (pintype "power_in"))
      (node (ref "IC2") (pin "G13") (pinfunction "GND_G13") (pintype "power_in"))
      (node (ref "IC2") (pin "G15") (pinfunction "GND_G15") (pintype "power_in"))
      (node (ref "IC2") (pin "G17") (pinfunction "GND_G17") (pintype "power_in"))
      (node (ref "IC2") (pin "G19") (pinfunction "GND_G19") (pintype "power_in"))
      (node (ref "IC2") (pin "G21") (pinfunction "GND_G21") (pintype "power_in"))
      (node (ref "IC2") (pin "G23") (pinfunction "GND_G23") (pintype "power_in"))
      (node (ref "IC2") (pin "G28") (pinfunction "GND_G28") (pintype "power_in"))
      (node (ref "IC2") (pin "G3") (pinfunction "GND_G3") (pintype "power_in"))
      (node (ref "IC2") (pin "H10") (pinfunction "GND_H10") (pintype "power_in"))
      (node (ref "IC2") (pin "H13") (pinfunction "GND_H13") (pintype "power_in"))
      (node (ref "IC2") (pin "H22") (pinfunction "GND_H22") (pintype "power_in"))
      (node (ref "IC2") (pin "H23") (pinfunction "GND_H23") (pintype "power_in"))
      (node (ref "IC2") (pin "H25") (pinfunction "GND_H25") (pintype "power_in"))
      (node (ref "IC2") (pin "J13") (pinfunction "GND_J13") (pintype "power_in"))
      (node (ref "IC2") (pin "J14") (pinfunction "GND_J14") (pintype "power_in"))
      (node (ref "IC2") (pin "J15") (pinfunction "GND_J15") (pintype "power_in"))
      (node (ref "IC2") (pin "J16") (pinfunction "GND_J16") (pintype "power_in"))
      (node (ref "IC2") (pin "J17") (pinfunction "GND_J17") (pintype "power_in"))
      (node (ref "IC2") (pin "J18") (pinfunction "GND_J18") (pintype "power_in"))
      (node (ref "IC2") (pin "J19") (pinfunction "GND_J19") (pintype "power_in"))
      (node (ref "IC2") (pin "J20") (pinfunction "GND_J20") (pintype "power_in"))
      (node (ref "IC2") (pin "J21") (pinfunction "GND_J21") (pintype "power_in"))
      (node (ref "IC2") (pin "J22") (pinfunction "GND_J22") (pintype "power_in"))
      (node (ref "IC2") (pin "J32") (pinfunction "GND_J32") (pintype "power_in"))
      (node (ref "IC2") (pin "J7") (pinfunction "GND_J7") (pintype "power_in"))
      (node (ref "IC2") (pin "K15") (pinfunction "GND_K15") (pintype "power_in"))
      (node (ref "IC2") (pin "K17") (pinfunction "GND_K17") (pintype "power_in"))
      (node (ref "IC2") (pin "K19") (pinfunction "GND_K19") (pintype "power_in"))
      (node (ref "IC2") (pin "K29") (pinfunction "GND_K29") (pintype "power_in"))
      (node (ref "IC2") (pin "K4") (pinfunction "GND_K4") (pintype "power_in"))
      (node (ref "IC2") (pin "L1") (pinfunction "GND_L1") (pintype "power_in"))
      (node (ref "IC2") (pin "L11") (pinfunction "GND_L11") (pintype "power_in"))
      (node (ref "IC2") (pin "L14") (pinfunction "GND_L14") (pintype "power_in"))
      (node (ref "IC2") (pin "L16") (pinfunction "GND_L16") (pintype "power_in"))
      (node (ref "IC2") (pin "L18") (pinfunction "GND_L18") (pintype "power_in"))
      (node (ref "IC2") (pin "L20") (pinfunction "GND_L20") (pintype "power_in"))
      (node (ref "IC2") (pin "L26") (pinfunction "GND_L26") (pintype "power_in"))
      (node (ref "IC2") (pin "M13") (pinfunction "GND_M13") (pintype "power_in"))
      (node (ref "IC2") (pin "M15") (pinfunction "GND_M15") (pintype "power_in"))
      (node (ref "IC2") (pin "M17") (pinfunction "GND_M17") (pintype "power_in"))
      (node (ref "IC2") (pin "M19") (pinfunction "GND_M19") (pintype "power_in"))
      (node (ref "IC2") (pin "M21") (pinfunction "GND_M21") (pintype "power_in"))
      (node (ref "IC2") (pin "M23") (pinfunction "GND_M23") (pintype "power_in"))
      (node (ref "IC2") (pin "M33") (pinfunction "GND_M33") (pintype "power_in"))
      (node (ref "IC2") (pin "M8") (pinfunction "GND_M8") (pintype "power_in"))
      (node (ref "IC2") (pin "N12") (pinfunction "GND_N12") (pintype "power_in"))
      (node (ref "IC2") (pin "N14") (pinfunction "GND_N14") (pintype "power_in"))
      (node (ref "IC2") (pin "N16") (pinfunction "GND_N16") (pintype "power_in"))
      (node (ref "IC2") (pin "N18") (pinfunction "GND_N18") (pintype "power_in"))
      (node (ref "IC2") (pin "N20") (pinfunction "GND_N20") (pintype "power_in"))
      (node (ref "IC2") (pin "N22") (pinfunction "GND_N22") (pintype "power_in"))
      (node (ref "IC2") (pin "N30") (pinfunction "GND_N30") (pintype "power_in"))
      (node (ref "IC2") (pin "N5") (pinfunction "GND_N5") (pintype "power_in"))
      (node (ref "IC2") (pin "P13") (pinfunction "GND_P13") (pintype "power_in"))
      (node (ref "IC2") (pin "P15") (pinfunction "GND_P15") (pintype "power_in"))
      (node (ref "IC2") (pin "P17") (pinfunction "GND_P17") (pintype "power_in"))
      (node (ref "IC2") (pin "P19") (pinfunction "GND_P19") (pintype "power_in"))
      (node (ref "IC2") (pin "P2") (pinfunction "GND_P2") (pintype "power_in"))
      (node (ref "IC2") (pin "P21") (pinfunction "GND_P21") (pintype "power_in"))
      (node (ref "IC2") (pin "P23") (pinfunction "GND_P23") (pintype "power_in"))
      (node (ref "IC2") (pin "P27") (pinfunction "GND_P27") (pintype "power_in"))
      (node (ref "IC2") (pin "R12") (pinfunction "GND_R12") (pintype "power_in"))
      (node (ref "IC2") (pin "R14") (pinfunction "GND_R14") (pintype "power_in"))
      (node (ref "IC2") (pin "R16") (pinfunction "GND_R16") (pintype "power_in"))
      (node (ref "IC2") (pin "R18") (pinfunction "GND_R18") (pintype "power_in"))
      (node (ref "IC2") (pin "R20") (pinfunction "GND_R20") (pintype "power_in"))
      (node (ref "IC2") (pin "R22") (pinfunction "GND_R22") (pintype "power_in"))
      (node (ref "IC2") (pin "R24") (pinfunction "GND_R24") (pintype "power_in"))
      (node (ref "IC2") (pin "R34") (pinfunction "GND_R34") (pintype "power_in"))
      (node (ref "IC2") (pin "R9") (pinfunction "GND_R9") (pintype "power_in"))
      (node (ref "IC2") (pin "T13") (pinfunction "GND_T13") (pintype "power_in"))
      (node (ref "IC2") (pin "T15") (pinfunction "GND_T15") (pintype "power_in"))
      (node (ref "IC2") (pin "T17") (pinfunction "GNDADC_0_T17") (pintype "power_in"))
      (node (ref "IC2") (pin "T19") (pinfunction "GND_T19") (pintype "power_in"))
      (node (ref "IC2") (pin "T21") (pinfunction "GND_T21") (pintype "power_in"))
      (node (ref "IC2") (pin "T23") (pinfunction "GND_T23") (pintype "power_in"))
      (node (ref "IC2") (pin "T31") (pinfunction "GND_T31") (pintype "power_in"))
      (node (ref "IC2") (pin "T6") (pinfunction "GND_T6") (pintype "power_in"))
      (node (ref "IC2") (pin "U12") (pinfunction "GND_U12") (pintype "power_in"))
      (node (ref "IC2") (pin "U14") (pinfunction "GND_U14") (pintype "power_in"))
      (node (ref "IC2") (pin "U16") (pinfunction "GND_U16") (pintype "power_in"))
      (node (ref "IC2") (pin "U17") (pinfunction "VREFN_0_U17") (pintype "input"))
      (node (ref "IC2") (pin "U20") (pinfunction "GND_U20") (pintype "power_in"))
      (node (ref "IC2") (pin "U22") (pinfunction "GND_U22") (pintype "power_in"))
      (node (ref "IC2") (pin "U28") (pinfunction "GND_U28") (pintype "power_in"))
      (node (ref "IC2") (pin "U3") (pinfunction "GND_U3") (pintype "power_in"))
      (node (ref "IC2") (pin "V10") (pinfunction "GND_V10") (pintype "power_in"))
      (node (ref "IC2") (pin "V13") (pinfunction "GND_V13") (pintype "power_in"))
      (node (ref "IC2") (pin "V15") (pinfunction "GND_V15") (pintype "power_in"))
      (node (ref "IC2") (pin "V18") (pinfunction "VREFP_0_V18") (pintype "input"))
      (node (ref "IC2") (pin "V19") (pinfunction "GND_V19") (pintype "power_in"))
      (node (ref "IC2") (pin "V21") (pinfunction "GND_V21") (pintype "power_in"))
      (node (ref "IC2") (pin "V23") (pinfunction "GND_V23") (pintype "power_in"))
      (node (ref "IC2") (pin "V25") (pinfunction "GND_V25") (pintype "power_in"))
      (node (ref "IC2") (pin "W12") (pinfunction "GND_W12") (pintype "power_in"))
      (node (ref "IC2") (pin "W14") (pinfunction "GND_W14") (pintype "power_in"))
      (node (ref "IC2") (pin "W16") (pinfunction "GND_W16") (pintype "power_in"))
      (node (ref "IC2") (pin "W20") (pinfunction "GND_W20") (pintype "power_in"))
      (node (ref "IC2") (pin "W22") (pinfunction "GND_W22") (pintype "power_in"))
      (node (ref "IC2") (pin "W32") (pinfunction "GND_W32") (pintype "power_in"))
      (node (ref "IC2") (pin "W7") (pinfunction "GND_W7") (pintype "power_in"))
      (node (ref "IC2") (pin "Y13") (pinfunction "GND_Y13") (pintype "power_in"))
      (node (ref "IC2") (pin "Y15") (pinfunction "GND_Y15") (pintype "power_in"))
      (node (ref "IC2") (pin "Y17") (pinfunction "GND_Y17") (pintype "power_in"))
      (node (ref "IC2") (pin "Y19") (pinfunction "GND_Y19") (pintype "power_in"))
      (node (ref "IC2") (pin "Y21") (pinfunction "GND_Y21") (pintype "power_in"))
      (node (ref "IC2") (pin "Y23") (pinfunction "GND_Y23") (pintype "power_in"))
      (node (ref "IC2") (pin "Y29") (pinfunction "GND_Y29") (pintype "power_in"))
      (node (ref "IC2") (pin "Y4") (pinfunction "GND_Y4") (pintype "power_in"))
    )
    (net (code "2") (name "MGTAVCC") (class "Default")
      (node (ref "FB5") (pin "1") (pinfunction "1_1") (pintype "passive"))
      (node (ref "FB6") (pin "1") (pinfunction "1_1") (pintype "passive"))
    )
    (net (code "3") (name "MGTAVCC_G10") (class "Default")
      (node (ref "C253") (pin "2") (pinfunction "2_2") (pintype "passive"))
      (node (ref "C254") (pin "2") (pinfunction "2_2") (pintype "passive"))
      (node (ref "C267") (pin "2") (pinfunction "2_2") (pintype "passive"))
      (node (ref "C502") (pin "2") (pinfunction "2_2") (pintype "passive"))
      (node (ref "C730") (pin "2") (pinfunction "2_2") (pintype "passive"))
      (node (ref "C731") (pin "2") (pinfunction "2_2") (pintype "passive"))
      (node (ref "C734") (pin "2") (pinfunction "2_2") (pintype "passive"))
      (node (ref "C735") (pin "2") (pinfunction "2_2") (pintype "passive"))
      (node (ref "C736") (pin "2") (pinfunction "2_2") (pintype "passive"))
      (node (ref "C737") (pin "2") (pinfunction "2_2") (pintype "passive"))
      (node (ref "FB5") (pin "2") (pinfunction "2_2") (pintype "passive"))
      (node (ref "IC2") (pin "AG15") (pinfunction "MGTAVCC_G10_AG15") (pintype "power_in"))
      (node (ref "IC2") (pin "AG17") (pinfunction "MGTAVCC_G10_AG17") (pintype "power_in"))
      (node (ref "IC2") (pin "AG19") (pinfunction "MGTAVCC_G10_AG19") (pintype "power_in"))
      (node (ref "IC2") (pin "AG21") (pinfunction "MGTAVCC_G10_AG21") (pintype "power_in"))
      (node (ref "IC2") (pin "AJ14") (pinfunction "MGTAVCC_G10_AJ14") (pintype "power_in"))
      (node (ref "IC2") (pin "AJ16") (pinfunction "MGTAVCC_G10_AJ16") (pintype "power_in"))
      (node (ref "IC2") (pin "AJ18") (pinfunction "MGTAVCC_G10_AJ18") (pintype "power_in"))
      (node (ref "IC2") (pin "AJ20") (pinfunction "MGTAVCC_G10_AJ20") (pintype "power_in"))
    )
    (net (code "4") (name "MGTAVCC_G11") (class "Default")
      (node (ref "C252") (pin "2") (pinfunction "2_2") (pintype "passive"))
      (node (ref "C262") (pin "2") (pinfunction "2_2") (pintype "passive"))
      (node (ref "C263") (pin "2") (pinfunction "2_2") (pintype "passive"))
      (node (ref "C272") (pin "2") (pinfunction "2_2") (pintype "passive"))
      (node (ref "C504") (pin "2") (pinfunction "2_2") (pintype "passive"))
      (node (ref "C601") (pin "2") (pinfunction "2_2") (pintype "passive"))
      (node (ref "C603") (pin "2") (pinfunction "2_2") (pintype "passive"))
      (node (ref "C604") (pin "2") (pinfunction "2_2") (pintype "passive"))
      (node (ref "C732") (pin "2") (pinfunction "2_2") (pintype "passive"))
      (node (ref "C733") (pin "2") (pinfunction "2_2") (pintype "passive"))
      (node (ref "FB6") (pin "2") (pinfunction "2_2") (pintype "passive"))
      (node (ref "IC2") (pin "F14") (pinfunction "MGTAVCC_G11_F14") (pintype "power_in"))
      (node (ref "IC2") (pin "F16") (pinfunction "MGTAVCC_G11_F16") (pintype "power_in"))
      (node (ref "IC2") (pin "F18") (pinfunction "MGTAVCC_G11_F18") (pintype "power_in"))
      (node (ref "IC2") (pin "F20") (pinfunction "MGTAVCC_G11_F20") (pintype "power_in"))
      (node (ref "IC2") (pin "H15") (pinfunction "MGTAVCC_G11_H15") (pintype "power_in"))
      (node (ref "IC2") (pin "H17") (pinfunction "MGTAVCC_G11_H17") (pintype "power_in"))
      (node (ref "IC2") (pin "H19") (pinfunction "MGTAVCC_G11_H19") (pintype "power_in"))
      (node (ref "IC2") (pin "H21") (pinfunction "MGTAVCC_G11_H21") (pintype "power_in"))
    )
    (net (code "5") (name "MGTAVTT_G10") (class "Default")
      (node (ref "C251") (pin "2") (pinfunction "2_2") (pintype "passive"))
      (node (ref "C255") (pin "2") (pinfunction "2_2") (pintype "passive"))
      (node (ref "C257") (pin "2") (pinfunction "2_2") (pintype "passive"))
      (node (ref "C600") (pin "2") (pinfunction "2_2") (pintype "passive"))
      (node (ref "C605") (pin "2") (pinfunction "2_2") (pintype "passive"))
      (node (ref "C722") (pin "2") (pinfunction "2_2") (pintype "passive"))
      (node (ref "C725") (pin "2") (pinfunction "2_2") (pintype "passive"))
      (node (ref "C726") (pin "2") (pinfunction "2_2") (pintype "passive"))
      (node (ref "C729") (pin "2") (pinfunction "2_2") (pintype "passive"))
      (node (ref "FB8") (pin "2") (pinfunction "2_2") (pintype "passive"))
      (node (ref "IC2") (pin "AJ22") (pinfunction "MGTAVTT_G10_AJ22") (pintype "power_in"))
      (node (ref "IC2") (pin "AL13") (pinfunction "MGTAVTT_G10_AL13") (pintype "power_in"))
      (node (ref "IC2") (pin "AL15") (pinfunction "MGTAVTT_G10_AL15") (pintype "power_in"))
      (node (ref "IC2") (pin "AL17") (pinfunction "MGTAVTT_G10_AL17") (pintype "power_in"))
      (node (ref "IC2") (pin "AL19") (pinfunction "MGTAVTT_G10_AL19") (pintype "power_in"))
      (node (ref "IC2") (pin "AL21") (pinfunction "MGTAVTT_G10_AL21") (pintype "power_in"))
      (node (ref "IC2") (pin "AN14") (pinfunction "MGTAVTT_G10_AN14") (pintype "power_in"))
      (node (ref "IC2") (pin "AN16") (pinfunction "MGTAVTT_G10_AN16") (pintype "power_in"))
      (node (ref "IC2") (pin "AN18") (pinfunction "MGTAVTT_G10_AN18") (pintype "power_in"))
      (node (ref "IC2") (pin "AN20") (pinfunction "MGTAVTT_G10_AN20") (pintype "power_in"))
      (node (ref "IC2") (pin "AN22") (pinfunction "MGTAVTT_G10_AN22") (pintype "power_in"))
    )
    (net (code "6") (name "MGTAVTT_G11") (class "Default")
      (node (ref "C256") (pin "2") (pinfunction "2_2") (pintype "passive"))
      (node (ref "C258") (pin "2") (pinfunction "2_2") (pintype "passive"))
      (node (ref "C259") (pin "2") (pinfunction "2_2") (pintype "passive"))
      (node (ref "C268") (pin "2") (pinfunction "2_2") (pintype "passive"))
      (node (ref "C599") (pin "2") (pinfunction "2_2") (pintype "passive"))
      (node (ref "C723") (pin "2") (pinfunction "2_2") (pintype "passive"))
      (node (ref "C724") (pin "2") (pinfunction "2_2") (pintype "passive"))
      (node (ref "C727") (pin "2") (pinfunction "2_2") (pintype "passive"))
      (node (ref "C728") (pin "2") (pinfunction "2_2") (pintype "passive"))
      (node (ref "FB7") (pin "2") (pinfunction "2_2") (pintype "passive"))
      (node (ref "IC2") (pin "B14") (pinfunction "MGTAVTT_G11_B14") (pintype "power_in"))
      (node (ref "IC2") (pin "B16") (pinfunction "MGTAVTT_G11_B16") (pintype "power_in"))
      (node (ref "IC2") (pin "B18") (pinfunction "MGTAVTT_G11_B18") (pintype "power_in"))
      (node (ref "IC2") (pin "B20") (pinfunction "MGTAVTT_G11_B20") (pintype "power_in"))
      (node (ref "IC2") (pin "B22") (pinfunction "MGTAVTT_G11_B22") (pintype "power_in"))
      (node (ref "IC2") (pin "D13") (pinfunction "MGTAVTT_G11_D13") (pintype "power_in"))
      (node (ref "IC2") (pin "D15") (pinfunction "MGTAVTT_G11_D15") (pintype "power_in"))
      (node (ref "IC2") (pin "D17") (pinfunction "MGTAVTT_G11_D17") (pintype "power_in"))
      (node (ref "IC2") (pin "D19") (pinfunction "MGTAVTT_G11_D19") (pintype "power_in"))
      (node (ref "IC2") (pin "D21") (pinfunction "MGTAVTT_G11_D21") (pintype "power_in"))
      (node (ref "IC2") (pin "F22") (pinfunction "MGTAVTT_G11_F22") (pintype "power_in"))
    )
    (net (code "7") (name "P1V0") (class "Default")
      (node (ref "C229") (pin "2") (pinfunction "2_2") (pintype "passive"))
      (node (ref "C230") (pin "1") (pinfunction "1_1") (pintype "passive"))
      (node (ref "C231") (pin "1") (pinfunction "1_1") (pintype "passive"))
      (node (ref "C232") (pin "2") (pinfunction "2_2") (pintype "passive"))
      (node (ref "C233") (pin "2") (pinfunction "2_2") (pintype "passive"))
      (node (ref "C234") (pin "2") (pinfunction "2_2") (pintype "passive"))
      (node (ref "C235") (pin "2") (pinfunction "2_2") (pintype "passive"))
      (node (ref "C236") (pin "2") (pinfunction "2_2") (pintype "passive"))
      (node (ref "C237") (pin "2") (pinfunction "2_2") (pintype "passive"))
      (node (ref "C238") (pin "2") (pinfunction "2_2") (pintype "passive"))
      (node (ref "C239") (pin "2") (pinfunction "2_2") (pintype "passive"))
      (node (ref "C240") (pin "2") (pinfunction "2_2") (pintype "passive"))
      (node (ref "C241") (pin "2") (pinfunction "2_2") (pintype "passive"))
      (node (ref "C242") (pin "2") (pinfunction "2_2") (pintype "passive"))
      (node (ref "C283") (pin "2") (pinfunction "2_2") (pintype "passive"))
      (node (ref "C284") (pin "2") (pinfunction "2_2") (pintype "passive"))
      (node (ref "C285") (pin "2") (pinfunction "2_2") (pintype "passive"))
      (node (ref "C286") (pin "2") (pinfunction "2_2") (pintype "passive"))
      (node (ref "C287") (pin "2") (pinfunction "2_2") (pintype "passive"))
      (node (ref "C288") (pin "2") (pinfunction "2_2") (pintype "passive"))
      (node (ref "C291") (pin "2") (pinfunction "2_2") (pintype "passive"))
      (node (ref "C292") (pin "2") (pinfunction "2_2") (pintype "passive"))
      (node (ref "C293") (pin "2") (pinfunction "2_2") (pintype "passive"))
      (node (ref "C294") (pin "2") (pinfunction "2_2") (pintype "passive"))
      (node (ref "C295") (pin "2") (pinfunction "2_2") (pintype "passive"))
      (node (ref "C296") (pin "2") (pinfunction "2_2") (pintype "passive"))
      (node (ref "C549") (pin "2") (pinfunction "2_2") (pintype "passive"))
      (node (ref "C550") (pin "2") (pinfunction "2_2") (pintype "passive"))
      (node (ref "C551") (pin "2") (pinfunction "2_2") (pintype "passive"))
      (node (ref "C552") (pin "2") (pinfunction "2_2") (pintype "passive"))
      (node (ref "C553") (pin "2") (pinfunction "2_2") (pintype "passive"))
      (node (ref "C554") (pin "2") (pinfunction "2_2") (pintype "passive"))
      (node (ref "C555") (pin "2") (pinfunction "2_2") (pintype "passive"))
      (node (ref "C556") (pin "2") (pinfunction "2_2") (pintype "passive"))
      (node (ref "C557") (pin "2") (pinfunction "2_2") (pintype "passive"))
      (node (ref "C558") (pin "2") (pinfunction "2_2") (pintype "passive"))
      (node (ref "C559") (pin "2") (pinfunction "2_2") (pintype "passive"))
      (node (ref "C560") (pin "2") (pinfunction "2_2") (pintype "passive"))
      (node (ref "C561") (pin "2") (pinfunction "2_2") (pintype "passive"))
      (node (ref "C562") (pin "2") (pinfunction "2_2") (pintype "passive"))
      (node (ref "C563") (pin "2") (pinfunction "2_2") (pintype "passive"))
      (node (ref "C564") (pin "2") (pinfunction "2_2") (pintype "passive"))
      (node (ref "C565") (pin "2") (pinfunction "2_2") (pintype "passive"))
      (node (ref "C566") (pin "2") (pinfunction "2_2") (pintype "passive"))
      (node (ref "C576") (pin "2") (pinfunction "2_2") (pintype "passive"))
      (node (ref "C577") (pin "2") (pinfunction "2_2") (pintype "passive"))
      (node (ref "C578") (pin "2") (pinfunction "2_2") (pintype "passive"))
      (node (ref "C579") (pin "2") (pinfunction "2_2") (pintype "passive"))
      (node (ref "C580") (pin "2") (pinfunction "2_2") (pintype "passive"))
      (node (ref "C581") (pin "2") (pinfunction "2_2") (pintype "passive"))
      (node (ref "C582") (pin "2") (pinfunction "2_2") (pintype "passive"))
      (node (ref "C583") (pin "2") (pinfunction "2_2") (pintype "passive"))
      (node (ref "C585") (pin "2") (pinfunction "2_2") (pintype "passive"))
      (node (ref "C586") (pin "2") (pinfunction "2_2") (pintype "passive"))
      (node (ref "C602") (pin "1") (pinfunction "1_1") (pintype "passive"))
      (node (ref "C606") (pin "2") (pinfunction "2_2") (pintype "passive"))
      (node (ref "C607") (pin "2") (pinfunction "2_2") (pintype "passive"))
      (node (ref "C608") (pin "2") (pinfunction "2_2") (pintype "passive"))
      (node (ref "C609") (pin "2") (pinfunction "2_2") (pintype "passive"))
      (node (ref "C610") (pin "2") (pinfunction "2_2") (pintype "passive"))
      (node (ref "C611") (pin "2") (pinfunction "2_2") (pintype "passive"))
      (node (ref "C612") (pin "1") (pinfunction "1_1") (pintype "passive"))
      (node (ref "C740") (pin "2") (pinfunction "2_2") (pintype "passive"))
      (node (ref "C741") (pin "2") (pinfunction "2_2") (pintype "passive"))
      (node (ref "C742") (pin "2") (pinfunction "2_2") (pintype "passive"))
      (node (ref "C743") (pin "2") (pinfunction "2_2") (pintype "passive"))
      (node (ref "C744") (pin "2") (pinfunction "2_2") (pintype "passive"))
      (node (ref "C745") (pin "2") (pinfunction "2_2") (pintype "passive"))
      (node (ref "C746") (pin "2") (pinfunction "2_2") (pintype "passive"))
      (node (ref "C747") (pin "2") (pinfunction "2_2") (pintype "passive"))
      (node (ref "C748") (pin "2") (pinfunction "2_2") (pintype "passive"))
      (node (ref "IC2") (pin "AA15") (pinfunction "VCCINT_AA15") (pintype "power_in"))
      (node (ref "IC2") (pin "AA17") (pinfunction "VCCINT_AA17") (pintype "power_in"))
      (node (ref "IC2") (pin "AA19") (pinfunction "VCCINT_AA19") (pintype "power_in"))
      (node (ref "IC2") (pin "AB14") (pinfunction "VCCINT_AB14") (pintype "power_in"))
      (node (ref "IC2") (pin "AB16") (pinfunction "VCCINT_AB16") (pintype "power_in"))
      (node (ref "IC2") (pin "AB18") (pinfunction "VCCINT_AB18") (pintype "power_in"))
      (node (ref "IC2") (pin "AC15") (pinfunction "VCCINT_AC15") (pintype "power_in"))
      (node (ref "IC2") (pin "AC17") (pinfunction "VCCINT_AC17") (pintype "power_in"))
      (node (ref "IC2") (pin "AC19") (pinfunction "VCCINT_AC19") (pintype "power_in"))
      (node (ref "IC2") (pin "AD14") (pinfunction "VCCINT_AD14") (pintype "power_in"))
      (node (ref "IC2") (pin "AD16") (pinfunction "VCCINT_AD16") (pintype "power_in"))
      (node (ref "IC2") (pin "AD18") (pinfunction "VCCINT_AD18") (pintype "power_in"))
      (node (ref "IC2") (pin "AD20") (pinfunction "VCCINT_AD20") (pintype "power_in"))
      (node (ref "IC2") (pin "AD22") (pinfunction "VCCINT_AD22") (pintype "power_in"))
      (node (ref "IC2") (pin "AE15") (pinfunction "VCCINT_AE15") (pintype "power_in"))
      (node (ref "IC2") (pin "AE17") (pinfunction "VCCINT_AE17") (pintype "power_in"))
      (node (ref "IC2") (pin "AE19") (pinfunction "VCCINT_AE19") (pintype "power_in"))
      (node (ref "IC2") (pin "AE21") (pinfunction "VCCINT_AE21") (pintype "power_in"))
      (node (ref "IC2") (pin "K14") (pinfunction "VCCINT_K14") (pintype "power_in"))
      (node (ref "IC2") (pin "K16") (pinfunction "VCCINT_K16") (pintype "power_in"))
      (node (ref "IC2") (pin "K18") (pinfunction "VCCINT_K18") (pintype "power_in"))
      (node (ref "IC2") (pin "K20") (pinfunction "VCCINT_K20") (pintype "power_in"))
      (node (ref "IC2") (pin "L15") (pinfunction "VCCINT_L15") (pintype "power_in"))
      (node (ref "IC2") (pin "L17") (pinfunction "VCCINT_L17") (pintype "power_in"))
      (node (ref "IC2") (pin "L19") (pinfunction "VCCINT_L19") (pintype "power_in"))
      (node (ref "IC2") (pin "L21") (pinfunction "VCCINT_L21") (pintype "power_in"))
      (node (ref "IC2") (pin "M14") (pinfunction "VCCINT_M14") (pintype "power_in"))
      (node (ref "IC2") (pin "M16") (pinfunction "VCCINT_M16") (pintype "power_in"))
      (node (ref "IC2") (pin "M18") (pinfunction "VCCINT_M18") (pintype "power_in"))
      (node (ref "IC2") (pin "N15") (pinfunction "VCCINT_N15") (pintype "power_in"))
      (node (ref "IC2") (pin "N17") (pinfunction "VCCINT_N17") (pintype "power_in"))
      (node (ref "IC2") (pin "N19") (pinfunction "VCCINT_N19") (pintype "power_in"))
      (node (ref "IC2") (pin "P14") (pinfunction "VCCINT_P14") (pintype "power_in"))
      (node (ref "IC2") (pin "P16") (pinfunction "VCCINT_P16") (pintype "power_in"))
      (node (ref "IC2") (pin "P18") (pinfunction "VCCINT_P18") (pintype "power_in"))
      (node (ref "IC2") (pin "R15") (pinfunction "VCCINT_R15") (pintype "power_in"))
      (node (ref "IC2") (pin "R17") (pinfunction "VCCINT_R17") (pintype "power_in"))
      (node (ref "IC2") (pin "R19") (pinfunction "VCCINT_R19") (pintype "power_in"))
      (node (ref "IC2") (pin "T14") (pinfunction "VCCINT_T14") (pintype "power_in"))
      (node (ref "IC2") (pin "T16") (pinfunction "VCCINT_T16") (pintype "power_in"))
      (node (ref "IC2") (pin "U15") (pinfunction "VCCINT_U15") (pintype "power_in"))
      (node (ref "IC2") (pin "U19") (pinfunction "VCCINT_U19") (pintype "power_in"))
      (node (ref "IC2") (pin "V14") (pinfunction "VCCINT_V14") (pintype "power_in"))
      (node (ref "IC2") (pin "V16") (pinfunction "VCCINT_V16") (pintype "power_in"))
      (node (ref "IC2") (pin "W15") (pinfunction "VCCINT_W15") (pintype "power_in"))
      (node (ref "IC2") (pin "W19") (pinfunction "VCCINT_W19") (pintype "power_in"))
      (node (ref "IC2") (pin "Y14") (pinfunction "VCCINT_Y14") (pintype "power_in"))
      (node (ref "IC2") (pin "Y16") (pinfunction "VCCINT_Y16") (pintype "power_in"))
      (node (ref "IC2") (pin "Y18") (pinfunction "VCCINT_Y18") (pintype "power_in"))
      (node (ref "L10") (pin "1") (pinfunction "1_1") (pintype "passive"))
    )
    (net (code "8") (name "P1V2") (class "Default")
      (node (ref "FB7") (pin "1") (pinfunction "1_1") (pintype "passive"))
      (node (ref "FB8") (pin "1") (pinfunction "1_1") (pintype "passive"))
    )
    (net (code "9") (name "P1V5") (class "Default")
      (node (ref "C106") (pin "2") (pinfunction "2_2") (pintype "passive"))
      (node (ref "C107") (pin "2") (pinfunction "2_2") (pintype "passive"))
      (node (ref "C446") (pin "2") (pinfunction "2_2") (pintype "passive"))
      (node (ref "C447") (pin "1") (pinfunction "1_1") (pintype "passive"))
      (node (ref "C448") (pin "2") (pinfunction "2_2") (pintype "passive"))
      (node (ref "C449") (pin "2") (pinfunction "2_2") (pintype "passive"))
      (node (ref "C450") (pin "2") (pinfunction "2_2") (pintype "passive"))
      (node (ref "C451") (pin "2") (pinfunction "2_2") (pintype "passive"))
      (node (ref "C465") (pin "2") (pinfunction "2_2") (pintype "passive"))
      (node (ref "C478") (pin "2") (pinfunction "2_2") (pintype "passive"))
      (node (ref "C636") (pin "2") (pinfunction "2_2") (pintype "passive"))
      (node (ref "C637") (pin "2") (pinfunction "2_2") (pintype "passive"))
      (node (ref "C638") (pin "1") (pinfunction "1_1") (pintype "passive"))
      (node (ref "C639") (pin "2") (pinfunction "2_2") (pintype "passive"))
      (node (ref "C640") (pin "2") (pinfunction "2_2") (pintype "passive"))
      (node (ref "C641") (pin "2") (pinfunction "2_2") (pintype "passive"))
      (node (ref "C642") (pin "2") (pinfunction "2_2") (pintype "passive"))
      (node (ref "C643") (pin "2") (pinfunction "2_2") (pintype "passive"))
      (node (ref "IC2") (pin "AD7") (pinfunction "VCCO_33_AD7") (pintype "power_in"))
      (node (ref "IC2") (pin "AE4") (pinfunction "VCCO_33_AE4") (pintype "power_in"))
      (node (ref "IC2") (pin "AF1") (pinfunction "VCCO_33_AF1") (pintype "power_in"))
      (node (ref "IC2") (pin "AF11") (pinfunction "VCCO_33_AF11") (pintype "power_in"))
      (node (ref "IC2") (pin "AG8") (pinfunction "VCCO_33_AG8") (pintype "power_in"))
      (node (ref "IC2") (pin "AH5") (pinfunction "VCCO_33_AH5") (pintype "power_in"))
      (node (ref "IC2") (pin "AJ2") (pinfunction "VCCO_32_AJ2") (pintype "power_in"))
      (node (ref "IC2") (pin "AK9") (pinfunction "VCCO_32_AK9") (pintype "power_in"))
      (node (ref "IC2") (pin "AL6") (pinfunction "VCCO_32_AL6") (pintype "power_in"))
      (node (ref "IC2") (pin "AM3") (pinfunction "VCCO_32_AM3") (pintype "power_in"))
      (node (ref "IC2") (pin "AN10") (pinfunction "VCCO_32_AN10") (pintype "power_in"))
      (node (ref "IC2") (pin "AP7") (pinfunction "VCCO_32_AP7") (pintype "power_in"))
    )
    (net (code "10") (name "P1V8") (class "Default")
      (node (ref "L12") (pin "1") (pinfunction "1_1") (pintype "passive"))
    )
    (net (code "11") (name "P3V3") (class "Default")
      (node (ref "C260") (pin "2") (pinfunction "2_2") (pintype "passive"))
      (node (ref "C261") (pin "2") (pinfunction "2_2") (pintype "passive"))
      (node (ref "IC2") (pin "L13") (pinfunction "VCCO_0_L13") (pintype "power_in"))
      (node (ref "IC2") (pin "T11") (pinfunction "VCCO_0_T11") (pintype "power_in"))
    )
    (net (code "12") (name "PVADJ1") (class "Default")
      (node (ref "C676") (pin "1") (pinfunction "1_1") (pintype "passive"))
      (node (ref "C677") (pin "1") (pinfunction "1_1") (pintype "passive"))
      (node (ref "C678") (pin "1") (pinfunction "1_1") (pintype "passive"))
      (node (ref "C679") (pin "1") (pinfunction "1_1") (pintype "passive"))
      (node (ref "C680") (pin "2") (pinfunction "2_2") (pintype "passive"))
      (node (ref "C681") (pin "2") (pinfunction "2_2") (pintype "passive"))
      (node (ref "C682") (pin "2") (pinfunction "2_2") (pintype "passive"))
      (node (ref "C683") (pin "2") (pinfunction "2_2") (pintype "passive"))
      (node (ref "C684") (pin "2") (pinfunction "2_2") (pintype "passive"))
      (node (ref "C685") (pin "2") (pinfunction "2_2") (pintype "passive"))
      (node (ref "C686") (pin "2") (pinfunction "2_2") (pintype "passive"))
      (node (ref "C687") (pin "2") (pinfunction "2_2") (pintype "passive"))
      (node (ref "C688") (pin "2") (pinfunction "2_2") (pintype "passive"))
      (node (ref "C689") (pin "2") (pinfunction "2_2") (pintype "passive"))
      (node (ref "C690") (pin "2") (pinfunction "2_2") (pintype "passive"))
      (node (ref "C691") (pin "2") (pinfunction "2_2") (pintype "passive"))
      (node (ref "C692") (pin "2") (pinfunction "2_2") (pintype "passive"))
      (node (ref "C693") (pin "2") (pinfunction "2_2") (pintype "passive"))
      (node (ref "C694") (pin "2") (pinfunction "2_2") (pintype "passive"))
      (node (ref "C695") (pin "2") (pinfunction "2_2") (pintype "passive"))
      (node (ref "C696") (pin "2") (pinfunction "2_2") (pintype "passive"))
      (node (ref "C697") (pin "2") (pinfunction "2_2") (pintype "passive"))
      (node (ref "C698") (pin "2") (pinfunction "2_2") (pintype "passive"))
      (node (ref "C699") (pin "2") (pinfunction "2_2") (pintype "passive"))
      (node (ref "C700") (pin "2") (pinfunction "2_2") (pintype "passive"))
      (node (ref "C701") (pin "2") (pinfunction "2_2") (pintype "passive"))
      (node (ref "C702") (pin "2") (pinfunction "2_2") (pintype "passive"))
      (node (ref "C703") (pin "2") (pinfunction "2_2") (pintype "passive"))
      (node (ref "C704") (pin "2") (pinfunction "2_2") (pintype "passive"))
      (node (ref "C705") (pin "2") (pinfunction "2_2") (pintype "passive"))
      (node (ref "C706") (pin "2") (pinfunction "2_2") (pintype "passive"))
      (node (ref "C707") (pin "2") (pinfunction "2_2") (pintype "passive"))
      (node (ref "C708") (pin "2") (pinfunction "2_2") (pintype "passive"))
      (node (ref "C709") (pin "2") (pinfunction "2_2") (pintype "passive"))
      (node (ref "C710") (pin "2") (pinfunction "2_2") (pintype "passive"))
      (node (ref "C711") (pin "2") (pinfunction "2_2") (pintype "passive"))
      (node (ref "C719") (pin "2") (pinfunction "2_2") (pintype "passive"))
      (node (ref "C720") (pin "2") (pinfunction "2_2") (pintype "passive"))
      (node (ref "C721") (pin "2") (pinfunction "2_2") (pintype "passive"))
      (node (ref "IC2") (pin "A6") (pinfunction "VCCO_37_A6") (pintype "power_in"))
      (node (ref "IC2") (pin "AA6") (pinfunction "VCCO_34_AA6") (pintype "power_in"))
      (node (ref "IC2") (pin "AB3") (pinfunction "VCCO_34_AB3") (pintype "power_in"))
      (node (ref "IC2") (pin "AC10") (pinfunction "VCCO_34_AC10") (pintype "power_in"))
      (node (ref "IC2") (pin "B3") (pinfunction "VCCO_37_B3") (pintype "power_in"))
      (node (ref "IC2") (pin "C10") (pinfunction "VCCO_37_C10") (pintype "power_in"))
      (node (ref "IC2") (pin "D7") (pinfunction "VCCO_37_D7") (pintype "power_in"))
      (node (ref "IC2") (pin "E4") (pinfunction "VCCO_37_E4") (pintype "power_in"))
      (node (ref "IC2") (pin "F1") (pinfunction "VCCO_36_F1") (pintype "power_in"))
      (node (ref "IC2") (pin "F11") (pinfunction "VCCO_37_F11") (pintype "power_in"))
      (node (ref "IC2") (pin "G33") (pinfunction "VCCO_16_G33") (pintype "power_in"))
      (node (ref "IC2") (pin "G8") (pinfunction "VCCO_36_G8") (pintype "power_in"))
      (node (ref "IC2") (pin "H30") (pinfunction "VCCO_16_H30") (pintype "power_in"))
      (node (ref "IC2") (pin "H5") (pinfunction "VCCO_36_H5") (pintype "power_in"))
      (node (ref "IC2") (pin "J12") (pinfunction "VCCO_36_J12") (pintype "power_in"))
      (node (ref "IC2") (pin "J2") (pinfunction "VCCO_36_J2") (pintype "power_in"))
      (node (ref "IC2") (pin "J27") (pinfunction "VCCO_16_J27") (pintype "power_in"))
      (node (ref "IC2") (pin "K24") (pinfunction "VCCO_16_K24") (pintype "power_in"))
      (node (ref "IC2") (pin "K34") (pinfunction "VCCO_16_K34") (pintype "power_in"))
      (node (ref "IC2") (pin "K9") (pinfunction "VCCO_36_K9") (pintype "power_in"))
      (node (ref "IC2") (pin "L31") (pinfunction "VCCO_16_L31") (pintype "power_in"))
      (node (ref "IC2") (pin "L6") (pinfunction "VCCO_36_L6") (pintype "power_in"))
      (node (ref "IC2") (pin "M3") (pinfunction "VCCO_35_M3") (pintype "power_in"))
      (node (ref "IC2") (pin "N10") (pinfunction "VCCO_35_N10") (pintype "power_in"))
      (node (ref "IC2") (pin "P7") (pinfunction "VCCO_35_P7") (pintype "power_in"))
      (node (ref "IC2") (pin "R4") (pinfunction "VCCO_35_R4") (pintype "power_in"))
      (node (ref "IC2") (pin "T1") (pinfunction "VCCO_35_T1") (pintype "power_in"))
      (node (ref "IC2") (pin "U8") (pinfunction "VCCO_35_U8") (pintype "power_in"))
      (node (ref "IC2") (pin "V5") (pinfunction "VCCO_34_V5") (pintype "power_in"))
      (node (ref "IC2") (pin "W2") (pinfunction "VCCO_34_W2") (pintype "power_in"))
      (node (ref "IC2") (pin "Y9") (pinfunction "VCCO_34_Y9") (pintype "power_in"))
    )
    (net (code "13") (name "PVADJ2") (class "Default")
      (node (ref "C644") (pin "2") (pinfunction "2_2") (pintype "passive"))
      (node (ref "C645") (pin "2") (pinfunction "2_2") (pintype "passive"))
      (node (ref "C646") (pin "2") (pinfunction "2_2") (pintype "passive"))
      (node (ref "C647") (pin "2") (pinfunction "2_2") (pintype "passive"))
      (node (ref "C648") (pin "2") (pinfunction "2_2") (pintype "passive"))
      (node (ref "C649") (pin "2") (pinfunction "2_2") (pintype "passive"))
      (node (ref "C650") (pin "2") (pinfunction "2_2") (pintype "passive"))
      (node (ref "C651") (pin "2") (pinfunction "2_2") (pintype "passive"))
      (node (ref "C652") (pin "2") (pinfunction "2_2") (pintype "passive"))
      (node (ref "C653") (pin "2") (pinfunction "2_2") (pintype "passive"))
      (node (ref "C654") (pin "2") (pinfunction "2_2") (pintype "passive"))
      (node (ref "C655") (pin "2") (pinfunction "2_2") (pintype "passive"))
      (node (ref "C656") (pin "2") (pinfunction "2_2") (pintype "passive"))
      (node (ref "C657") (pin "2") (pinfunction "2_2") (pintype "passive"))
      (node (ref "C658") (pin "2") (pinfunction "2_2") (pintype "passive"))
      (node (ref "C659") (pin "2") (pinfunction "2_2") (pintype "passive"))
      (node (ref "C660") (pin "2") (pinfunction "2_2") (pintype "passive"))
      (node (ref "C661") (pin "2") (pinfunction "2_2") (pintype "passive"))
      (node (ref "C662") (pin "2") (pinfunction "2_2") (pintype "passive"))
      (node (ref "C663") (pin "2") (pinfunction "2_2") (pintype "passive"))
      (node (ref "C664") (pin "2") (pinfunction "2_2") (pintype "passive"))
      (node (ref "C665") (pin "2") (pinfunction "2_2") (pintype "passive"))
      (node (ref "C666") (pin "2") (pinfunction "2_2") (pintype "passive"))
      (node (ref "C667") (pin "2") (pinfunction "2_2") (pintype "passive"))
      (node (ref "C668") (pin "2") (pinfunction "2_2") (pintype "passive"))
      (node (ref "C669") (pin "2") (pinfunction "2_2") (pintype "passive"))
      (node (ref "C670") (pin "2") (pinfunction "2_2") (pintype "passive"))
      (node (ref "C671") (pin "2") (pinfunction "2_2") (pintype "passive"))
      (node (ref "C672") (pin "2") (pinfunction "2_2") (pintype "passive"))
      (node (ref "C673") (pin "2") (pinfunction "2_2") (pintype "passive"))
      (node (ref "C674") (pin "2") (pinfunction "2_2") (pintype "passive"))
      (node (ref "C675") (pin "2") (pinfunction "2_2") (pintype "passive"))
      (node (ref "C712") (pin "1") (pinfunction "1_1") (pintype "passive"))
      (node (ref "C713") (pin "1") (pinfunction "1_1") (pintype "passive"))
      (node (ref "C714") (pin "1") (pinfunction "1_1") (pintype "passive"))
      (node (ref "C715") (pin "1") (pinfunction "1_1") (pintype "passive"))
      (node (ref "C716") (pin "2") (pinfunction "2_2") (pintype "passive"))
      (node (ref "C717") (pin "2") (pinfunction "2_2") (pintype "passive"))
      (node (ref "C718") (pin "2") (pinfunction "2_2") (pintype "passive"))
      (node (ref "IC2") (pin "A31") (pinfunction "VCCO_17_A31") (pintype "power_in"))
      (node (ref "IC2") (pin "AA31") (pinfunction "VCCO_14_AA31") (pintype "power_in"))
      (node (ref "IC2") (pin "AB28") (pinfunction "VCCO_14_AB28") (pintype "power_in"))
      (node (ref "IC2") (pin "AC25") (pinfunction "VCCO_13_AC25") (pintype "power_in"))
      (node (ref "IC2") (pin "AD32") (pinfunction "VCCO_13_AD32") (pintype "power_in"))
      (node (ref "IC2") (pin "AE29") (pinfunction "VCCO_13_AE29") (pintype "power_in"))
      (node (ref "IC2") (pin "AF26") (pinfunction "VCCO_13_AF26") (pintype "power_in"))
      (node (ref "IC2") (pin "AG33") (pinfunction "VCCO_13_AG33") (pintype "power_in"))
      (node (ref "IC2") (pin "AH30") (pinfunction "VCCO_13_AH30") (pintype "power_in"))
      (node (ref "IC2") (pin "AJ27") (pinfunction "VCCO_12_AJ27") (pintype "power_in"))
      (node (ref "IC2") (pin "AK34") (pinfunction "VCCO_12_AK34") (pintype "power_in"))
      (node (ref "IC2") (pin "AL31") (pinfunction "VCCO_12_AL31") (pintype "power_in"))
      (node (ref "IC2") (pin "AM28") (pinfunction "VCCO_12_AM28") (pintype "power_in"))
      (node (ref "IC2") (pin "AN25") (pinfunction "VCCO_12_AN25") (pintype "power_in"))
      (node (ref "IC2") (pin "AP32") (pinfunction "VCCO_12_AP32") (pintype "power_in"))
      (node (ref "IC2") (pin "B28") (pinfunction "VCCO_17_B28") (pintype "power_in"))
      (node (ref "IC2") (pin "C25") (pinfunction "VCCO_17_C25") (pintype "power_in"))
      (node (ref "IC2") (pin "D32") (pinfunction "VCCO_17_D32") (pintype "power_in"))
      (node (ref "IC2") (pin "E29") (pinfunction "VCCO_17_E29") (pintype "power_in"))
      (node (ref "IC2") (pin "F26") (pinfunction "VCCO_17_F26") (pintype "power_in"))
      (node (ref "IC2") (pin "M28") (pinfunction "VCCO_15_M28") (pintype "power_in"))
      (node (ref "IC2") (pin "N25") (pinfunction "VCCO_15_N25") (pintype "power_in"))
      (node (ref "IC2") (pin "P32") (pinfunction "VCCO_15_P32") (pintype "power_in"))
      (node (ref "IC2") (pin "R29") (pinfunction "VCCO_15_R29") (pintype "power_in"))
      (node (ref "IC2") (pin "T26") (pinfunction "VCCO_15_T26") (pintype "power_in"))
      (node (ref "IC2") (pin "U33") (pinfunction "VCCO_15_U33") (pintype "power_in"))
      (node (ref "IC2") (pin "V30") (pinfunction "VCCO_14_V30") (pintype "power_in"))
      (node (ref "IC2") (pin "W27") (pinfunction "VCCO_14_W27") (pintype "power_in"))
      (node (ref "IC2") (pin "Y24") (pinfunction "VCCO_14_Y24") (pintype "power_in"))
      (node (ref "IC2") (pin "Y34") (pinfunction "VCCO_14_Y34") (pintype "power_in"))
    )
    (net (code "14") (name "VCCAUX") (class "Default")
      (node (ref "C266") (pin "2") (pinfunction "2_2") (pintype "passive"))
      (node (ref "C269") (pin "2") (pinfunction "2_2") (pintype "passive"))
      (node (ref "C270") (pin "2") (pinfunction "2_2") (pintype "passive"))
      (node (ref "C271") (pin "2") (pinfunction "2_2") (pintype "passive"))
      (node (ref "C275") (pin "2") (pinfunction "2_2") (pintype "passive"))
      (node (ref "C276") (pin "2") (pinfunction "2_2") (pintype "passive"))
      (node (ref "C277") (pin "2") (pinfunction "2_2") (pintype "passive"))
      (node (ref "C278") (pin "2") (pinfunction "2_2") (pintype "passive"))
      (node (ref "C279") (pin "2") (pinfunction "2_2") (pintype "passive"))
      (node (ref "C280") (pin "2") (pinfunction "2_2") (pintype "passive"))
      (node (ref "C592") (pin "1") (pinfunction "1_1") (pintype "passive"))
      (node (ref "C593") (pin "1") (pinfunction "1_1") (pintype "passive"))
      (node (ref "C594") (pin "2") (pinfunction "2_2") (pintype "passive"))
      (node (ref "C596") (pin "2") (pinfunction "2_2") (pintype "passive"))
      (node (ref "C597") (pin "2") (pinfunction "2_2") (pintype "passive"))
      (node (ref "C598") (pin "2") (pinfunction "2_2") (pintype "passive"))
      (node (ref "C614") (pin "2") (pinfunction "2_2") (pintype "passive"))
      (node (ref "C738") (pin "2") (pinfunction "2_2") (pintype "passive"))
      (node (ref "C739") (pin "2") (pinfunction "2_2") (pintype "passive"))
      (node (ref "IC2") (pin "AA13") (pinfunction "VCCAUX_AA13") (pintype "power_in"))
      (node (ref "IC2") (pin "AA23") (pinfunction "VCCAUX_AA23") (pintype "power_in"))
      (node (ref "IC2") (pin "AB12") (pinfunction "VCCAUX_AB12") (pintype "power_in"))
      (node (ref "IC2") (pin "AB22") (pinfunction "VCCAUX_AB22") (pintype "power_in"))
      (node (ref "IC2") (pin "AC13") (pinfunction "VCCAUX_AC13") (pintype "power_in"))
      (node (ref "IC2") (pin "AC23") (pinfunction "VCCAUX_AC23") (pintype "power_in"))
      (node (ref "IC2") (pin "AD12") (pinfunction "VCCAUX_AD12") (pintype "power_in"))
      (node (ref "IC2") (pin "M22") (pinfunction "VCCAUX_M22") (pintype "power_in"))
      (node (ref "IC2") (pin "N13") (pinfunction "VCCAUX_N13") (pintype "power_in"))
      (node (ref "IC2") (pin "N23") (pinfunction "VCCAUX_N23") (pintype "power_in"))
      (node (ref "IC2") (pin "P12") (pinfunction "VCCAUX_P12") (pintype "power_in"))
      (node (ref "IC2") (pin "P22") (pinfunction "VCCAUX_P22") (pintype "power_in"))
      (node (ref "IC2") (pin "R13") (pinfunction "VCCAUX_R13") (pintype "power_in"))
      (node (ref "IC2") (pin "R23") (pinfunction "VCCAUX_R23") (pintype "power_in"))
      (node (ref "IC2") (pin "T12") (pinfunction "VCCAUX_T12") (pintype "power_in"))
      (node (ref "IC2") (pin "T18") (pinfunction "VCCADC_0_T18") (pintype "power_in"))
      (node (ref "IC2") (pin "T22") (pinfunction "VCCAUX_T22") (pintype "power_in"))
      (node (ref "IC2") (pin "U13") (pinfunction "VCCAUX_U13") (pintype "power_in"))
      (node (ref "IC2") (pin "U23") (pinfunction "VCCAUX_U23") (pintype "power_in"))
      (node (ref "IC2") (pin "V12") (pinfunction "VCCAUX_V12") (pintype "power_in"))
      (node (ref "IC2") (pin "V22") (pinfunction "VCCAUX_V22") (pintype "power_in"))
      (node (ref "IC2") (pin "W13") (pinfunction "VCCAUX_W13") (pintype "power_in"))
      (node (ref "IC2") (pin "W23") (pinfunction "VCCAUX_W23") (pintype "power_in"))
      (node (ref "IC2") (pin "Y12") (pinfunction "VCCAUX_Y12") (pintype "power_in"))
      (node (ref "IC2") (pin "Y22") (pinfunction "VCCAUX_Y22") (pintype "power_in"))
      (node (ref "L12") (pin "2") (pinfunction "2_2") (pintype "passive"))
    )
    (net (code "15") (name "VCCBATT") (class "Default")
      (node (ref "BH1") (pin "1") (pinfunction "PLUS_1") (pintype "power_in"))
      (node (ref "C615") (pin "2") (pinfunction "2_2") (pintype "passive"))
      (node (ref "IC2") (pin "K13") (pinfunction "VCCBATT_0_K13") (pintype "power_in"))
    )
    (net (code "16") (name "VCCBRAM") (class "Default")
      (node (ref "C226") (pin "1") (pinfunction "1_1") (pintype "passive"))
      (node (ref "C243") (pin "2") (pinfunction "2_2") (pintype "passive"))
      (node (ref "C244") (pin "2") (pinfunction "2_2") (pintype "passive"))
      (node (ref "C245") (pin "2") (pinfunction "2_2") (pintype "passive"))
      (node (ref "C246") (pin "2") (pinfunction "2_2") (pintype "passive"))
      (node (ref "C247") (pin "2") (pinfunction "2_2") (pintype "passive"))
      (node (ref "C248") (pin "2") (pinfunction "2_2") (pintype "passive"))
      (node (ref "C249") (pin "2") (pinfunction "2_2") (pintype "passive"))
      (node (ref "C250") (pin "2") (pinfunction "2_2") (pintype "passive"))
      (node (ref "C264") (pin "2") (pinfunction "2_2") (pintype "passive"))
      (node (ref "C265") (pin "2") (pinfunction "2_2") (pintype "passive"))
      (node (ref "C587") (pin "1") (pinfunction "1_1") (pintype "passive"))
      (node (ref "C588") (pin "2") (pinfunction "2_2") (pintype "passive"))
      (node (ref "C589") (pin "2") (pinfunction "2_2") (pintype "passive"))
      (node (ref "C591") (pin "2") (pinfunction "2_2") (pintype "passive"))
      (node (ref "IC2") (pin "AA21") (pinfunction "VCCBRAM_AA21") (pintype "power_in"))
      (node (ref "IC2") (pin "AB20") (pinfunction "VCCBRAM_AB20") (pintype "power_in"))
      (node (ref "IC2") (pin "AC21") (pinfunction "VCCBRAM_AC21") (pintype "power_in"))
      (node (ref "IC2") (pin "M20") (pinfunction "VCCBRAM_M20") (pintype "power_in"))
      (node (ref "IC2") (pin "N21") (pinfunction "VCCBRAM_N21") (pintype "power_in"))
      (node (ref "IC2") (pin "P20") (pinfunction "VCCBRAM_P20") (pintype "power_in"))
      (node (ref "IC2") (pin "R21") (pinfunction "VCCBRAM_R21") (pintype "power_in"))
      (node (ref "IC2") (pin "T20") (pinfunction "VCCBRAM_T20") (pintype "power_in"))
      (node (ref "IC2") (pin "U21") (pinfunction "VCCBRAM_U21") (pintype "power_in"))
      (node (ref "IC2") (pin "V20") (pinfunction "VCCBRAM_V20") (pintype "power_in"))
      (node (ref "IC2") (pin "W21") (pinfunction "VCCBRAM_W21") (pintype "power_in"))
      (node (ref "IC2") (pin "Y20") (pinfunction "VCCBRAM_Y20") (pintype "power_in"))
      (node (ref "L10") (pin "2") (pinfunction "2_2") (pintype "passive"))
    )
    (net (code "17") (name "unconnected-(IC2R-VN_0-PadV17)") (class "Default")
      (node (ref "IC2") (pin "V17") (pinfunction "VN_0_V17") (pintype "input+no_connect"))
    )
    (net (code "18") (name "unconnected-(IC2R-VP_0-PadU18)") (class "Default")
      (node (ref "IC2") (pin "U18") (pinfunction "VP_0_U18") (pintype "input+no_connect"))
    )
  )
)
